# Titan_Servo_v1p01e.net
KiCad netlist of a schematic drawn in EAGLE
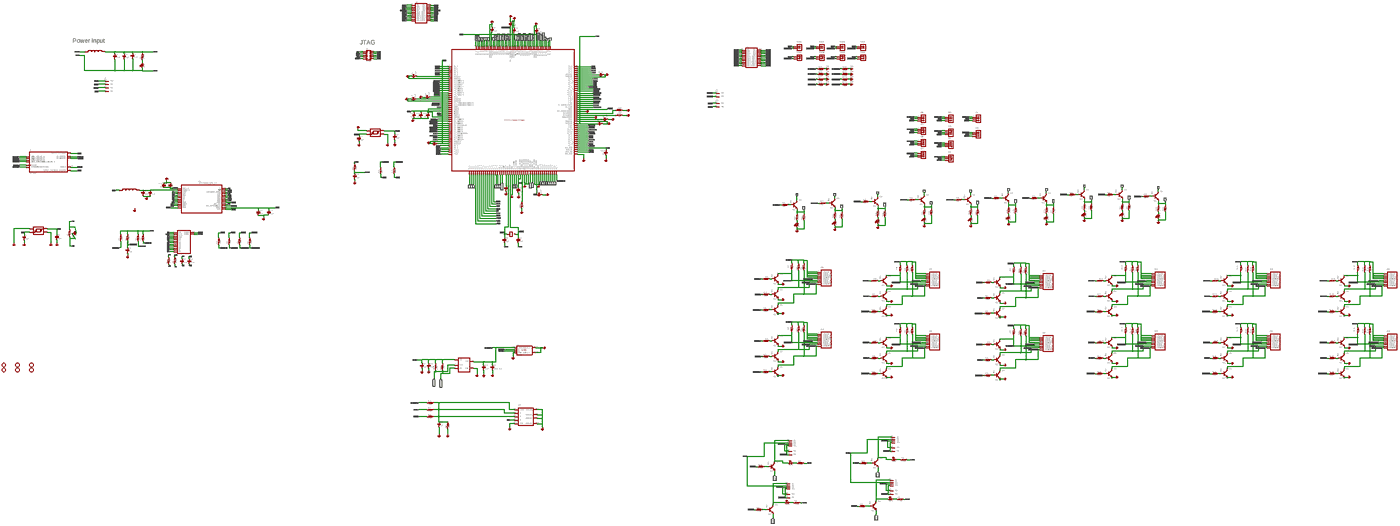
[diagram p0: schematic, sheet 1, overview]
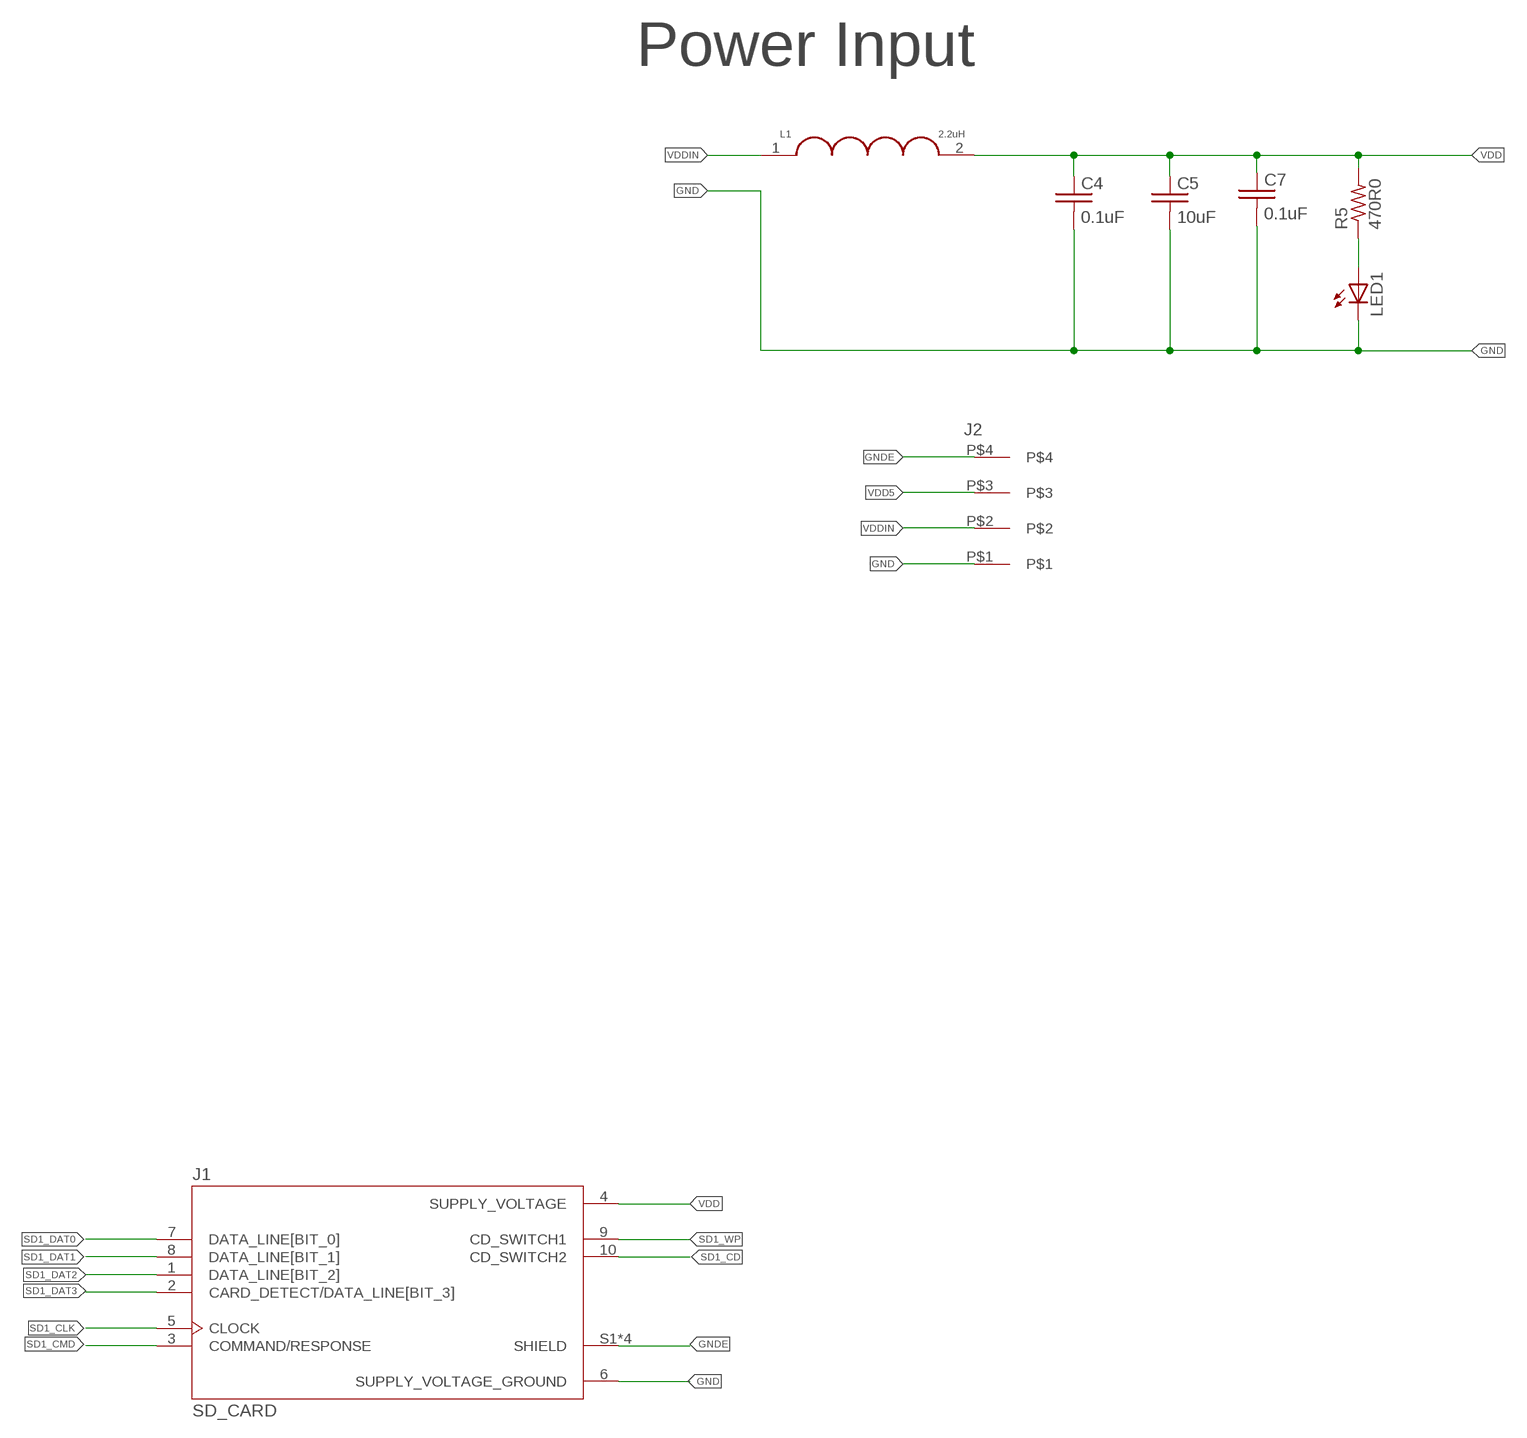
[diagram p1: schematic, sheet 1, part 1 of 9]
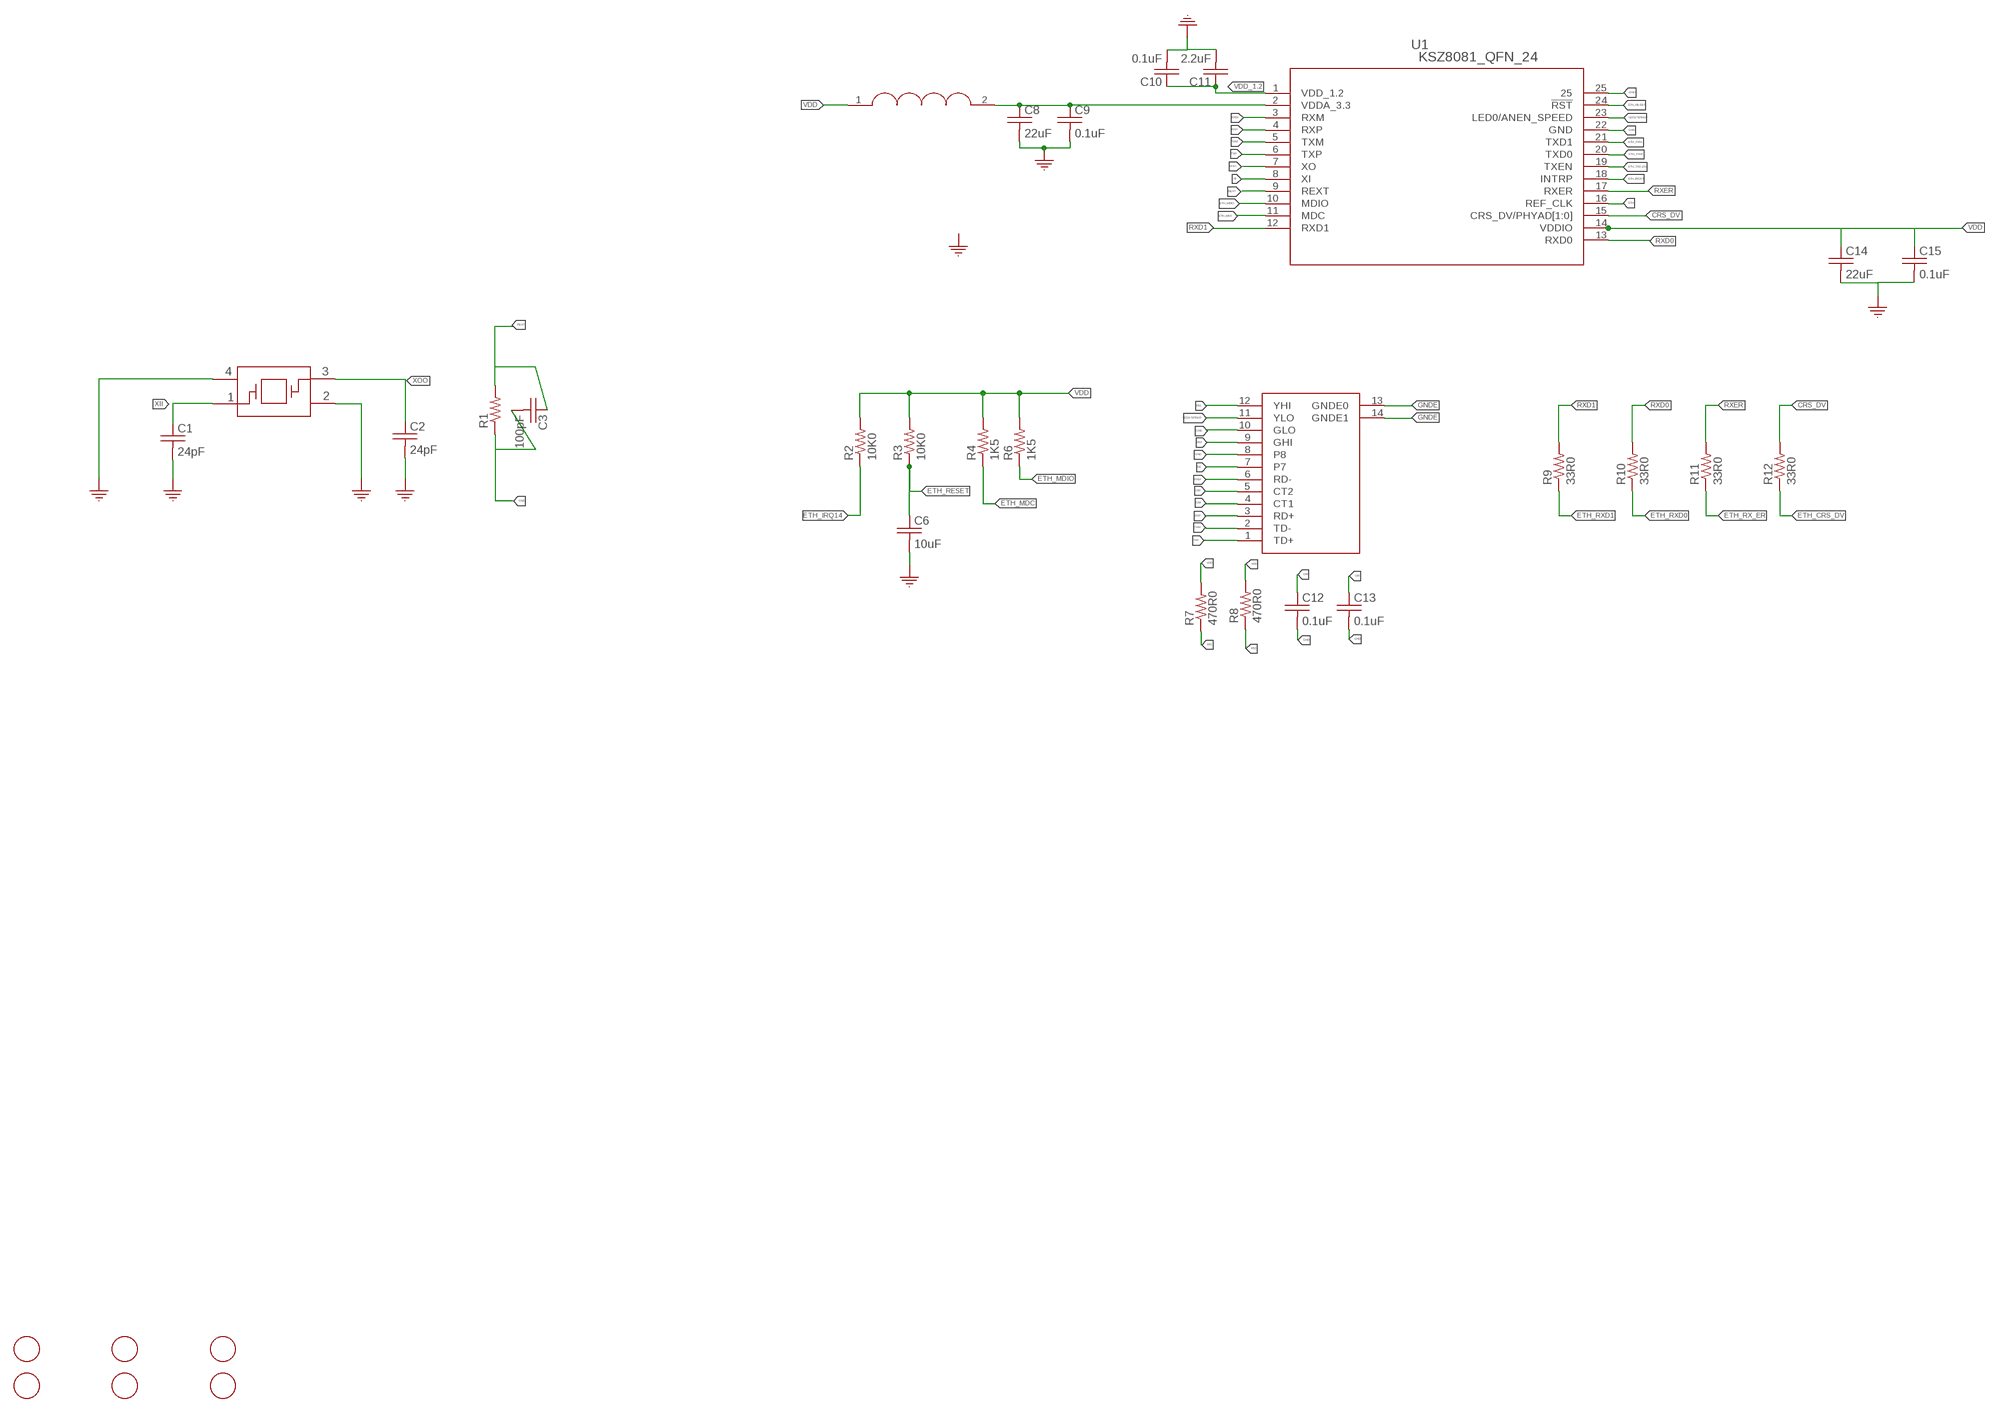
[diagram p2: schematic, sheet 1, part 2 of 9]
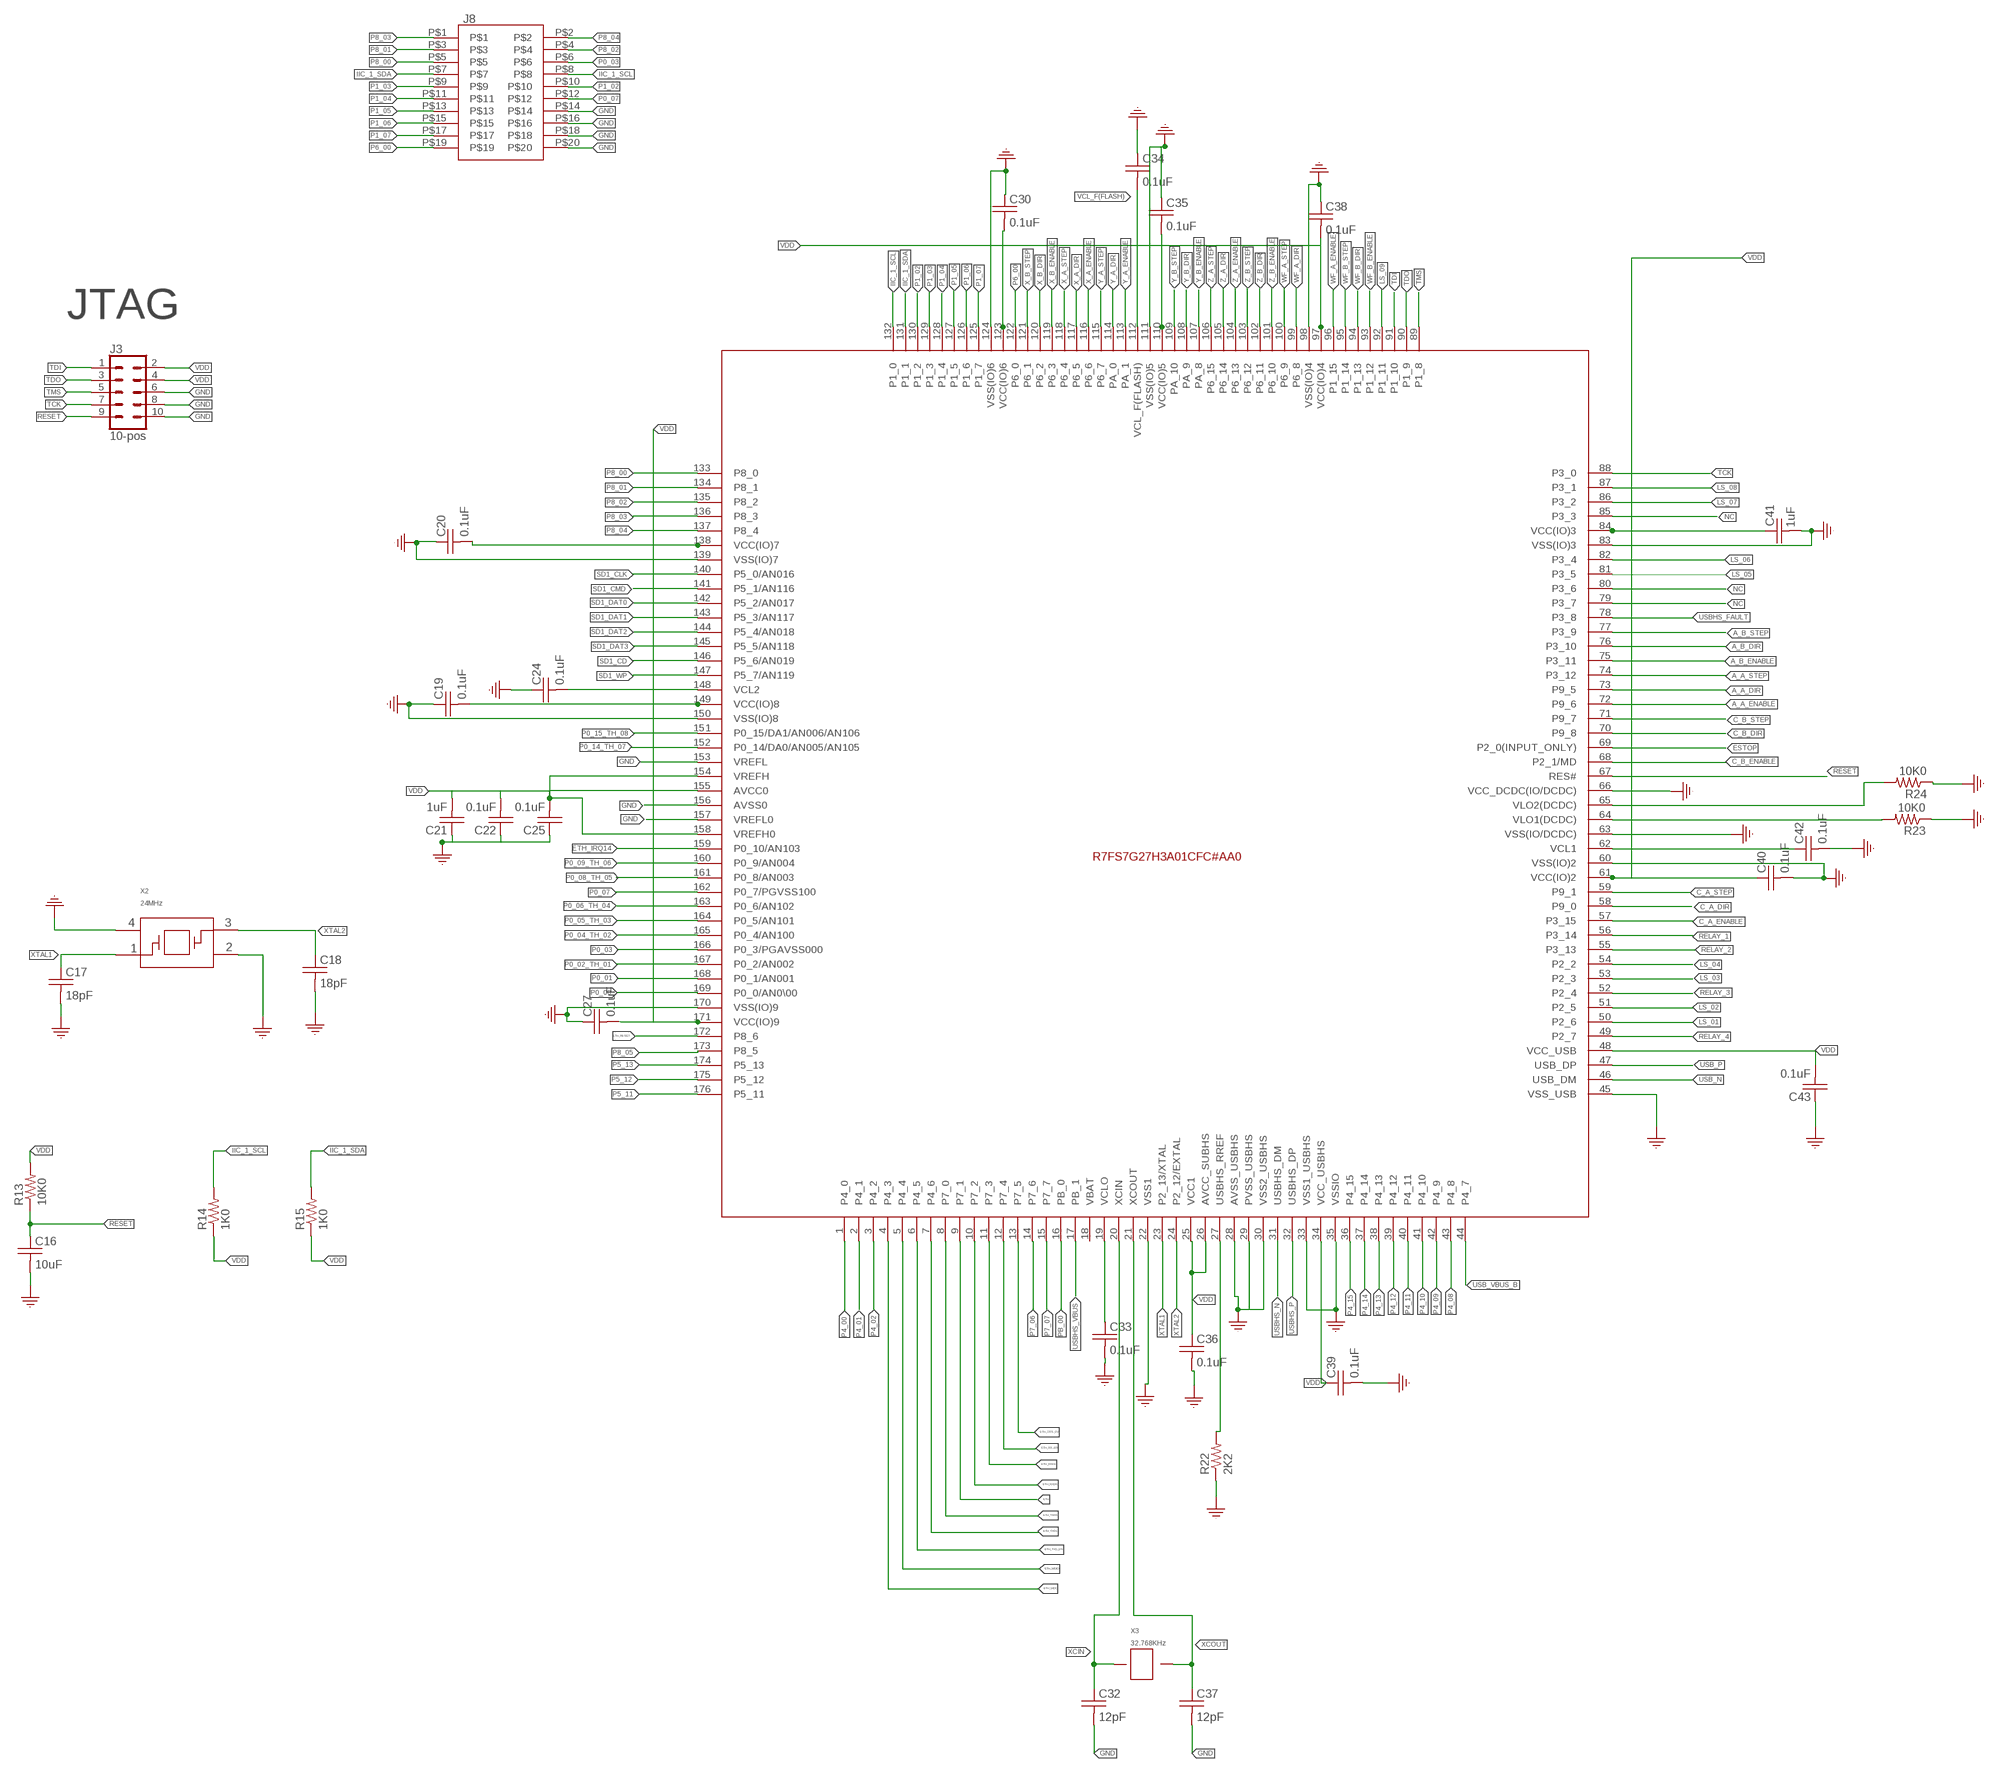
[diagram p3: schematic, sheet 1, part 3 of 9]
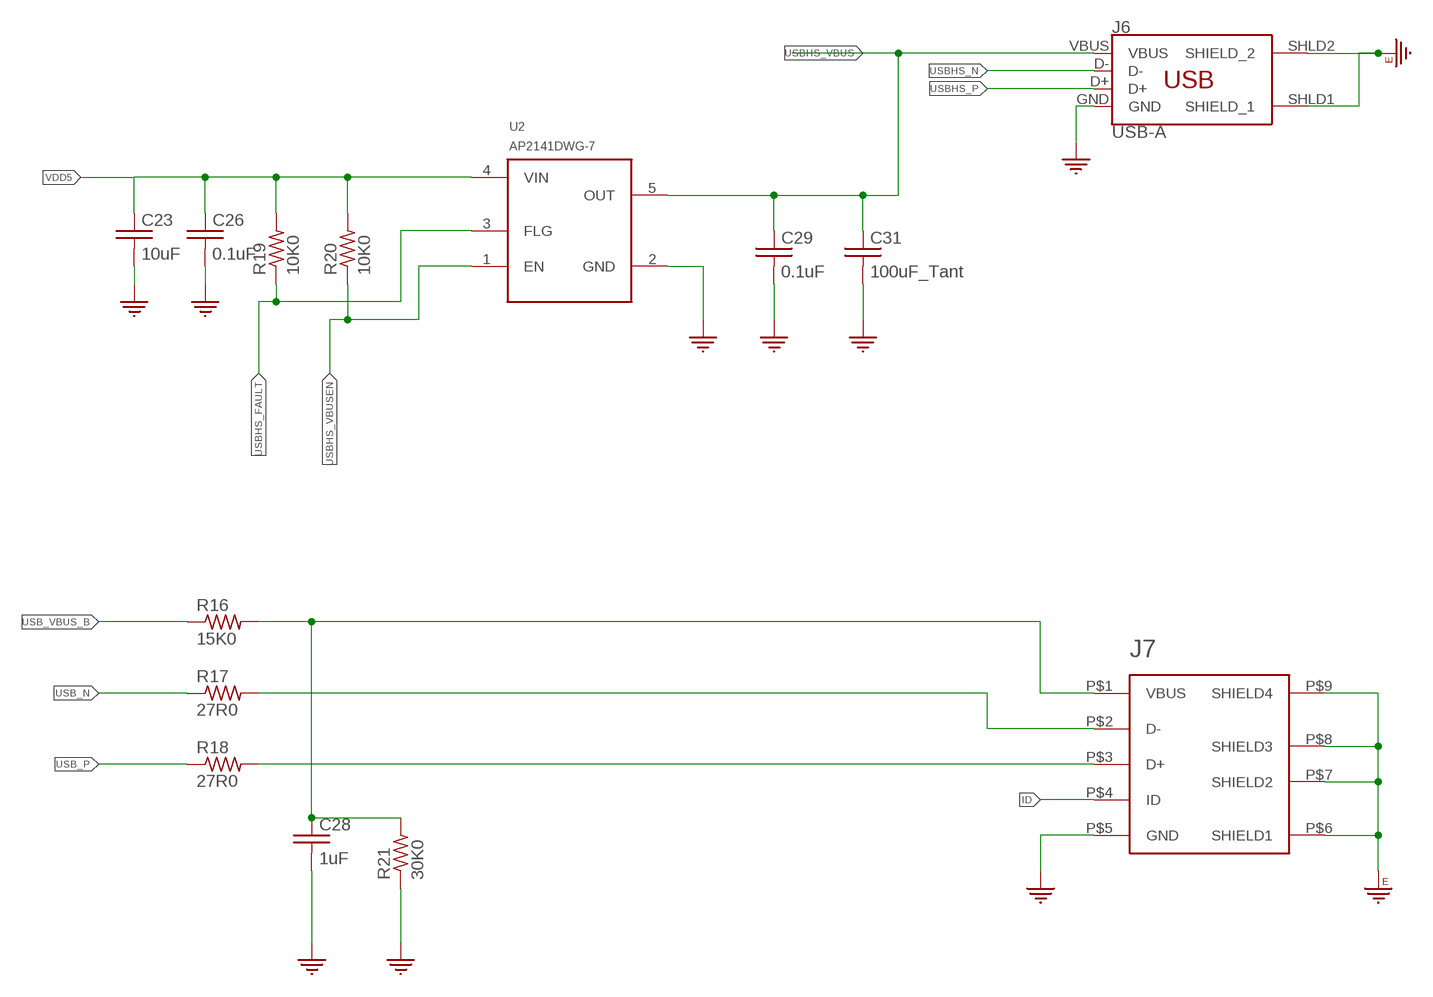
[diagram p4: schematic, sheet 1, part 4 of 9]
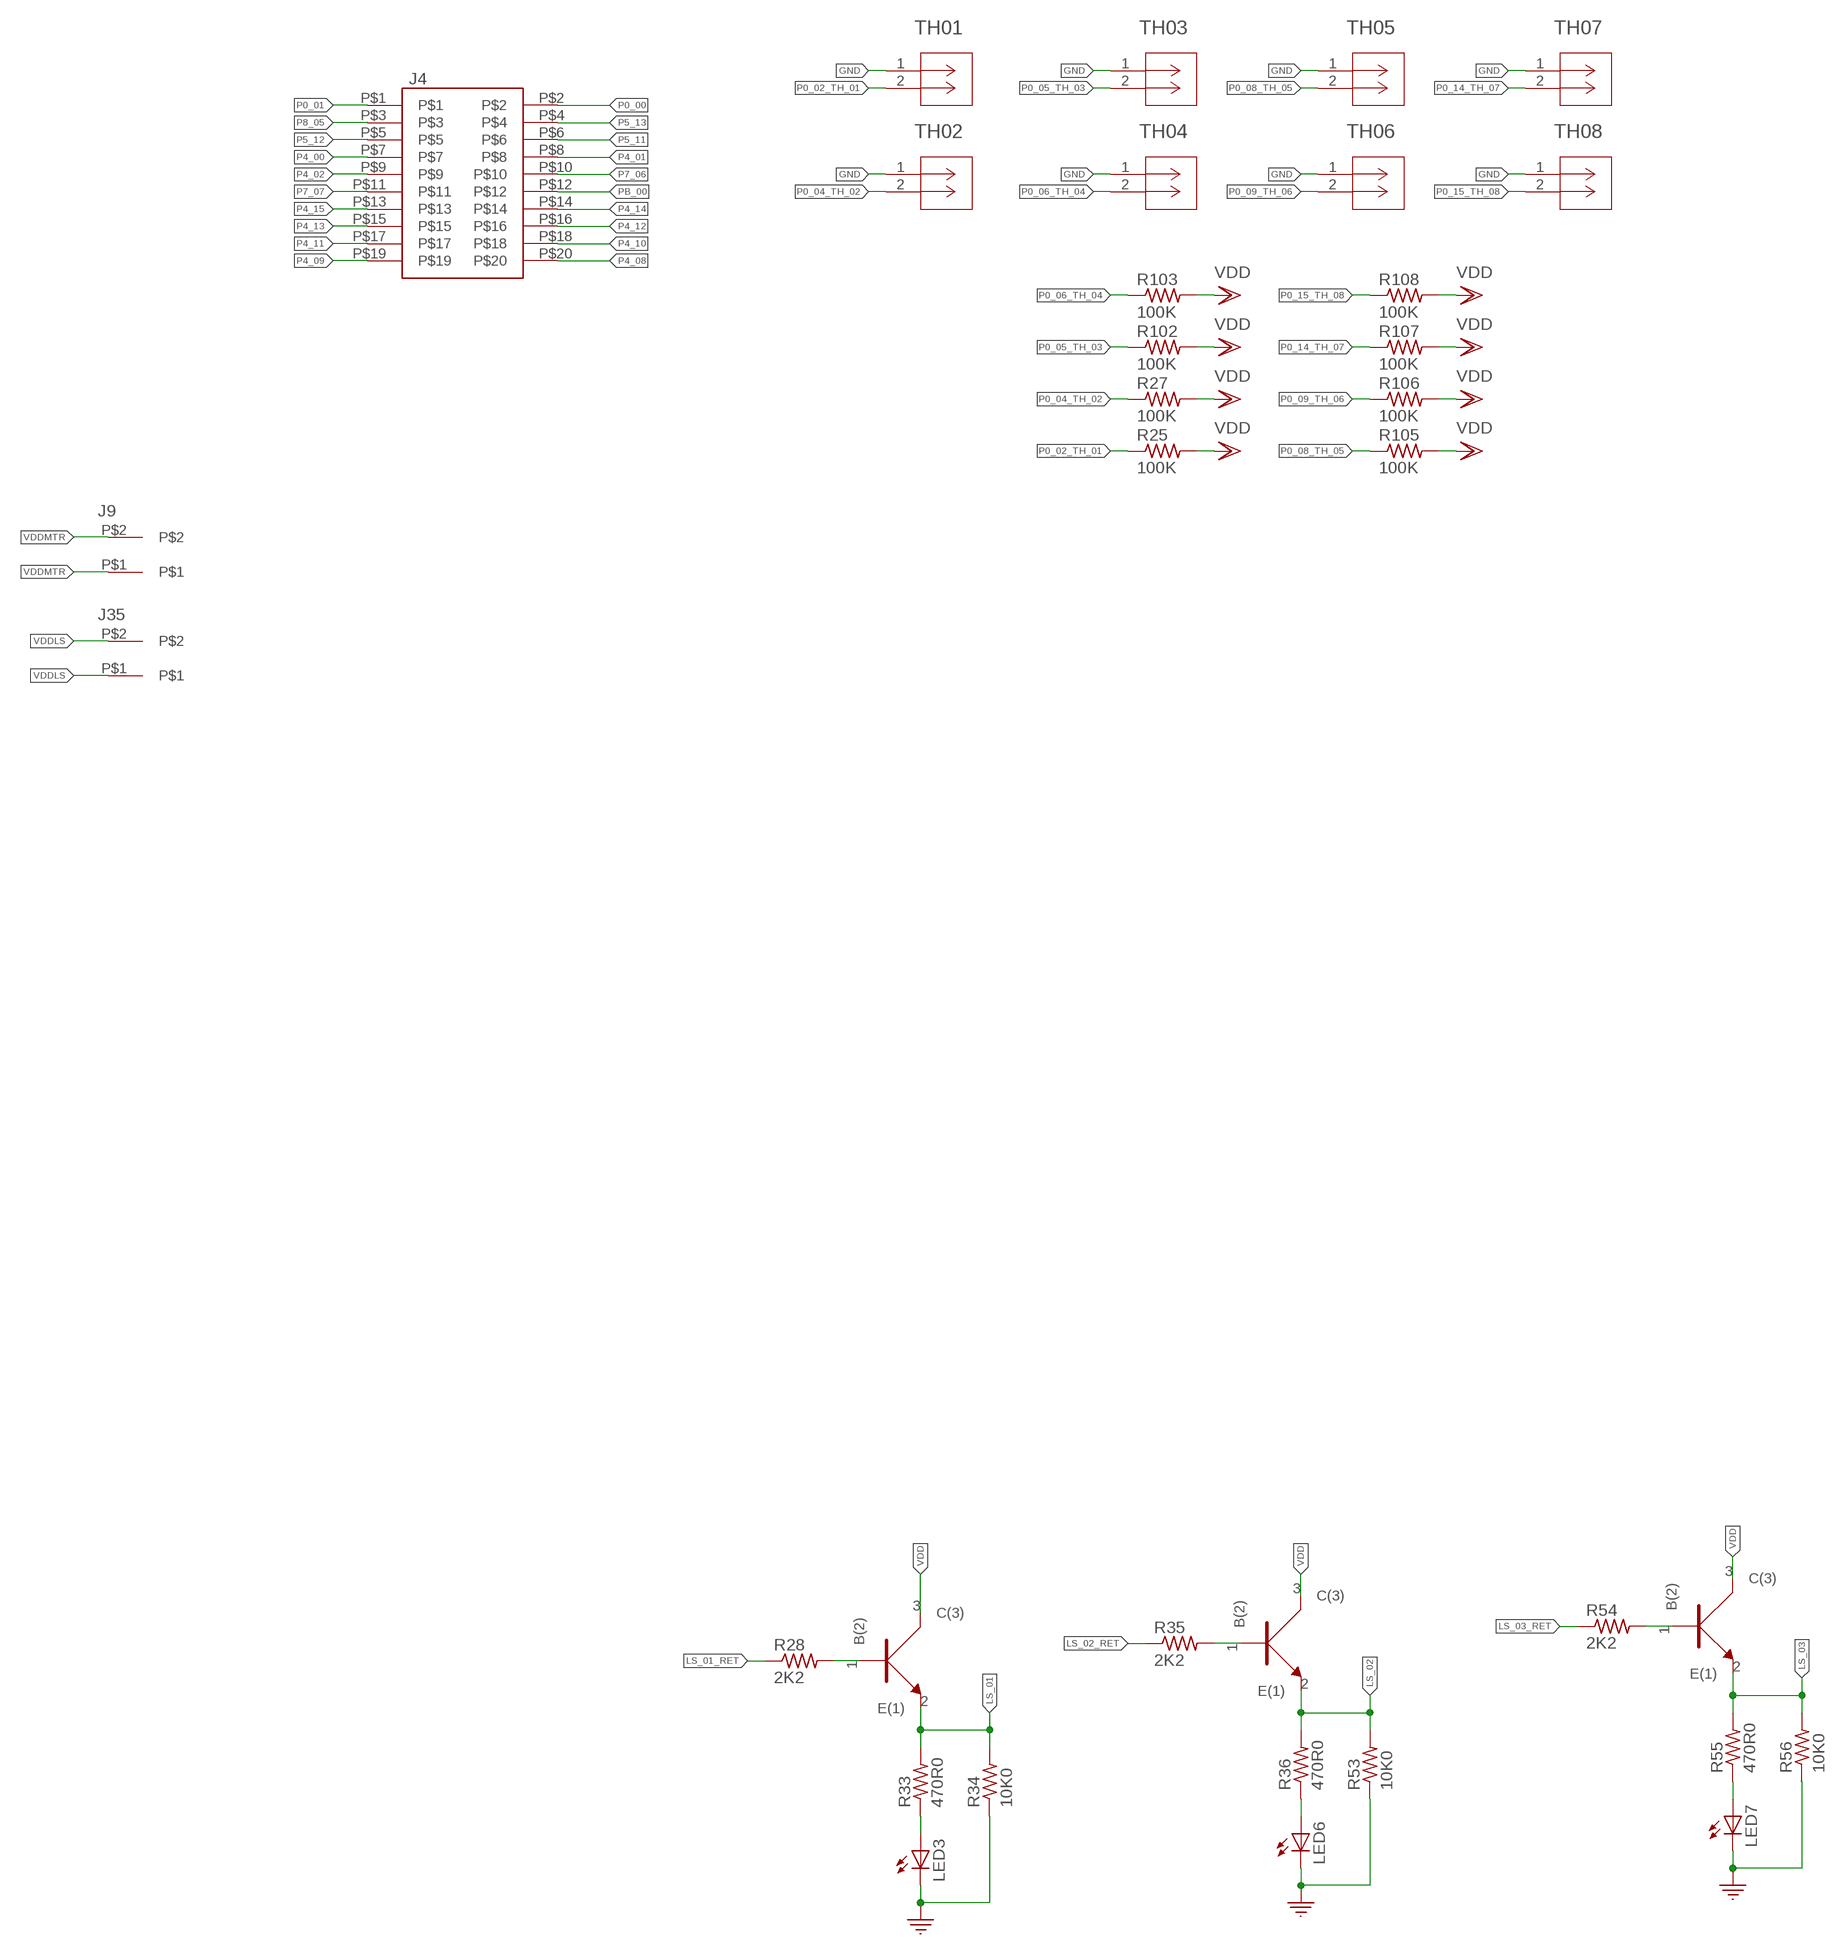
[diagram p5: schematic, sheet 1, part 5 of 9]
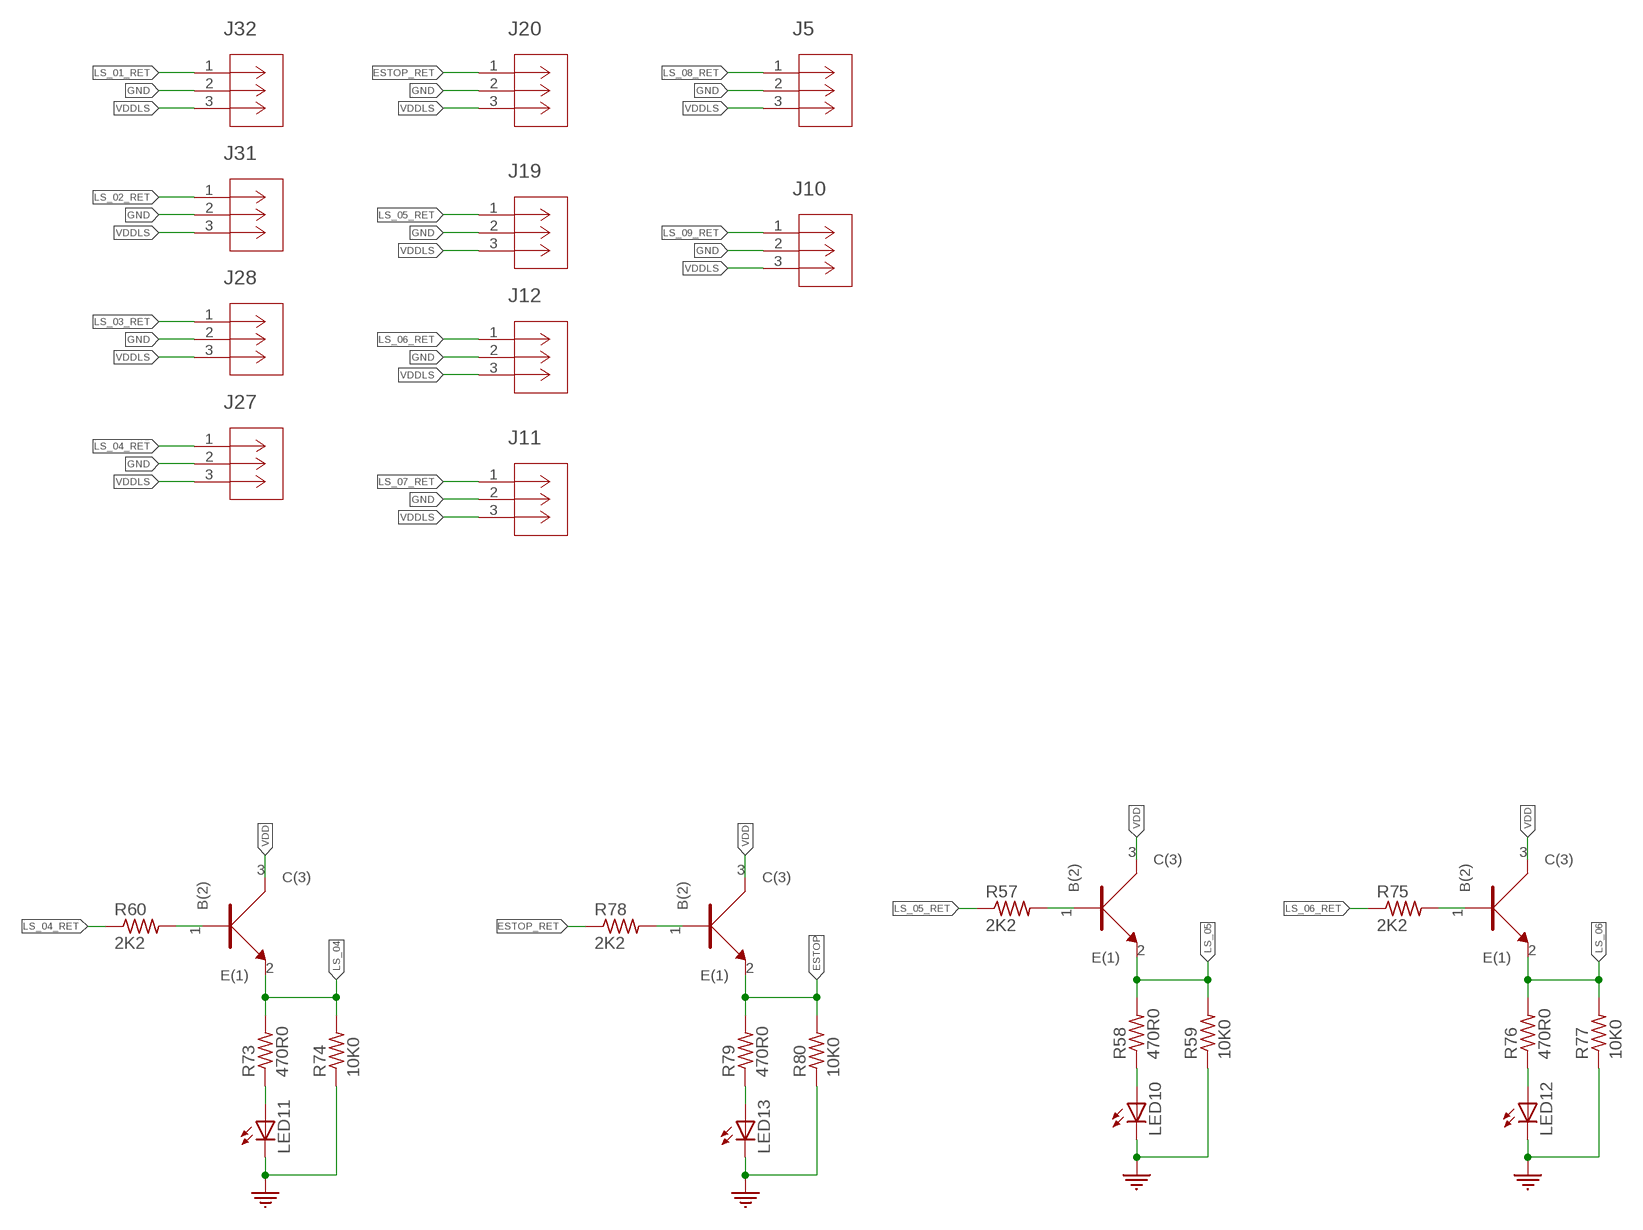
[diagram p6: schematic, sheet 1, part 6 of 9]
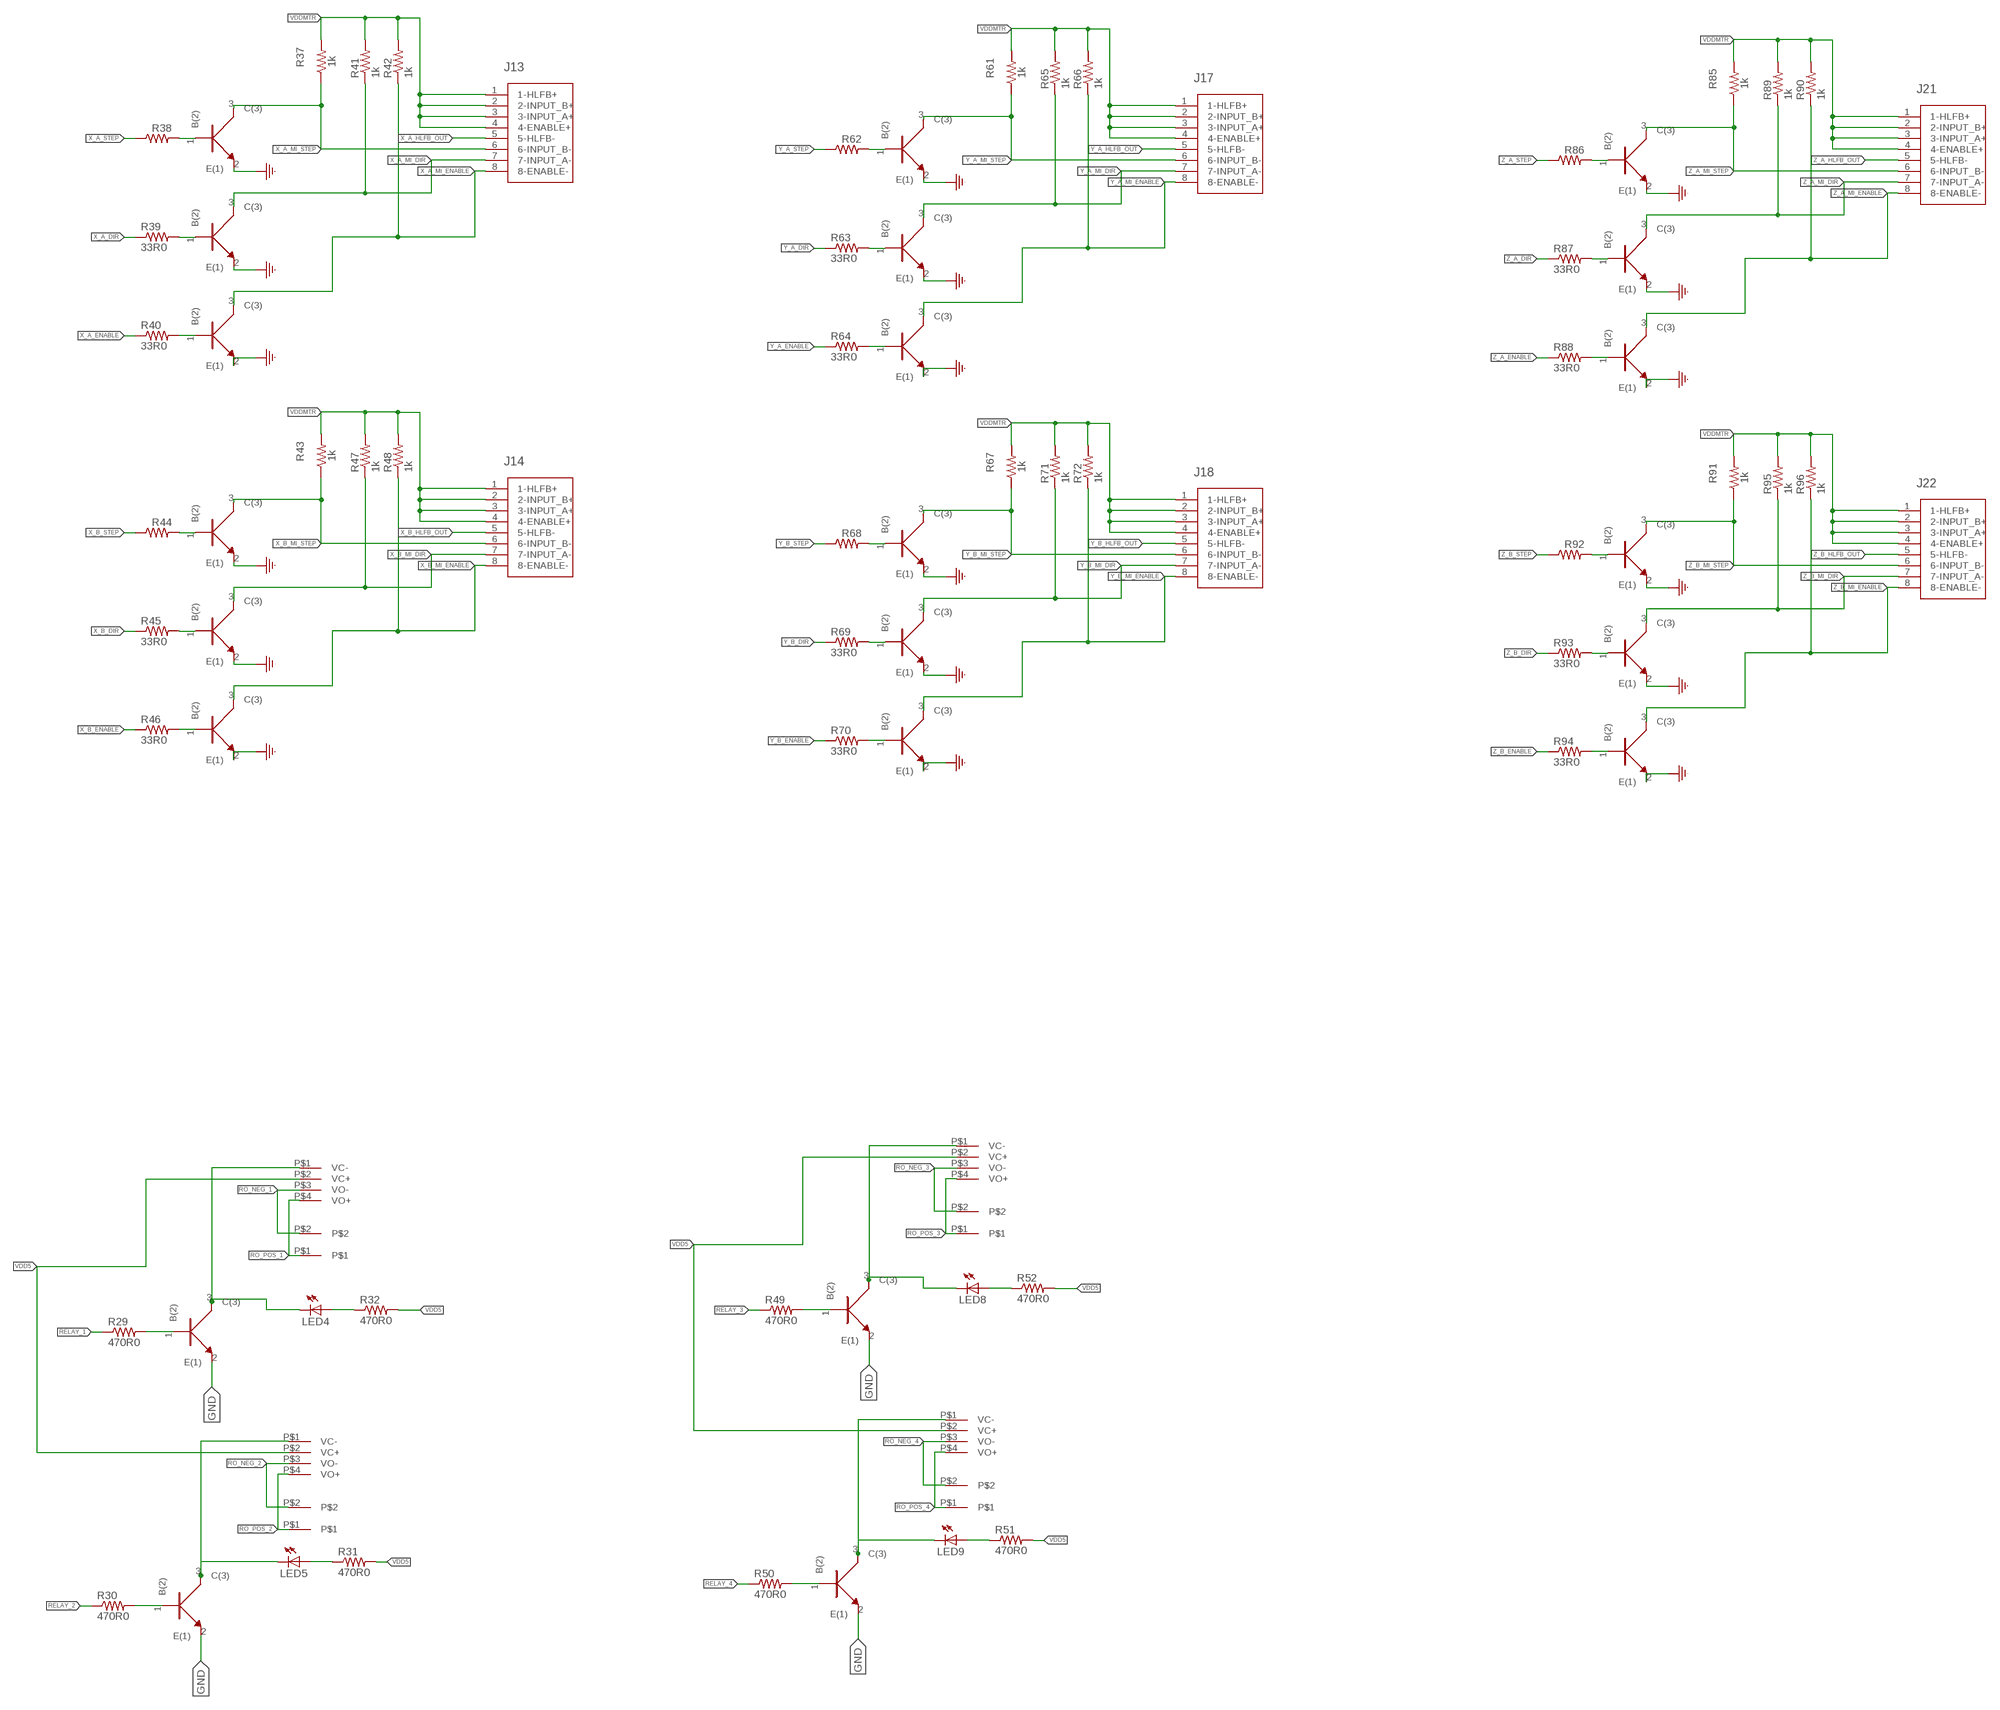
[diagram p7: schematic, sheet 1, part 7 of 9]
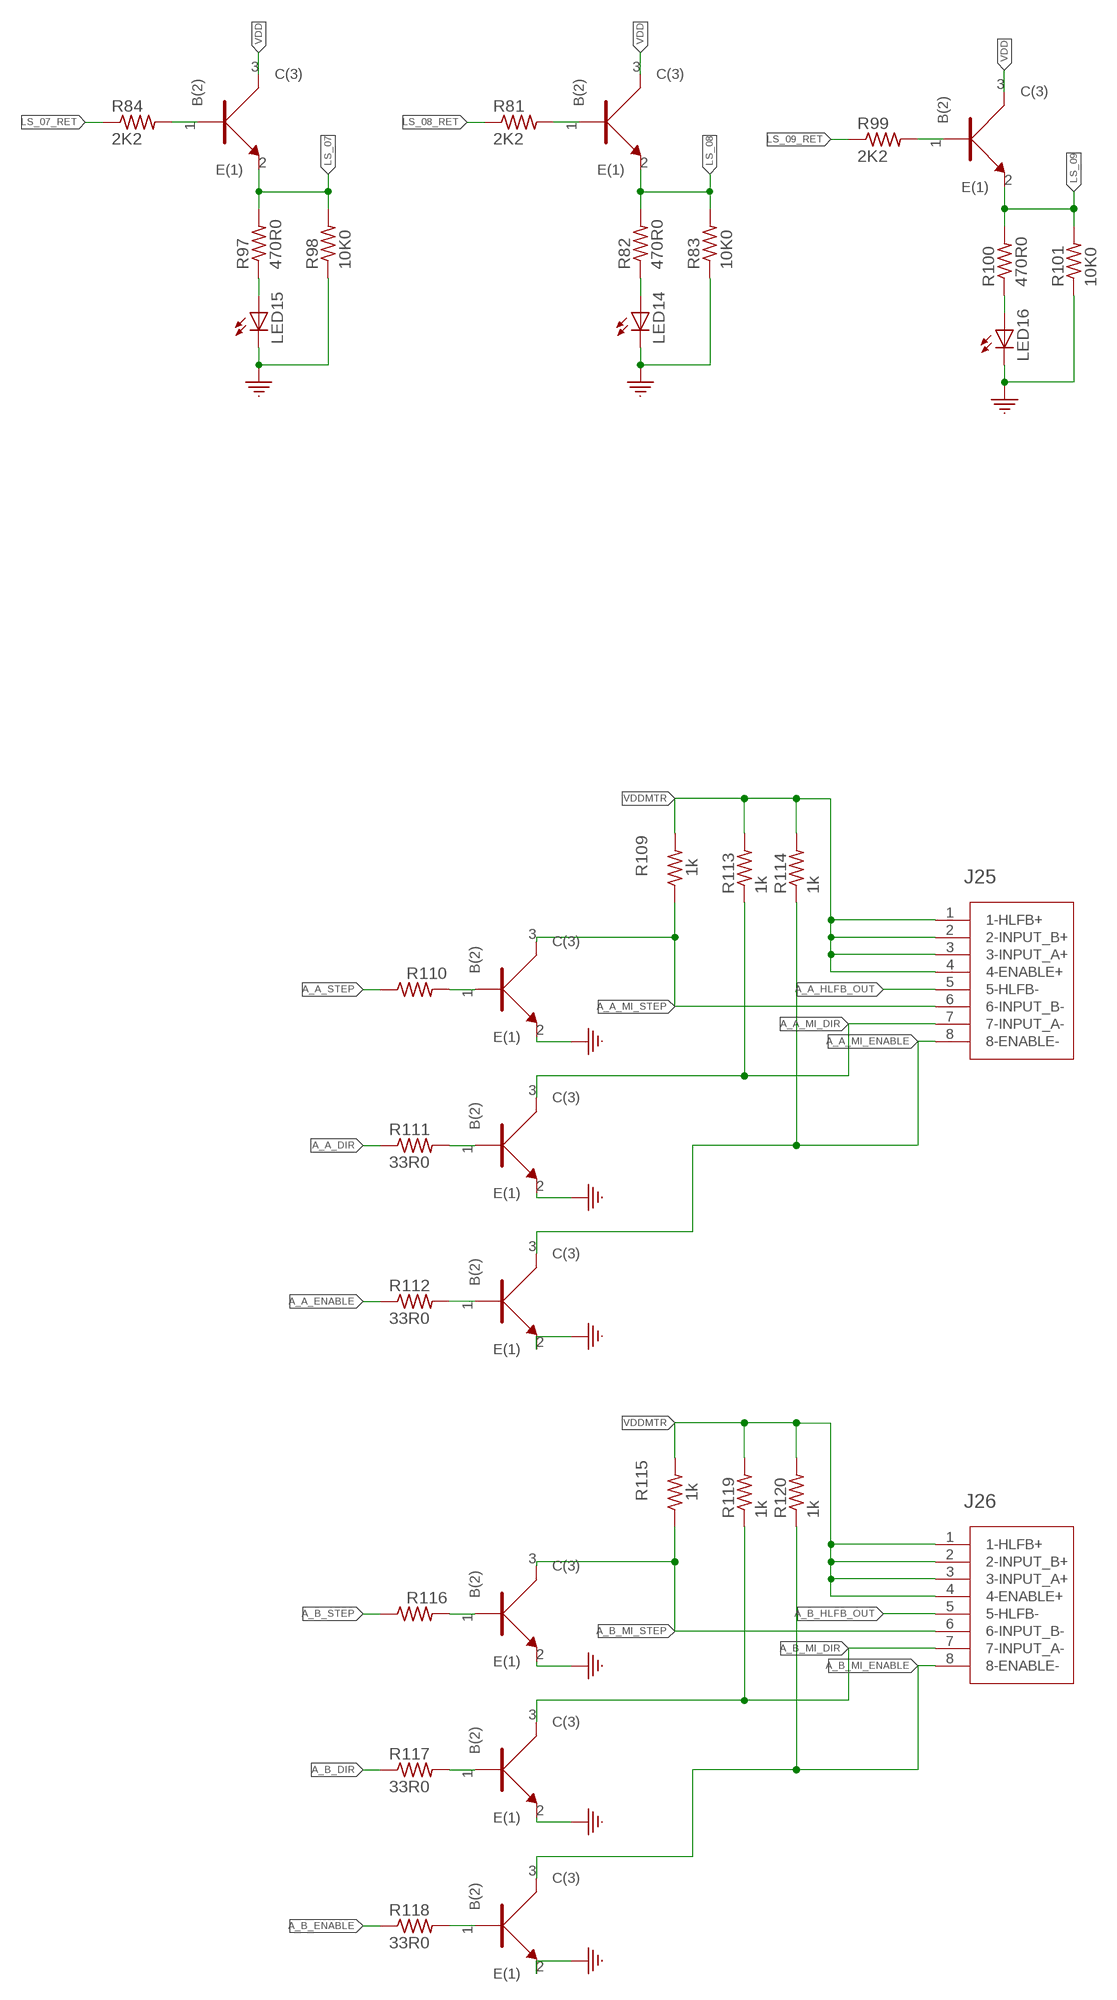
[diagram p8: schematic, sheet 1, part 8 of 9]
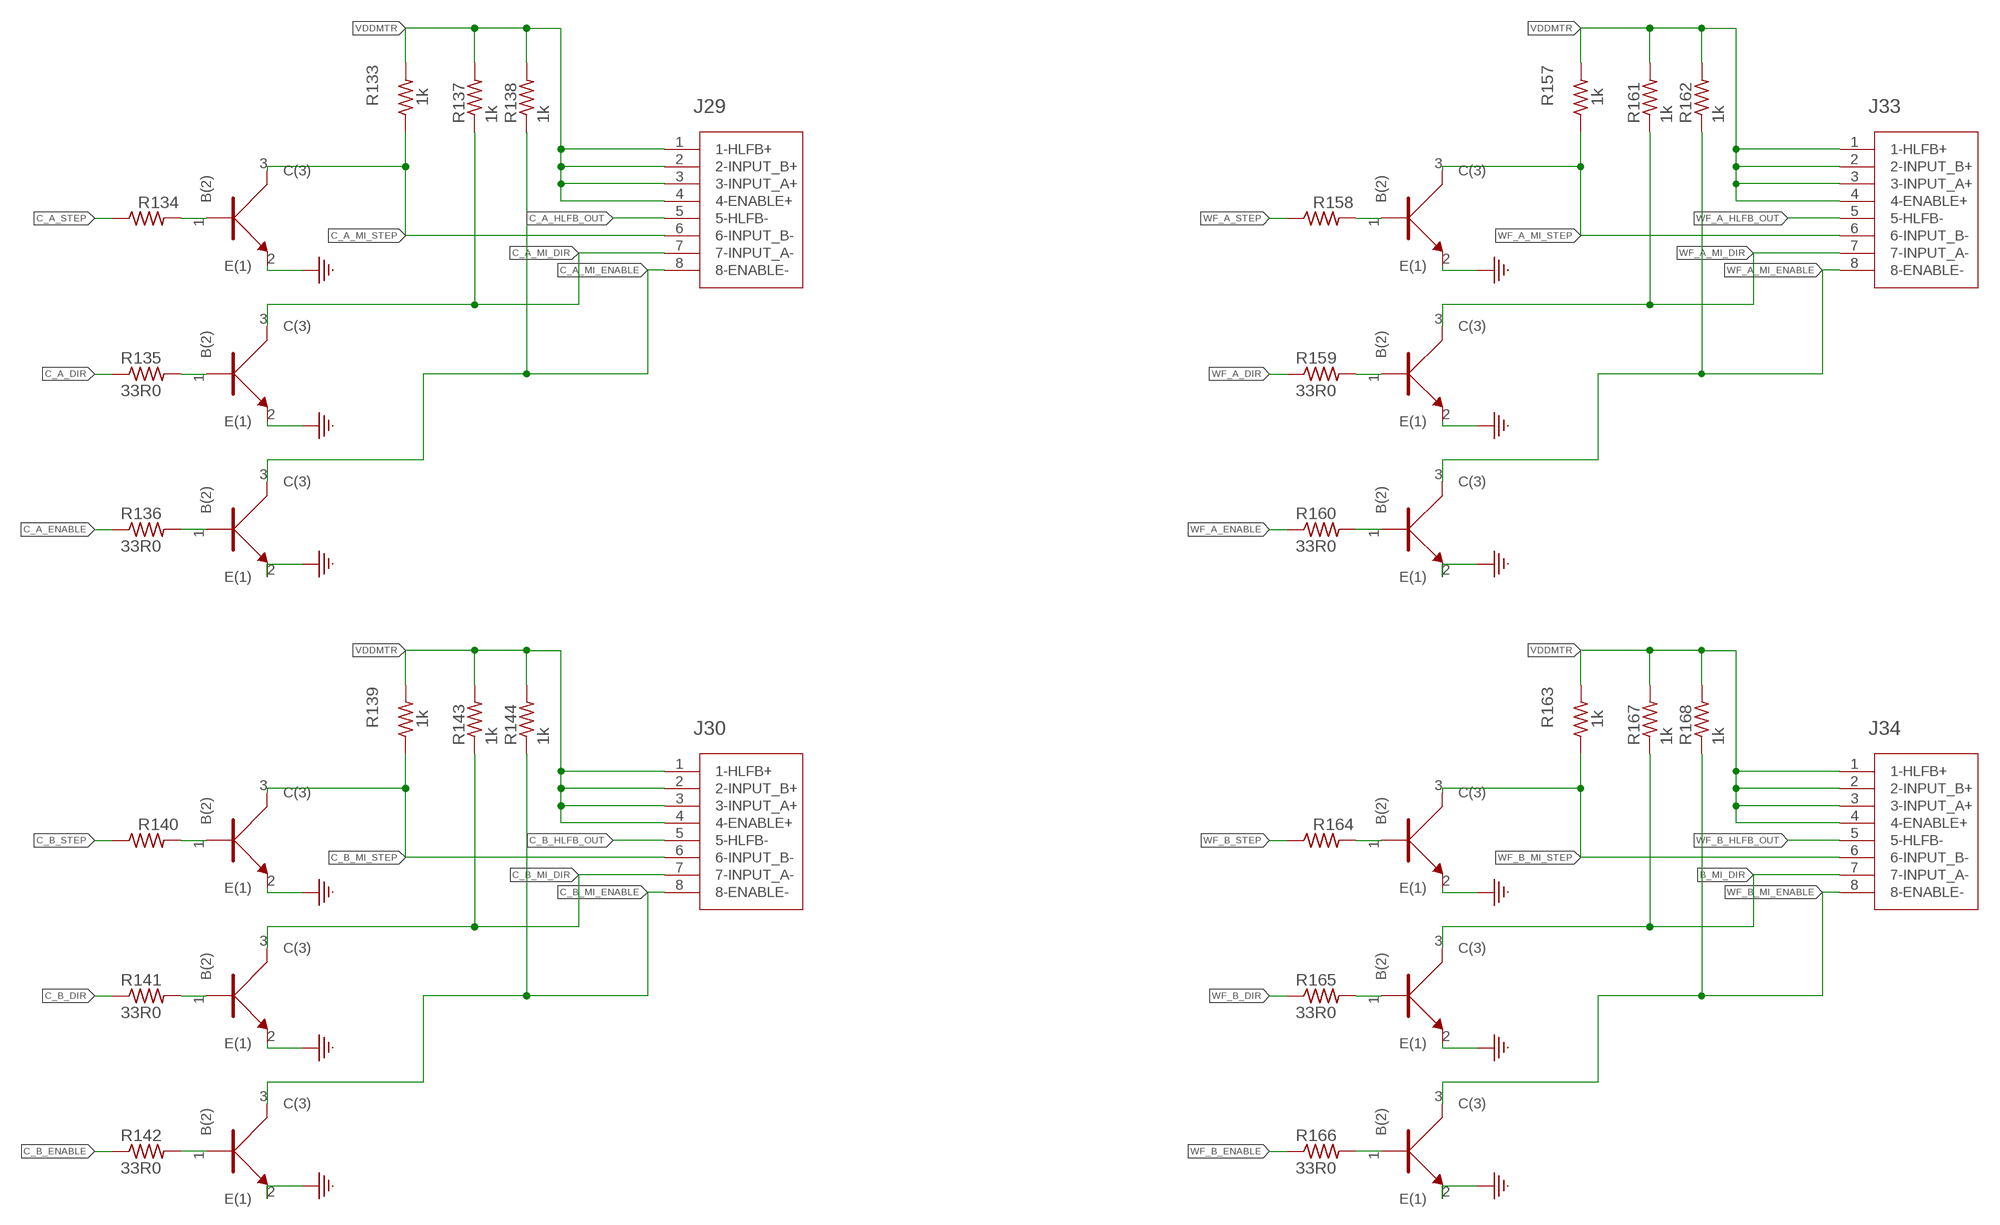
[diagram p9: schematic, sheet 1, part 9 of 9]

(export (version "E")
  (design (tool "Eeschema 10.0.6"))
  (components
    (comp (ref "AFID1")
      (value "FIDUCIAL_1MM")
      (footprint "eagle-import:FIDUCIAL_1MM")
      (libsource (lib "eagle-import") (part "FIDUCIAL_1MM"))
    )
    (comp (ref "AFID2")
      (value "FIDUCIAL_1MM")
      (footprint "eagle-import:FIDUCIAL_1MM")
      (libsource (lib "eagle-import") (part "FIDUCIAL_1MM"))
    )
    (comp (ref "AFID3")
      (value "FIDUCIAL_1MM")
      (footprint "eagle-import:FIDUCIAL_1MM")
      (libsource (lib "eagle-import") (part "FIDUCIAL_1MM"))
    )
    (comp (ref "AFID4")
      (value "FIDUCIAL_1MM")
      (footprint "eagle-import:FIDUCIAL_1MM")
      (libsource (lib "eagle-import") (part "FIDUCIAL_1MM"))
    )
    (comp (ref "AFID5")
      (value "FIDUCIAL_1MM")
      (footprint "eagle-import:FIDUCIAL_1MM")
      (libsource (lib "eagle-import") (part "FIDUCIAL_1MM"))
    )
    (comp (ref "AFID6")
      (value "FIDUCIAL_1MM")
      (footprint "eagle-import:FIDUCIAL_1MM")
      (libsource (lib "eagle-import") (part "FIDUCIAL_1MM"))
    )
    (comp (ref "C1")
      (value "24pF")
      (footprint "eagle-import:0402")
      (fields (field (name "PARTNO") "CC0402GRNPO9BN240"))
      (libsource (lib "eagle-import") (part "C_0402_24PF"))
    )
    (comp (ref "C2")
      (value "24pF")
      (footprint "eagle-import:0402")
      (fields (field (name "PARTNO") "CC0402GRNPO9BN240"))
      (libsource (lib "eagle-import") (part "C_0402_24PF"))
    )
    (comp (ref "C3")
      (value "100pF")
      (footprint "eagle-import:0402")
      (fields (field (name "PARTNO") "CL05C101JB5NNNC"))
      (libsource (lib "eagle-import") (part "C_0402_100PF"))
    )
    (comp (ref "C4")
      (value "0.1uF")
      (footprint "eagle-import:0402")
      (fields (field (name "PARTNO") "CL05F104ZO5NNNC"))
      (libsource (lib "eagle-import") (part "C_0402_0.1UF"))
    )
    (comp (ref "C5")
      (value "10uF")
      (footprint "eagle-import:0402")
      (fields (field (name "PARTNO") "CL05A106MP8NUB8"))
      (libsource (lib "eagle-import") (part "C_0402_10UF"))
    )
    (comp (ref "C6")
      (value "10uF")
      (footprint "eagle-import:0402")
      (fields (field (name "PARTNO") "CL05A106MP8NUB8"))
      (libsource (lib "eagle-import") (part "C_0402_10UF"))
    )
    (comp (ref "C7")
      (value "0.1uF")
      (footprint "eagle-import:0402")
      (fields (field (name "PARTNO") "CL05F104ZO5NNNC"))
      (libsource (lib "eagle-import") (part "C_0402_0.1UF"))
    )
    (comp (ref "C8")
      (value "22uF")
      (footprint "eagle-import:0402")
      (fields (field (name "PARTNO") "CL05A226MQ5N6J8"))
      (libsource (lib "eagle-import") (part "C_0402_22UF"))
    )
    (comp (ref "C9")
      (value "0.1uF")
      (footprint "eagle-import:0402")
      (fields (field (name "PARTNO") "CL05F104ZO5NNNC"))
      (libsource (lib "eagle-import") (part "C_0402_0.1UF"))
    )
    (comp (ref "C10")
      (value "0.1uF")
      (footprint "eagle-import:0402")
      (fields (field (name "PARTNO") "CL05F104ZO5NNNC"))
      (libsource (lib "eagle-import") (part "C_0402_0.1UF"))
    )
    (comp (ref "C11")
      (value "2.2uF")
      (footprint "eagle-import:0402")
      (fields (field (name "PARTNO") "GRM155C81C225ME15D"))
      (libsource (lib "eagle-import") (part "C_0402_2.2UF"))
    )
    (comp (ref "C12")
      (value "0.1uF")
      (footprint "eagle-import:0402")
      (fields (field (name "PARTNO") "CL05F104ZO5NNNC"))
      (libsource (lib "eagle-import") (part "C_0402_0.1UF"))
    )
    (comp (ref "C13")
      (value "0.1uF")
      (footprint "eagle-import:0402")
      (fields (field (name "PARTNO") "CL05F104ZO5NNNC"))
      (libsource (lib "eagle-import") (part "C_0402_0.1UF"))
    )
    (comp (ref "C14")
      (value "22uF")
      (footprint "eagle-import:0402")
      (fields (field (name "PARTNO") "CL05A226MQ5N6J8"))
      (libsource (lib "eagle-import") (part "C_0402_22UF"))
    )
    (comp (ref "C15")
      (value "0.1uF")
      (footprint "eagle-import:0402")
      (fields (field (name "PARTNO") "CL05F104ZO5NNNC"))
      (libsource (lib "eagle-import") (part "C_0402_0.1UF"))
    )
    (comp (ref "C16")
      (value "10uF")
      (footprint "eagle-import:0402")
      (fields (field (name "PARTNO") "CL05A106MP8NUB8"))
      (libsource (lib "eagle-import") (part "C_0402_10UF"))
    )
    (comp (ref "C17")
      (value "18pF")
      (footprint "eagle-import:0402")
      (fields (field (name "PARTNO") "UMK105CG180JV-F"))
      (libsource (lib "eagle-import") (part "C_0402_18PF"))
    )
    (comp (ref "C18")
      (value "18pF")
      (footprint "eagle-import:0402")
      (fields (field (name "PARTNO") "UMK105CG180JV-F"))
      (libsource (lib "eagle-import") (part "C_0402_18PF"))
    )
    (comp (ref "C19")
      (value "0.1uF")
      (footprint "eagle-import:0402")
      (fields (field (name "PARTNO") "CL05F104ZO5NNNC"))
      (libsource (lib "eagle-import") (part "C_0402_0.1UF"))
    )
    (comp (ref "C20")
      (value "0.1uF")
      (footprint "eagle-import:0402")
      (fields (field (name "PARTNO") "CL05F104ZO5NNNC"))
      (libsource (lib "eagle-import") (part "C_0402_0.1UF"))
    )
    (comp (ref "C21")
      (value "1uF")
      (footprint "eagle-import:0402")
      (fields (field (name "PARTNO") "CL05A105KO5NNNC"))
      (libsource (lib "eagle-import") (part "C_0402_1UF"))
    )
    (comp (ref "C22")
      (value "0.1uF")
      (footprint "eagle-import:0402")
      (fields (field (name "PARTNO") "CL05F104ZO5NNNC"))
      (libsource (lib "eagle-import") (part "C_0402_0.1UF"))
    )
    (comp (ref "C23")
      (value "10uF")
      (footprint "eagle-import:0402")
      (fields (field (name "PARTNO") "CL05A106MP8NUB8"))
      (libsource (lib "eagle-import") (part "C_0402_10UF"))
    )
    (comp (ref "C24")
      (value "0.1uF")
      (footprint "eagle-import:0402")
      (fields (field (name "PARTNO") "CL05F104ZO5NNNC"))
      (libsource (lib "eagle-import") (part "C_0402_0.1UF"))
    )
    (comp (ref "C25")
      (value "0.1uF")
      (footprint "eagle-import:0402")
      (fields (field (name "PARTNO") "CL05F104ZO5NNNC"))
      (libsource (lib "eagle-import") (part "C_0402_0.1UF"))
    )
    (comp (ref "C26")
      (value "0.1uF")
      (footprint "eagle-import:0402")
      (fields (field (name "PARTNO") "CL05F104ZO5NNNC"))
      (libsource (lib "eagle-import") (part "C_0402_0.1UF"))
    )
    (comp (ref "C27")
      (value "0.1uF")
      (footprint "eagle-import:0402")
      (fields (field (name "PARTNO") "CL05F104ZO5NNNC"))
      (libsource (lib "eagle-import") (part "C_0402_0.1UF"))
    )
    (comp (ref "C28")
      (value "1uF")
      (footprint "eagle-import:0402")
      (fields (field (name "PARTNO") "CL05A105KO5NNNC"))
      (libsource (lib "eagle-import") (part "C_0402_1UF"))
    )
    (comp (ref "C29")
      (value "0.1uF")
      (footprint "eagle-import:0402")
      (fields (field (name "PARTNO") "CL05F104ZO5NNNC"))
      (libsource (lib "eagle-import") (part "C_0402_0.1UF"))
    )
    (comp (ref "C30")
      (value "0.1uF")
      (footprint "eagle-import:0402")
      (fields (field (name "PARTNO") "CL05F104ZO5NNNC"))
      (libsource (lib "eagle-import") (part "C_0402_0.1UF"))
    )
    (comp (ref "C31")
      (value "100uF_Tant")
      (footprint "eagle-import:C1210")
      (fields (field (name "PARTNO") "TLJT107M010R0900"))
      (libsource (lib "eagle-import") (part "C_1210_100UF_TANT"))
    )
    (comp (ref "C32")
      (value "12pF")
      (footprint "eagle-import:0402")
      (fields (field (name "PARTNO") "CL05C120JB5NNNC"))
      (libsource (lib "eagle-import") (part "C_0402_12PF"))
    )
    (comp (ref "C33")
      (value "0.1uF")
      (footprint "eagle-import:0402")
      (fields (field (name "PARTNO") "CL05F104ZO5NNNC"))
      (libsource (lib "eagle-import") (part "C_0402_0.1UF"))
    )
    (comp (ref "C34")
      (value "0.1uF")
      (footprint "eagle-import:0402")
      (fields (field (name "PARTNO") "CL05F104ZO5NNNC"))
      (libsource (lib "eagle-import") (part "C_0402_0.1UF"))
    )
    (comp (ref "C35")
      (value "0.1uF")
      (footprint "eagle-import:0402")
      (fields (field (name "PARTNO") "CL05F104ZO5NNNC"))
      (libsource (lib "eagle-import") (part "C_0402_0.1UF"))
    )
    (comp (ref "C36")
      (value "0.1uF")
      (footprint "eagle-import:0402")
      (fields (field (name "PARTNO") "CL05F104ZO5NNNC"))
      (libsource (lib "eagle-import") (part "C_0402_0.1UF"))
    )
    (comp (ref "C37")
      (value "12pF")
      (footprint "eagle-import:0402")
      (fields (field (name "PARTNO") "CL05C120JB5NNNC"))
      (libsource (lib "eagle-import") (part "C_0402_12PF"))
    )
    (comp (ref "C38")
      (value "0.1uF")
      (footprint "eagle-import:0402")
      (fields (field (name "PARTNO") "CL05F104ZO5NNNC"))
      (libsource (lib "eagle-import") (part "C_0402_0.1UF"))
    )
    (comp (ref "C39")
      (value "0.1uF")
      (footprint "eagle-import:0402")
      (fields (field (name "PARTNO") "CL05F104ZO5NNNC"))
      (libsource (lib "eagle-import") (part "C_0402_0.1UF"))
    )
    (comp (ref "C40")
      (value "0.1uF")
      (footprint "eagle-import:0402")
      (fields (field (name "PARTNO") "CL05F104ZO5NNNC"))
      (libsource (lib "eagle-import") (part "C_0402_0.1UF"))
    )
    (comp (ref "C41")
      (value "1uF")
      (footprint "eagle-import:0402")
      (fields (field (name "PARTNO") "CL05A105KO5NNNC"))
      (libsource (lib "eagle-import") (part "C_0402_1UF"))
    )
    (comp (ref "C42")
      (value "0.1uF")
      (footprint "eagle-import:0402")
      (fields (field (name "PARTNO") "CL05F104ZO5NNNC"))
      (libsource (lib "eagle-import") (part "C_0402_0.1UF"))
    )
    (comp (ref "C43")
      (value "0.1uF")
      (footprint "eagle-import:0402")
      (fields (field (name "PARTNO") "CL05F104ZO5NNNC"))
      (libsource (lib "eagle-import") (part "C_0402_0.1UF"))
    )
    (comp (ref "FB1")
      (value "FB2_603")
      (footprint "eagle-import:0603")
      (fields (field (name "PARTNO") "BLM18PG121SN1D"))
      (libsource (lib "eagle-import") (part "FB_0603_120_OHM0603"))
    )
    (comp (ref "J1")
      (value "SD_CARD")
      (footprint "eagle-import:SD_CARD")
      (fields (field (name "MF") "Amphenol ICC") (field (name "PARTNO") "114-00841-68"))
      (libsource (lib "eagle-import") (part "SD_CARD_1140084168"))
    )
    (comp (ref "J2")
      (value "4-pos")
      (footprint "eagle-import:1X4_3.81MM_PITCH")
      (fields (field (name "PARTNO") "691322310004"))
      (libsource (lib "eagle-import") (part "3.81MM_1_X_4_RT_ANGLE_PLUG_HEADER"))
    )
    (comp (ref "J3")
      (value "10-pos")
      (footprint "eagle-import:2X5")
      (fields (field (name "PARTNO") "PH2RA-10-UA"))
      (libsource (lib "eagle-import") (part "CONN_05X2_RAPTH"))
    )
    (comp (ref "J4")
      (value "20-pos")
      (footprint "eagle-import:2_X_10_.1_INCH")
      (fields (field (name "PARTNO") "67996-420HLF"))
      (libsource (lib "eagle-import") (part "2_X_10_HEADER_GENERIC"))
    )
    (comp (ref "J5")
      (value "CONN_530470310_PICOBLADE_X_3")
      (footprint "eagle-import:CON_530470310_MOL")
      (fields
        (field (name "MANUFACTURER_PART_NUMBER") "530470310")
        (field (name "COPYRIGHT") "Copyright (C) 2022 Ultra Librarian. All rights reserved.")
      )
      (libsource (lib "eagle-import") (part "CONN_530470310_PICOBLADE_X_3"))
    )
    (comp (ref "J6")
      (value "USB-A")
      (footprint "eagle-import:USB_A_SMT")
      (fields (field (name "PARTNO") "87583-3010RPALF"))
      (libsource (lib "eagle-import") (part "USB_A"))
    )
    (comp (ref "J7")
      (value "USB-B-Micro")
      (footprint "eagle-import:USB_MICRO-B")
      (fields (field (name "PARTNO") "10118192-0002LF"))
      (libsource (lib "eagle-import") (part "USB_MICRO-B"))
    )
    (comp (ref "J8")
      (value "2_X_10_HEADER_GENERIC")
      (footprint "eagle-import:2_X_10_.1_INCH")
      (fields (field (name "PARTNO") "67996-420HLF"))
      (libsource (lib "eagle-import") (part "2_X_10_HEADER_GENERIC"))
    )
    (comp (ref "J9")
      (value "2-pos")
      (footprint "eagle-import:2_3.81MM_PITCH")
      (fields (field (name "PARTNO") "691322310002"))
      (libsource (lib "eagle-import") (part "3.81MM_1_X_2_RT_ANGLE_PLUG_HEADER"))
    )
    (comp (ref "J10")
      (value "CONN_530470310_PICOBLADE_X_3")
      (footprint "eagle-import:CON_530470310_MOL")
      (fields
        (field (name "MANUFACTURER_PART_NUMBER") "530470310")
        (field (name "COPYRIGHT") "Copyright (C) 2022 Ultra Librarian. All rights reserved.")
      )
      (libsource (lib "eagle-import") (part "CONN_530470310_PICOBLADE_X_3"))
    )
    (comp (ref "J11")
      (value "CONN_530470310_PICOBLADE_X_3")
      (footprint "eagle-import:CON_530470310_MOL")
      (fields
        (field (name "MANUFACTURER_PART_NUMBER") "530470310")
        (field (name "COPYRIGHT") "Copyright (C) 2022 Ultra Librarian. All rights reserved.")
      )
      (libsource (lib "eagle-import") (part "CONN_530470310_PICOBLADE_X_3"))
    )
    (comp (ref "J12")
      (value "CONN_530470310_PICOBLADE_X_3")
      (footprint "eagle-import:CON_530470310_MOL")
      (fields
        (field (name "MANUFACTURER_PART_NUMBER") "530470310")
        (field (name "COPYRIGHT") "Copyright (C) 2022 Ultra Librarian. All rights reserved.")
      )
      (libsource (lib "eagle-import") (part "CONN_530470310_PICOBLADE_X_3"))
    )
    (comp (ref "J13")
      (value "TEKNIC_MOTOR_8PIN")
      (footprint "eagle-import:CON_39281083")
      (fields
        (field (name "MANUFACTURER_PART_NUMBER") "39281083")
        (field (name "COPYRIGHT") "Copyright (C) 2022 Ultra Librarian. All rights reserved.")
      )
      (libsource (lib "eagle-import") (part "TEKNIC_MOTOR_8PIN"))
    )
    (comp (ref "J14")
      (value "TEKNIC_MOTOR_8PIN")
      (footprint "eagle-import:CON_39281083")
      (fields
        (field (name "MANUFACTURER_PART_NUMBER") "39281083")
        (field (name "COPYRIGHT") "Copyright (C) 2022 Ultra Librarian. All rights reserved.")
      )
      (libsource (lib "eagle-import") (part "TEKNIC_MOTOR_8PIN"))
    )
    (comp (ref "J15")
      (value "2-pos")
      (footprint "eagle-import:2_3.81MM_PITCH")
      (fields (field (name "PARTNO") "691322310002"))
      (libsource (lib "eagle-import") (part "3.81MM_1_X_2_RT_ANGLE_PLUG_HEADER"))
    )
    (comp (ref "J16")
      (value "2-pos")
      (footprint "eagle-import:2_3.81MM_PITCH")
      (fields (field (name "PARTNO") "691322310002"))
      (libsource (lib "eagle-import") (part "3.81MM_1_X_2_RT_ANGLE_PLUG_HEADER"))
    )
    (comp (ref "J17")
      (value "TEKNIC_MOTOR_8PIN")
      (footprint "eagle-import:CON_39281083")
      (fields
        (field (name "MANUFACTURER_PART_NUMBER") "39281083")
        (field (name "COPYRIGHT") "Copyright (C) 2022 Ultra Librarian. All rights reserved.")
      )
      (libsource (lib "eagle-import") (part "TEKNIC_MOTOR_8PIN"))
    )
    (comp (ref "J18")
      (value "TEKNIC_MOTOR_8PIN")
      (footprint "eagle-import:CON_39281083")
      (fields
        (field (name "MANUFACTURER_PART_NUMBER") "39281083")
        (field (name "COPYRIGHT") "Copyright (C) 2022 Ultra Librarian. All rights reserved.")
      )
      (libsource (lib "eagle-import") (part "TEKNIC_MOTOR_8PIN"))
    )
    (comp (ref "J19")
      (value "CONN_530470310_PICOBLADE_X_3")
      (footprint "eagle-import:CON_530470310_MOL")
      (fields
        (field (name "MANUFACTURER_PART_NUMBER") "530470310")
        (field (name "COPYRIGHT") "Copyright (C) 2022 Ultra Librarian. All rights reserved.")
      )
      (libsource (lib "eagle-import") (part "CONN_530470310_PICOBLADE_X_3"))
    )
    (comp (ref "J20")
      (value "CONN_530470310_PICOBLADE_X_3")
      (footprint "eagle-import:CON_530470310_MOL")
      (fields
        (field (name "MANUFACTURER_PART_NUMBER") "530470310")
        (field (name "COPYRIGHT") "Copyright (C) 2022 Ultra Librarian. All rights reserved.")
      )
      (libsource (lib "eagle-import") (part "CONN_530470310_PICOBLADE_X_3"))
    )
    (comp (ref "J21")
      (value "TEKNIC_MOTOR_8PIN")
      (footprint "eagle-import:CON_39281083")
      (fields
        (field (name "MANUFACTURER_PART_NUMBER") "39281083")
        (field (name "COPYRIGHT") "Copyright (C) 2022 Ultra Librarian. All rights reserved.")
      )
      (libsource (lib "eagle-import") (part "TEKNIC_MOTOR_8PIN"))
    )
    (comp (ref "J22")
      (value "TEKNIC_MOTOR_8PIN")
      (footprint "eagle-import:CON_39281083")
      (fields
        (field (name "MANUFACTURER_PART_NUMBER") "39281083")
        (field (name "COPYRIGHT") "Copyright (C) 2022 Ultra Librarian. All rights reserved.")
      )
      (libsource (lib "eagle-import") (part "TEKNIC_MOTOR_8PIN"))
    )
    (comp (ref "J23")
      (value "2-pos")
      (footprint "eagle-import:2_3.81MM_PITCH")
      (fields (field (name "PARTNO") "691322310002"))
      (libsource (lib "eagle-import") (part "3.81MM_1_X_2_RT_ANGLE_PLUG_HEADER"))
    )
    (comp (ref "J24")
      (value "2-pos")
      (footprint "eagle-import:2_3.81MM_PITCH")
      (fields (field (name "PARTNO") "691322310002"))
      (libsource (lib "eagle-import") (part "3.81MM_1_X_2_RT_ANGLE_PLUG_HEADER"))
    )
    (comp (ref "J25")
      (value "TEKNIC_MOTOR_8PIN")
      (footprint "eagle-import:CON_39281083")
      (fields
        (field (name "MANUFACTURER_PART_NUMBER") "39281083")
        (field (name "COPYRIGHT") "Copyright (C) 2022 Ultra Librarian. All rights reserved.")
      )
      (libsource (lib "eagle-import") (part "TEKNIC_MOTOR_8PIN"))
    )
    (comp (ref "J26")
      (value "TEKNIC_MOTOR_8PIN")
      (footprint "eagle-import:CON_39281083")
      (fields
        (field (name "MANUFACTURER_PART_NUMBER") "39281083")
        (field (name "COPYRIGHT") "Copyright (C) 2022 Ultra Librarian. All rights reserved.")
      )
      (libsource (lib "eagle-import") (part "TEKNIC_MOTOR_8PIN"))
    )
    (comp (ref "J27")
      (value "CONN_530470310_PICOBLADE_X_3")
      (footprint "eagle-import:CON_530470310_MOL")
      (fields
        (field (name "MANUFACTURER_PART_NUMBER") "530470310")
        (field (name "COPYRIGHT") "Copyright (C) 2022 Ultra Librarian. All rights reserved.")
      )
      (libsource (lib "eagle-import") (part "CONN_530470310_PICOBLADE_X_3"))
    )
    (comp (ref "J28")
      (value "CONN_530470310_PICOBLADE_X_3")
      (footprint "eagle-import:CON_530470310_MOL")
      (fields
        (field (name "MANUFACTURER_PART_NUMBER") "530470310")
        (field (name "COPYRIGHT") "Copyright (C) 2022 Ultra Librarian. All rights reserved.")
      )
      (libsource (lib "eagle-import") (part "CONN_530470310_PICOBLADE_X_3"))
    )
    (comp (ref "J29")
      (value "TEKNIC_MOTOR_8PIN")
      (footprint "eagle-import:CON_39281083")
      (fields
        (field (name "MANUFACTURER_PART_NUMBER") "39281083")
        (field (name "COPYRIGHT") "Copyright (C) 2022 Ultra Librarian. All rights reserved.")
      )
      (libsource (lib "eagle-import") (part "TEKNIC_MOTOR_8PIN"))
    )
    (comp (ref "J30")
      (value "TEKNIC_MOTOR_8PIN")
      (footprint "eagle-import:CON_39281083")
      (fields
        (field (name "MANUFACTURER_PART_NUMBER") "39281083")
        (field (name "COPYRIGHT") "Copyright (C) 2022 Ultra Librarian. All rights reserved.")
      )
      (libsource (lib "eagle-import") (part "TEKNIC_MOTOR_8PIN"))
    )
    (comp (ref "J31")
      (value "CONN_530470310_PICOBLADE_X_3")
      (footprint "eagle-import:CON_530470310_MOL")
      (fields
        (field (name "MANUFACTURER_PART_NUMBER") "530470310")
        (field (name "COPYRIGHT") "Copyright (C) 2022 Ultra Librarian. All rights reserved.")
      )
      (libsource (lib "eagle-import") (part "CONN_530470310_PICOBLADE_X_3"))
    )
    (comp (ref "J32")
      (value "CONN_530470310_PICOBLADE_X_3")
      (footprint "eagle-import:CON_530470310_MOL")
      (fields
        (field (name "MANUFACTURER_PART_NUMBER") "530470310")
        (field (name "COPYRIGHT") "Copyright (C) 2022 Ultra Librarian. All rights reserved.")
      )
      (libsource (lib "eagle-import") (part "CONN_530470310_PICOBLADE_X_3"))
    )
    (comp (ref "J33")
      (value "TEKNIC_MOTOR_8PIN")
      (footprint "eagle-import:CON_39281083")
      (fields
        (field (name "MANUFACTURER_PART_NUMBER") "39281083")
        (field (name "COPYRIGHT") "Copyright (C) 2022 Ultra Librarian. All rights reserved.")
      )
      (libsource (lib "eagle-import") (part "TEKNIC_MOTOR_8PIN"))
    )
    (comp (ref "J34")
      (value "TEKNIC_MOTOR_8PIN")
      (footprint "eagle-import:CON_39281083")
      (fields
        (field (name "MANUFACTURER_PART_NUMBER") "39281083")
        (field (name "COPYRIGHT") "Copyright (C) 2022 Ultra Librarian. All rights reserved.")
      )
      (libsource (lib "eagle-import") (part "TEKNIC_MOTOR_8PIN"))
    )
    (comp (ref "J35")
      (value "2-pos")
      (footprint "eagle-import:2_3.81MM_PITCH")
      (fields (field (name "PARTNO") "691322310002"))
      (libsource (lib "eagle-import") (part "3.81MM_1_X_2_RT_ANGLE_PLUG_HEADER"))
    )
    (comp (ref "L1")
      (value "2.2uH")
      (footprint "eagle-import:1008")
      (fields (field (name "PARTNO") "LQM2HPN2R2MG0L"))
      (libsource (lib "eagle-import") (part "INDUCTOR_1008_2.2_MH_1.3A"))
    )
    (comp (ref "LED1")
      (value "Green")
      (footprint "eagle-import:0805")
      (fields (field (name "PARTNO") "LG R971-KN-1"))
      (libsource (lib "eagle-import") (part "LED_0805_GREEN"))
    )
    (comp (ref "LED3")
      (value "Green")
      (footprint "eagle-import:0805")
      (fields (field (name "PARTNO") "LG R971-KN-1"))
      (libsource (lib "eagle-import") (part "LED_0805_GREEN"))
    )
    (comp (ref "LED4")
      (value "Green")
      (footprint "eagle-import:0805")
      (fields (field (name "PARTNO") "LG R971-KN-1"))
      (libsource (lib "eagle-import") (part "LED_0805_GREEN"))
    )
    (comp (ref "LED5")
      (value "Green")
      (footprint "eagle-import:0805")
      (fields (field (name "PARTNO") "LG R971-KN-1"))
      (libsource (lib "eagle-import") (part "LED_0805_GREEN"))
    )
    (comp (ref "LED6")
      (value "Green")
      (footprint "eagle-import:0805")
      (fields (field (name "PARTNO") "LG R971-KN-1"))
      (libsource (lib "eagle-import") (part "LED_0805_GREEN"))
    )
    (comp (ref "LED7")
      (value "Green")
      (footprint "eagle-import:0805")
      (fields (field (name "PARTNO") "LG R971-KN-1"))
      (libsource (lib "eagle-import") (part "LED_0805_GREEN"))
    )
    (comp (ref "LED8")
      (value "Green")
      (footprint "eagle-import:0805")
      (fields (field (name "PARTNO") "LG R971-KN-1"))
      (libsource (lib "eagle-import") (part "LED_0805_GREEN"))
    )
    (comp (ref "LED9")
      (value "Green")
      (footprint "eagle-import:0805")
      (fields (field (name "PARTNO") "LG R971-KN-1"))
      (libsource (lib "eagle-import") (part "LED_0805_GREEN"))
    )
    (comp (ref "LED10")
      (value "Green")
      (footprint "eagle-import:0805")
      (fields (field (name "PARTNO") "LG R971-KN-1"))
      (libsource (lib "eagle-import") (part "LED_0805_GREEN"))
    )
    (comp (ref "LED11")
      (value "Green")
      (footprint "eagle-import:0805")
      (fields (field (name "PARTNO") "LG R971-KN-1"))
      (libsource (lib "eagle-import") (part "LED_0805_GREEN"))
    )
    (comp (ref "LED12")
      (value "Green")
      (footprint "eagle-import:0805")
      (fields (field (name "PARTNO") "LG R971-KN-1"))
      (libsource (lib "eagle-import") (part "LED_0805_GREEN"))
    )
    (comp (ref "LED13")
      (value "Green")
      (footprint "eagle-import:0805")
      (fields (field (name "PARTNO") "LG R971-KN-1"))
      (libsource (lib "eagle-import") (part "LED_0805_GREEN"))
    )
    (comp (ref "LED14")
      (value "Green")
      (footprint "eagle-import:0805")
      (fields (field (name "PARTNO") "LG R971-KN-1"))
      (libsource (lib "eagle-import") (part "LED_0805_GREEN"))
    )
    (comp (ref "LED15")
      (value "Green")
      (footprint "eagle-import:0805")
      (fields (field (name "PARTNO") "LG R971-KN-1"))
      (libsource (lib "eagle-import") (part "LED_0805_GREEN"))
    )
    (comp (ref "LED16")
      (value "Green")
      (footprint "eagle-import:0805")
      (fields (field (name "PARTNO") "LG R971-KN-1"))
      (libsource (lib "eagle-import") (part "LED_0805_GREEN"))
    )
    (comp (ref "R1")
      (value "6K49")
      (footprint "eagle-import:0402")
      (fields (field (name "PARTNO") "RMCF0402FT6K49"))
      (libsource (lib "eagle-import") (part "R_0402_6K49"))
    )
    (comp (ref "R2")
      (value "10K0")
      (footprint "eagle-import:0402")
      (fields (field (name "PARTNO") "RMCF0402JT10K0"))
      (libsource (lib "eagle-import") (part "R_0402_10K0"))
    )
    (comp (ref "R3")
      (value "10K0")
      (footprint "eagle-import:0402")
      (fields (field (name "PARTNO") "RMCF0402JT10K0"))
      (libsource (lib "eagle-import") (part "R_0402_10K0"))
    )
    (comp (ref "R4")
      (value "1K5")
      (footprint "eagle-import:0402")
      (fields (field (name "PARTNO") "RMCF0402JT1K50"))
      (libsource (lib "eagle-import") (part "R_0402_1K5"))
    )
    (comp (ref "R5")
      (value "470R0")
      (footprint "eagle-import:0402")
      (fields (field (name "PARTNO") "RMCF0402JT470R"))
      (libsource (lib "eagle-import") (part "R_0402_470R0"))
    )
    (comp (ref "R6")
      (value "1K5")
      (footprint "eagle-import:0402")
      (fields (field (name "PARTNO") "RMCF0402JT1K50"))
      (libsource (lib "eagle-import") (part "R_0402_1K5"))
    )
    (comp (ref "R7")
      (value "470R0")
      (footprint "eagle-import:0402")
      (fields (field (name "PARTNO") "RMCF0402JT470R"))
      (libsource (lib "eagle-import") (part "R_0402_470R0"))
    )
    (comp (ref "R8")
      (value "470R0")
      (footprint "eagle-import:0402")
      (fields (field (name "PARTNO") "RMCF0402JT470R"))
      (libsource (lib "eagle-import") (part "R_0402_470R0"))
    )
    (comp (ref "R9")
      (value "33R0")
      (footprint "eagle-import:0402")
      (fields (field (name "PARTNO") "RMCF0402JT33R0"))
      (libsource (lib "eagle-import") (part "R_0402_33R0"))
    )
    (comp (ref "R10")
      (value "33R0")
      (footprint "eagle-import:0402")
      (fields (field (name "PARTNO") "RMCF0402JT33R0"))
      (libsource (lib "eagle-import") (part "R_0402_33R0"))
    )
    (comp (ref "R11")
      (value "33R0")
      (footprint "eagle-import:0402")
      (fields (field (name "PARTNO") "RMCF0402JT33R0"))
      (libsource (lib "eagle-import") (part "R_0402_33R0"))
    )
    (comp (ref "R12")
      (value "33R0")
      (footprint "eagle-import:0402")
      (fields (field (name "PARTNO") "RMCF0402JT33R0"))
      (libsource (lib "eagle-import") (part "R_0402_33R0"))
    )
    (comp (ref "R13")
      (value "10K0")
      (footprint "eagle-import:0402")
      (fields (field (name "PARTNO") "RMCF0402JT10K0"))
      (libsource (lib "eagle-import") (part "R_0402_10K0"))
    )
    (comp (ref "R14")
      (value "1K0")
      (footprint "eagle-import:0402")
      (fields (field (name "PARTNO") "CRG0402J1K0"))
      (libsource (lib "eagle-import") (part "R_0402_1K0"))
    )
    (comp (ref "R15")
      (value "1K0")
      (footprint "eagle-import:0402")
      (fields (field (name "PARTNO") "CRG0402J1K0"))
      (libsource (lib "eagle-import") (part "R_0402_1K0"))
    )
    (comp (ref "R16")
      (value "15K0")
      (footprint "eagle-import:0402")
      (fields (field (name "PARTNO") "RMCF0402JT15K0"))
      (libsource (lib "eagle-import") (part "R_0402_15K0"))
    )
    (comp (ref "R17")
      (value "27R0")
      (footprint "eagle-import:0402")
      (fields (field (name "PARTNO") "RMCF0402JT27R0"))
      (libsource (lib "eagle-import") (part "R_0402_27R0"))
    )
    (comp (ref "R18")
      (value "27R0")
      (footprint "eagle-import:0402")
      (fields (field (name "PARTNO") "RMCF0402JT27R0"))
      (libsource (lib "eagle-import") (part "R_0402_27R0"))
    )
    (comp (ref "R19")
      (value "10K0")
      (footprint "eagle-import:0402")
      (fields (field (name "PARTNO") "RMCF0402JT10K0"))
      (libsource (lib "eagle-import") (part "R_0402_10K0"))
    )
    (comp (ref "R20")
      (value "10K0")
      (footprint "eagle-import:0402")
      (fields (field (name "PARTNO") "RMCF0402JT10K0"))
      (libsource (lib "eagle-import") (part "R_0402_10K0"))
    )
    (comp (ref "R21")
      (value "30K0")
      (footprint "eagle-import:0402")
      (fields (field (name "PARTNO") "RC0402JR-0730KL"))
      (libsource (lib "eagle-import") (part "R_0402_30K0"))
    )
    (comp (ref "R22")
      (value "2K2")
      (footprint "eagle-import:0402")
      (fields (field (name "PARTNO") "RMCF0402JT2K20"))
      (libsource (lib "eagle-import") (part "R_0402_2K2"))
    )
    (comp (ref "R23")
      (value "10K0")
      (footprint "eagle-import:0402")
      (fields (field (name "PARTNO") "RMCF0402JT10K0"))
      (libsource (lib "eagle-import") (part "R_0402_10K0"))
    )
    (comp (ref "R24")
      (value "10K0")
      (footprint "eagle-import:0402")
      (fields (field (name "PARTNO") "RMCF0402JT10K0"))
      (libsource (lib "eagle-import") (part "R_0402_10K0"))
    )
    (comp (ref "R25")
      (value "100K")
      (footprint "eagle-import:0402")
      (libsource (lib "eagle-import") (part "R_0402"))
    )
    (comp (ref "R27")
      (value "100K")
      (footprint "eagle-import:0402")
      (libsource (lib "eagle-import") (part "R_0402"))
    )
    (comp (ref "R28")
      (value "2K2")
      (footprint "eagle-import:0402")
      (libsource (lib "eagle-import") (part "R_0402"))
    )
    (comp (ref "R29")
      (value "470R0")
      (footprint "eagle-import:0402")
      (libsource (lib "eagle-import") (part "R_0402"))
    )
    (comp (ref "R30")
      (value "470R0")
      (footprint "eagle-import:0402")
      (libsource (lib "eagle-import") (part "R_0402"))
    )
    (comp (ref "R31")
      (value "470R0")
      (footprint "eagle-import:0402")
      (fields (field (name "PARTNO") "RMCF0402JT470R"))
      (libsource (lib "eagle-import") (part "R_0402_470R0"))
    )
    (comp (ref "R32")
      (value "470R0")
      (footprint "eagle-import:0402")
      (fields (field (name "PARTNO") "RMCF0402JT470R"))
      (libsource (lib "eagle-import") (part "R_0402_470R0"))
    )
    (comp (ref "R33")
      (value "470R0")
      (footprint "eagle-import:0402")
      (fields (field (name "PARTNO") "RMCF0402JT470R"))
      (libsource (lib "eagle-import") (part "R_0402_470R0"))
    )
    (comp (ref "R34")
      (value "10K0")
      (footprint "eagle-import:0402")
      (fields (field (name "PARTNO") "RMCF0402JT10K0"))
      (libsource (lib "eagle-import") (part "R_0402_10K0"))
    )
    (comp (ref "R35")
      (value "2K2")
      (footprint "eagle-import:0402")
      (libsource (lib "eagle-import") (part "R_0402"))
    )
    (comp (ref "R36")
      (value "470R0")
      (footprint "eagle-import:0402")
      (fields (field (name "PARTNO") "RMCF0402JT470R"))
      (libsource (lib "eagle-import") (part "R_0402_470R0"))
    )
    (comp (ref "R37")
      (value "1k")
      (footprint "eagle-import:0805")
      (libsource (lib "eagle-import") (part "R_0805"))
    )
    (comp (ref "R38")
      (value "33R0")
      (footprint "eagle-import:0402")
      (fields (field (name "PARTNO") "RMCF0402JT33R0"))
      (libsource (lib "eagle-import") (part "R_0402_33R0"))
    )
    (comp (ref "R39")
      (value "33R0")
      (footprint "eagle-import:0402")
      (fields (field (name "PARTNO") "RMCF0402JT33R0"))
      (libsource (lib "eagle-import") (part "R_0402_33R0"))
    )
    (comp (ref "R40")
      (value "33R0")
      (footprint "eagle-import:0402")
      (fields (field (name "PARTNO") "RMCF0402JT33R0"))
      (libsource (lib "eagle-import") (part "R_0402_33R0"))
    )
    (comp (ref "R41")
      (value "1k")
      (footprint "eagle-import:0805")
      (libsource (lib "eagle-import") (part "R_0805"))
    )
    (comp (ref "R42")
      (value "1k")
      (footprint "eagle-import:0805")
      (libsource (lib "eagle-import") (part "R_0805"))
    )
    (comp (ref "R43")
      (value "1k")
      (footprint "eagle-import:0805")
      (libsource (lib "eagle-import") (part "R_0805"))
    )
    (comp (ref "R44")
      (value "33R0")
      (footprint "eagle-import:0402")
      (fields (field (name "PARTNO") "RMCF0402JT33R0"))
      (libsource (lib "eagle-import") (part "R_0402_33R0"))
    )
    (comp (ref "R45")
      (value "33R0")
      (footprint "eagle-import:0402")
      (fields (field (name "PARTNO") "RMCF0402JT33R0"))
      (libsource (lib "eagle-import") (part "R_0402_33R0"))
    )
    (comp (ref "R46")
      (value "33R0")
      (footprint "eagle-import:0402")
      (fields (field (name "PARTNO") "RMCF0402JT33R0"))
      (libsource (lib "eagle-import") (part "R_0402_33R0"))
    )
    (comp (ref "R47")
      (value "1k")
      (footprint "eagle-import:0805")
      (libsource (lib "eagle-import") (part "R_0805"))
    )
    (comp (ref "R48")
      (value "1k")
      (footprint "eagle-import:0805")
      (libsource (lib "eagle-import") (part "R_0805"))
    )
    (comp (ref "R49")
      (value "470R0")
      (footprint "eagle-import:0402")
      (libsource (lib "eagle-import") (part "R_0402"))
    )
    (comp (ref "R50")
      (value "470R0")
      (footprint "eagle-import:0402")
      (libsource (lib "eagle-import") (part "R_0402"))
    )
    (comp (ref "R51")
      (value "470R0")
      (footprint "eagle-import:0402")
      (fields (field (name "PARTNO") "RMCF0402JT470R"))
      (libsource (lib "eagle-import") (part "R_0402_470R0"))
    )
    (comp (ref "R52")
      (value "470R0")
      (footprint "eagle-import:0402")
      (fields (field (name "PARTNO") "RMCF0402JT470R"))
      (libsource (lib "eagle-import") (part "R_0402_470R0"))
    )
    (comp (ref "R53")
      (value "10K0")
      (footprint "eagle-import:0402")
      (fields (field (name "PARTNO") "RMCF0402JT10K0"))
      (libsource (lib "eagle-import") (part "R_0402_10K0"))
    )
    (comp (ref "R54")
      (value "2K2")
      (footprint "eagle-import:0402")
      (libsource (lib "eagle-import") (part "R_0402"))
    )
    (comp (ref "R55")
      (value "470R0")
      (footprint "eagle-import:0402")
      (fields (field (name "PARTNO") "RMCF0402JT470R"))
      (libsource (lib "eagle-import") (part "R_0402_470R0"))
    )
    (comp (ref "R56")
      (value "10K0")
      (footprint "eagle-import:0402")
      (fields (field (name "PARTNO") "RMCF0402JT10K0"))
      (libsource (lib "eagle-import") (part "R_0402_10K0"))
    )
    (comp (ref "R57")
      (value "2K2")
      (footprint "eagle-import:0402")
      (libsource (lib "eagle-import") (part "R_0402"))
    )
    (comp (ref "R58")
      (value "470R0")
      (footprint "eagle-import:0402")
      (fields (field (name "PARTNO") "RMCF0402JT470R"))
      (libsource (lib "eagle-import") (part "R_0402_470R0"))
    )
    (comp (ref "R59")
      (value "10K0")
      (footprint "eagle-import:0402")
      (fields (field (name "PARTNO") "RMCF0402JT10K0"))
      (libsource (lib "eagle-import") (part "R_0402_10K0"))
    )
    (comp (ref "R60")
      (value "2K2")
      (footprint "eagle-import:0402")
      (libsource (lib "eagle-import") (part "R_0402"))
    )
    (comp (ref "R61")
      (value "1k")
      (footprint "eagle-import:0805")
      (libsource (lib "eagle-import") (part "R_0805"))
    )
    (comp (ref "R62")
      (value "33R0")
      (footprint "eagle-import:0402")
      (fields (field (name "PARTNO") "RMCF0402JT33R0"))
      (libsource (lib "eagle-import") (part "R_0402_33R0"))
    )
    (comp (ref "R63")
      (value "33R0")
      (footprint "eagle-import:0402")
      (fields (field (name "PARTNO") "RMCF0402JT33R0"))
      (libsource (lib "eagle-import") (part "R_0402_33R0"))
    )
    (comp (ref "R64")
      (value "33R0")
      (footprint "eagle-import:0402")
      (fields (field (name "PARTNO") "RMCF0402JT33R0"))
      (libsource (lib "eagle-import") (part "R_0402_33R0"))
    )
    (comp (ref "R65")
      (value "1k")
      (footprint "eagle-import:0805")
      (libsource (lib "eagle-import") (part "R_0805"))
    )
    (comp (ref "R66")
      (value "1k")
      (footprint "eagle-import:0805")
      (libsource (lib "eagle-import") (part "R_0805"))
    )
    (comp (ref "R67")
      (value "1k")
      (footprint "eagle-import:0805")
      (libsource (lib "eagle-import") (part "R_0805"))
    )
    (comp (ref "R68")
      (value "33R0")
      (footprint "eagle-import:0402")
      (fields (field (name "PARTNO") "RMCF0402JT33R0"))
      (libsource (lib "eagle-import") (part "R_0402_33R0"))
    )
    (comp (ref "R69")
      (value "33R0")
      (footprint "eagle-import:0402")
      (fields (field (name "PARTNO") "RMCF0402JT33R0"))
      (libsource (lib "eagle-import") (part "R_0402_33R0"))
    )
    (comp (ref "R70")
      (value "33R0")
      (footprint "eagle-import:0402")
      (fields (field (name "PARTNO") "RMCF0402JT33R0"))
      (libsource (lib "eagle-import") (part "R_0402_33R0"))
    )
    (comp (ref "R71")
      (value "1k")
      (footprint "eagle-import:0805")
      (libsource (lib "eagle-import") (part "R_0805"))
    )
    (comp (ref "R72")
      (value "1k")
      (footprint "eagle-import:0805")
      (libsource (lib "eagle-import") (part "R_0805"))
    )
    (comp (ref "R73")
      (value "470R0")
      (footprint "eagle-import:0402")
      (fields (field (name "PARTNO") "RMCF0402JT470R"))
      (libsource (lib "eagle-import") (part "R_0402_470R0"))
    )
    (comp (ref "R74")
      (value "10K0")
      (footprint "eagle-import:0402")
      (fields (field (name "PARTNO") "RMCF0402JT10K0"))
      (libsource (lib "eagle-import") (part "R_0402_10K0"))
    )
    (comp (ref "R75")
      (value "2K2")
      (footprint "eagle-import:0402")
      (libsource (lib "eagle-import") (part "R_0402"))
    )
    (comp (ref "R76")
      (value "470R0")
      (footprint "eagle-import:0402")
      (fields (field (name "PARTNO") "RMCF0402JT470R"))
      (libsource (lib "eagle-import") (part "R_0402_470R0"))
    )
    (comp (ref "R77")
      (value "10K0")
      (footprint "eagle-import:0402")
      (fields (field (name "PARTNO") "RMCF0402JT10K0"))
      (libsource (lib "eagle-import") (part "R_0402_10K0"))
    )
    (comp (ref "R78")
      (value "2K2")
      (footprint "eagle-import:0402")
      (libsource (lib "eagle-import") (part "R_0402"))
    )
    (comp (ref "R79")
      (value "470R0")
      (footprint "eagle-import:0402")
      (fields (field (name "PARTNO") "RMCF0402JT470R"))
      (libsource (lib "eagle-import") (part "R_0402_470R0"))
    )
    (comp (ref "R80")
      (value "10K0")
      (footprint "eagle-import:0402")
      (fields (field (name "PARTNO") "RMCF0402JT10K0"))
      (libsource (lib "eagle-import") (part "R_0402_10K0"))
    )
    (comp (ref "R81")
      (value "2K2")
      (footprint "eagle-import:0402")
      (libsource (lib "eagle-import") (part "R_0402"))
    )
    (comp (ref "R82")
      (value "470R0")
      (footprint "eagle-import:0402")
      (fields (field (name "PARTNO") "RMCF0402JT470R"))
      (libsource (lib "eagle-import") (part "R_0402_470R0"))
    )
    (comp (ref "R83")
      (value "10K0")
      (footprint "eagle-import:0402")
      (fields (field (name "PARTNO") "RMCF0402JT10K0"))
      (libsource (lib "eagle-import") (part "R_0402_10K0"))
    )
    (comp (ref "R84")
      (value "2K2")
      (footprint "eagle-import:0402")
      (libsource (lib "eagle-import") (part "R_0402"))
    )
    (comp (ref "R85")
      (value "1k")
      (footprint "eagle-import:0805")
      (libsource (lib "eagle-import") (part "R_0805"))
    )
    (comp (ref "R86")
      (value "33R0")
      (footprint "eagle-import:0402")
      (fields (field (name "PARTNO") "RMCF0402JT33R0"))
      (libsource (lib "eagle-import") (part "R_0402_33R0"))
    )
    (comp (ref "R87")
      (value "33R0")
      (footprint "eagle-import:0402")
      (fields (field (name "PARTNO") "RMCF0402JT33R0"))
      (libsource (lib "eagle-import") (part "R_0402_33R0"))
    )
    (comp (ref "R88")
      (value "33R0")
      (footprint "eagle-import:0402")
      (fields (field (name "PARTNO") "RMCF0402JT33R0"))
      (libsource (lib "eagle-import") (part "R_0402_33R0"))
    )
    (comp (ref "R89")
      (value "1k")
      (footprint "eagle-import:0805")
      (libsource (lib "eagle-import") (part "R_0805"))
    )
    (comp (ref "R90")
      (value "1k")
      (footprint "eagle-import:0805")
      (libsource (lib "eagle-import") (part "R_0805"))
    )
    (comp (ref "R91")
      (value "1k")
      (footprint "eagle-import:0805")
      (libsource (lib "eagle-import") (part "R_0805"))
    )
    (comp (ref "R92")
      (value "33R0")
      (footprint "eagle-import:0402")
      (fields (field (name "PARTNO") "RMCF0402JT33R0"))
      (libsource (lib "eagle-import") (part "R_0402_33R0"))
    )
    (comp (ref "R93")
      (value "33R0")
      (footprint "eagle-import:0402")
      (fields (field (name "PARTNO") "RMCF0402JT33R0"))
      (libsource (lib "eagle-import") (part "R_0402_33R0"))
    )
    (comp (ref "R94")
      (value "33R0")
      (footprint "eagle-import:0402")
      (fields (field (name "PARTNO") "RMCF0402JT33R0"))
      (libsource (lib "eagle-import") (part "R_0402_33R0"))
    )
    (comp (ref "R95")
      (value "1k")
      (footprint "eagle-import:0805")
      (libsource (lib "eagle-import") (part "R_0805"))
    )
    (comp (ref "R96")
      (value "1k")
      (footprint "eagle-import:0805")
      (libsource (lib "eagle-import") (part "R_0805"))
    )
    (comp (ref "R97")
      (value "470R0")
      (footprint "eagle-import:0402")
      (fields (field (name "PARTNO") "RMCF0402JT470R"))
      (libsource (lib "eagle-import") (part "R_0402_470R0"))
    )
    (comp (ref "R98")
      (value "10K0")
      (footprint "eagle-import:0402")
      (fields (field (name "PARTNO") "RMCF0402JT10K0"))
      (libsource (lib "eagle-import") (part "R_0402_10K0"))
    )
    (comp (ref "R99")
      (value "2K2")
      (footprint "eagle-import:0402")
      (libsource (lib "eagle-import") (part "R_0402"))
    )
    (comp (ref "R100")
      (value "470R0")
      (footprint "eagle-import:0402")
      (fields (field (name "PARTNO") "RMCF0402JT470R"))
      (libsource (lib "eagle-import") (part "R_0402_470R0"))
    )
    (comp (ref "R101")
      (value "10K0")
      (footprint "eagle-import:0402")
      (fields (field (name "PARTNO") "RMCF0402JT10K0"))
      (libsource (lib "eagle-import") (part "R_0402_10K0"))
    )
    (comp (ref "R102")
      (value "100K")
      (footprint "eagle-import:0402")
      (libsource (lib "eagle-import") (part "R_0402"))
    )
    (comp (ref "R103")
      (value "100K")
      (footprint "eagle-import:0402")
      (libsource (lib "eagle-import") (part "R_0402"))
    )
    (comp (ref "R105")
      (value "100K")
      (footprint "eagle-import:0402")
      (libsource (lib "eagle-import") (part "R_0402"))
    )
    (comp (ref "R106")
      (value "100K")
      (footprint "eagle-import:0402")
      (libsource (lib "eagle-import") (part "R_0402"))
    )
    (comp (ref "R107")
      (value "100K")
      (footprint "eagle-import:0402")
      (libsource (lib "eagle-import") (part "R_0402"))
    )
    (comp (ref "R108")
      (value "100K")
      (footprint "eagle-import:0402")
      (libsource (lib "eagle-import") (part "R_0402"))
    )
    (comp (ref "R109")
      (value "1k")
      (footprint "eagle-import:0805")
      (libsource (lib "eagle-import") (part "R_0805"))
    )
    (comp (ref "R110")
      (value "33R0")
      (footprint "eagle-import:0402")
      (fields (field (name "PARTNO") "RMCF0402JT33R0"))
      (libsource (lib "eagle-import") (part "R_0402_33R0"))
    )
    (comp (ref "R111")
      (value "33R0")
      (footprint "eagle-import:0402")
      (fields (field (name "PARTNO") "RMCF0402JT33R0"))
      (libsource (lib "eagle-import") (part "R_0402_33R0"))
    )
    (comp (ref "R112")
      (value "33R0")
      (footprint "eagle-import:0402")
      (fields (field (name "PARTNO") "RMCF0402JT33R0"))
      (libsource (lib "eagle-import") (part "R_0402_33R0"))
    )
    (comp (ref "R113")
      (value "1k")
      (footprint "eagle-import:0805")
      (libsource (lib "eagle-import") (part "R_0805"))
    )
    (comp (ref "R114")
      (value "1k")
      (footprint "eagle-import:0805")
      (libsource (lib "eagle-import") (part "R_0805"))
    )
    (comp (ref "R115")
      (value "1k")
      (footprint "eagle-import:0805")
      (libsource (lib "eagle-import") (part "R_0805"))
    )
    (comp (ref "R116")
      (value "33R0")
      (footprint "eagle-import:0402")
      (fields (field (name "PARTNO") "RMCF0402JT33R0"))
      (libsource (lib "eagle-import") (part "R_0402_33R0"))
    )
    (comp (ref "R117")
      (value "33R0")
      (footprint "eagle-import:0402")
      (fields (field (name "PARTNO") "RMCF0402JT33R0"))
      (libsource (lib "eagle-import") (part "R_0402_33R0"))
    )
    (comp (ref "R118")
      (value "33R0")
      (footprint "eagle-import:0402")
      (fields (field (name "PARTNO") "RMCF0402JT33R0"))
      (libsource (lib "eagle-import") (part "R_0402_33R0"))
    )
    (comp (ref "R119")
      (value "1k")
      (footprint "eagle-import:0805")
      (libsource (lib "eagle-import") (part "R_0805"))
    )
    (comp (ref "R120")
      (value "1k")
      (footprint "eagle-import:0805")
      (libsource (lib "eagle-import") (part "R_0805"))
    )
    (comp (ref "R133")
      (value "1k")
      (footprint "eagle-import:0805")
      (libsource (lib "eagle-import") (part "R_0805"))
    )
    (comp (ref "R134")
      (value "33R0")
      (footprint "eagle-import:0402")
      (fields (field (name "PARTNO") "RMCF0402JT33R0"))
      (libsource (lib "eagle-import") (part "R_0402_33R0"))
    )
    (comp (ref "R135")
      (value "33R0")
      (footprint "eagle-import:0402")
      (fields (field (name "PARTNO") "RMCF0402JT33R0"))
      (libsource (lib "eagle-import") (part "R_0402_33R0"))
    )
    (comp (ref "R136")
      (value "33R0")
      (footprint "eagle-import:0402")
      (fields (field (name "PARTNO") "RMCF0402JT33R0"))
      (libsource (lib "eagle-import") (part "R_0402_33R0"))
    )
    (comp (ref "R137")
      (value "1k")
      (footprint "eagle-import:0805")
      (libsource (lib "eagle-import") (part "R_0805"))
    )
    (comp (ref "R138")
      (value "1k")
      (footprint "eagle-import:0805")
      (libsource (lib "eagle-import") (part "R_0805"))
    )
    (comp (ref "R139")
      (value "1k")
      (footprint "eagle-import:0805")
      (libsource (lib "eagle-import") (part "R_0805"))
    )
    (comp (ref "R140")
      (value "33R0")
      (footprint "eagle-import:0402")
      (fields (field (name "PARTNO") "RMCF0402JT33R0"))
      (libsource (lib "eagle-import") (part "R_0402_33R0"))
    )
    (comp (ref "R141")
      (value "33R0")
      (footprint "eagle-import:0402")
      (fields (field (name "PARTNO") "RMCF0402JT33R0"))
      (libsource (lib "eagle-import") (part "R_0402_33R0"))
    )
    (comp (ref "R142")
      (value "33R0")
      (footprint "eagle-import:0402")
      (fields (field (name "PARTNO") "RMCF0402JT33R0"))
      (libsource (lib "eagle-import") (part "R_0402_33R0"))
    )
    (comp (ref "R143")
      (value "1k")
      (footprint "eagle-import:0805")
      (libsource (lib "eagle-import") (part "R_0805"))
    )
    (comp (ref "R144")
      (value "1k")
      (footprint "eagle-import:0805")
      (libsource (lib "eagle-import") (part "R_0805"))
    )
    (comp (ref "R157")
      (value "1k")
      (footprint "eagle-import:0805")
      (libsource (lib "eagle-import") (part "R_0805"))
    )
    (comp (ref "R158")
      (value "33R0")
      (footprint "eagle-import:0402")
      (fields (field (name "PARTNO") "RMCF0402JT33R0"))
      (libsource (lib "eagle-import") (part "R_0402_33R0"))
    )
    (comp (ref "R159")
      (value "33R0")
      (footprint "eagle-import:0402")
      (fields (field (name "PARTNO") "RMCF0402JT33R0"))
      (libsource (lib "eagle-import") (part "R_0402_33R0"))
    )
    (comp (ref "R160")
      (value "33R0")
      (footprint "eagle-import:0402")
      (fields (field (name "PARTNO") "RMCF0402JT33R0"))
      (libsource (lib "eagle-import") (part "R_0402_33R0"))
    )
    (comp (ref "R161")
      (value "1k")
      (footprint "eagle-import:0805")
      (libsource (lib "eagle-import") (part "R_0805"))
    )
    (comp (ref "R162")
      (value "1k")
      (footprint "eagle-import:0805")
      (libsource (lib "eagle-import") (part "R_0805"))
    )
    (comp (ref "R163")
      (value "1k")
      (footprint "eagle-import:0805")
      (libsource (lib "eagle-import") (part "R_0805"))
    )
    (comp (ref "R164")
      (value "33R0")
      (footprint "eagle-import:0402")
      (fields (field (name "PARTNO") "RMCF0402JT33R0"))
      (libsource (lib "eagle-import") (part "R_0402_33R0"))
    )
    (comp (ref "R165")
      (value "33R0")
      (footprint "eagle-import:0402")
      (fields (field (name "PARTNO") "RMCF0402JT33R0"))
      (libsource (lib "eagle-import") (part "R_0402_33R0"))
    )
    (comp (ref "R166")
      (value "33R0")
      (footprint "eagle-import:0402")
      (fields (field (name "PARTNO") "RMCF0402JT33R0"))
      (libsource (lib "eagle-import") (part "R_0402_33R0"))
    )
    (comp (ref "R167")
      (value "1k")
      (footprint "eagle-import:0805")
      (libsource (lib "eagle-import") (part "R_0805"))
    )
    (comp (ref "R168")
      (value "1k")
      (footprint "eagle-import:0805")
      (libsource (lib "eagle-import") (part "R_0805"))
    )
    (comp (ref "RJ1")
      (value "RJ45")
      (footprint "eagle-import:RJ45_TH_ELEC")
      (fields (field (name "PARTNO") "13F-64GYD2PL2NL"))
      (libsource (lib "eagle-import") (part "RJ45_WITH_ELEC"))
    )
    (comp (ref "TH01")
      (value "CONN_530470210_PICOBLADE_X_2")
      (footprint "eagle-import:CON_530470210_MOL")
      (fields
        (field (name "MANUFACTURER_PART_NUMBER") "530470210")
        (field (name "COPYRIGHT") "Copyright (C) 2022 Ultra Librarian. All rights reserved.")
      )
      (libsource (lib "eagle-import") (part "CONN_530470210_PICOBLADE_X_2"))
    )
    (comp (ref "TH02")
      (value "CONN_530470210_PICOBLADE_X_2")
      (footprint "eagle-import:CON_530470210_MOL")
      (fields
        (field (name "MANUFACTURER_PART_NUMBER") "530470210")
        (field (name "COPYRIGHT") "Copyright (C) 2022 Ultra Librarian. All rights reserved.")
      )
      (libsource (lib "eagle-import") (part "CONN_530470210_PICOBLADE_X_2"))
    )
    (comp (ref "TH03")
      (value "CONN_530470210_PICOBLADE_X_2")
      (footprint "eagle-import:CON_530470210_MOL")
      (fields
        (field (name "MANUFACTURER_PART_NUMBER") "530470210")
        (field (name "COPYRIGHT") "Copyright (C) 2022 Ultra Librarian. All rights reserved.")
      )
      (libsource (lib "eagle-import") (part "CONN_530470210_PICOBLADE_X_2"))
    )
    (comp (ref "TH04")
      (value "CONN_530470210_PICOBLADE_X_2")
      (footprint "eagle-import:CON_530470210_MOL")
      (fields
        (field (name "MANUFACTURER_PART_NUMBER") "530470210")
        (field (name "COPYRIGHT") "Copyright (C) 2022 Ultra Librarian. All rights reserved.")
      )
      (libsource (lib "eagle-import") (part "CONN_530470210_PICOBLADE_X_2"))
    )
    (comp (ref "TH05")
      (value "CONN_530470210_PICOBLADE_X_2")
      (footprint "eagle-import:CON_530470210_MOL")
      (fields
        (field (name "MANUFACTURER_PART_NUMBER") "530470210")
        (field (name "COPYRIGHT") "Copyright (C) 2022 Ultra Librarian. All rights reserved.")
      )
      (libsource (lib "eagle-import") (part "CONN_530470210_PICOBLADE_X_2"))
    )
    (comp (ref "TH06")
      (value "CONN_530470210_PICOBLADE_X_2")
      (footprint "eagle-import:CON_530470210_MOL")
      (fields
        (field (name "MANUFACTURER_PART_NUMBER") "530470210")
        (field (name "COPYRIGHT") "Copyright (C) 2022 Ultra Librarian. All rights reserved.")
      )
      (libsource (lib "eagle-import") (part "CONN_530470210_PICOBLADE_X_2"))
    )
    (comp (ref "TH07")
      (value "CONN_530470210_PICOBLADE_X_2")
      (footprint "eagle-import:CON_530470210_MOL")
      (fields
        (field (name "MANUFACTURER_PART_NUMBER") "530470210")
        (field (name "COPYRIGHT") "Copyright (C) 2022 Ultra Librarian. All rights reserved.")
      )
      (libsource (lib "eagle-import") (part "CONN_530470210_PICOBLADE_X_2"))
    )
    (comp (ref "TH08")
      (value "CONN_530470210_PICOBLADE_X_2")
      (footprint "eagle-import:CON_530470210_MOL")
      (fields
        (field (name "MANUFACTURER_PART_NUMBER") "530470210")
        (field (name "COPYRIGHT") "Copyright (C) 2022 Ultra Librarian. All rights reserved.")
      )
      (libsource (lib "eagle-import") (part "CONN_530470210_PICOBLADE_X_2"))
    )
    (comp (ref "U$1")
      (value "RELAY_KYOTO_KF0604D")
      (footprint "eagle-import:RELAY_KYOTO_KF0604D")
      (libsource (lib "eagle-import") (part "RELAY_KYOTO_KF0604D"))
    )
    (comp (ref "U$2")
      (value "RELAY_KYOTO_KF0604D")
      (footprint "eagle-import:RELAY_KYOTO_KF0604D")
      (libsource (lib "eagle-import") (part "RELAY_KYOTO_KF0604D"))
    )
    (comp (ref "U$7")
      (value "RELAY_KYOTO_KF0604D")
      (footprint "eagle-import:RELAY_KYOTO_KF0604D")
      (libsource (lib "eagle-import") (part "RELAY_KYOTO_KF0604D"))
    )
    (comp (ref "U$8")
      (value "RELAY_KYOTO_KF0604D")
      (footprint "eagle-import:RELAY_KYOTO_KF0604D")
      (libsource (lib "eagle-import") (part "RELAY_KYOTO_KF0604D"))
    )
    (comp (ref "U1")
      (value "KSZ8081_QFN_24")
      (footprint "eagle-import:QFN-24-M")
      (fields (field (name "PARTNO") "KSZ8081RNACA"))
      (libsource (lib "eagle-import") (part "KSZ8081RNACAQFN-24-M"))
    )
    (comp (ref "U2")
      (value "AP2151DWG-7")
      (footprint "eagle-import:SOT-23-5")
      (fields (field (name "PARTNO") "AP2151WG-7"))
      (libsource (lib "eagle-import") (part "AP2151DWG-7"))
    )
    (comp (ref "U3")
      (value "S7G2LQFP176")
      (footprint "eagle-import:LQFP176_24X24")
      (fields (field (name "PARTNO") "R7FS7G27H3A01CFC#AA0"))
      (libsource (lib "eagle-import") (part "RENESAS_S7G2_X_176"))
    )
    (comp (ref "U5")
      (value "NPN")
      (footprint "eagle-import:SOT323")
      (fields (field (name "PARTNO") "BC846BW_NPN"))
      (libsource (lib "eagle-import") (part "BC846BW"))
    )
    (comp (ref "U6")
      (value "NPN")
      (footprint "eagle-import:SOT323")
      (fields (field (name "PARTNO") "BC846BW_NPN"))
      (libsource (lib "eagle-import") (part "BC846BW"))
    )
    (comp (ref "U7")
      (value "NPN")
      (footprint "eagle-import:SOT323")
      (fields (field (name "PARTNO") "BC846BW_NPN"))
      (libsource (lib "eagle-import") (part "BC846BW"))
    )
    (comp (ref "U8")
      (value "NPN")
      (footprint "eagle-import:SOT323")
      (fields (field (name "PARTNO") "BC846BW_NPN"))
      (libsource (lib "eagle-import") (part "BC846BW"))
    )
    (comp (ref "U9")
      (value "NPN")
      (footprint "eagle-import:SOT323")
      (fields (field (name "PARTNO") "BC846BW_NPN"))
      (libsource (lib "eagle-import") (part "BC846BW"))
    )
    (comp (ref "U10")
      (value "NPN")
      (footprint "eagle-import:SOT323")
      (fields (field (name "PARTNO") "BC846BW_NPN"))
      (libsource (lib "eagle-import") (part "BC846BW"))
    )
    (comp (ref "U11")
      (value "NPN")
      (footprint "eagle-import:SOT323")
      (fields (field (name "PARTNO") "BC846BW_NPN"))
      (libsource (lib "eagle-import") (part "BC846BW"))
    )
    (comp (ref "U12")
      (value "NPN")
      (footprint "eagle-import:SOT323")
      (fields (field (name "PARTNO") "BC846BW_NPN"))
      (libsource (lib "eagle-import") (part "BC846BW"))
    )
    (comp (ref "U13")
      (value "NPN")
      (footprint "eagle-import:SOT323")
      (fields (field (name "PARTNO") "BC846BW_NPN"))
      (libsource (lib "eagle-import") (part "BC846BW"))
    )
    (comp (ref "U14")
      (value "NPN")
      (footprint "eagle-import:SOT323")
      (fields (field (name "PARTNO") "BC846BW_NPN"))
      (libsource (lib "eagle-import") (part "BC846BW"))
    )
    (comp (ref "U15")
      (value "NPN")
      (footprint "eagle-import:SOT323")
      (fields (field (name "PARTNO") "BC846BW_NPN"))
      (libsource (lib "eagle-import") (part "BC846BW"))
    )
    (comp (ref "U16")
      (value "NPN")
      (footprint "eagle-import:SOT323")
      (fields (field (name "PARTNO") "BC846BW_NPN"))
      (libsource (lib "eagle-import") (part "BC846BW"))
    )
    (comp (ref "U17")
      (value "NPN")
      (footprint "eagle-import:SOT323")
      (fields (field (name "PARTNO") "BC846BW_NPN"))
      (libsource (lib "eagle-import") (part "BC846BW"))
    )
    (comp (ref "U18")
      (value "NPN")
      (footprint "eagle-import:SOT323")
      (fields (field (name "PARTNO") "BC846BW_NPN"))
      (libsource (lib "eagle-import") (part "BC846BW"))
    )
    (comp (ref "U19")
      (value "NPN")
      (footprint "eagle-import:SOT323")
      (fields (field (name "PARTNO") "BC846BW_NPN"))
      (libsource (lib "eagle-import") (part "BC846BW"))
    )
    (comp (ref "U20")
      (value "NPN")
      (footprint "eagle-import:SOT323")
      (fields (field (name "PARTNO") "BC846BW_NPN"))
      (libsource (lib "eagle-import") (part "BC846BW"))
    )
    (comp (ref "U21")
      (value "NPN")
      (footprint "eagle-import:SOT323")
      (fields (field (name "PARTNO") "BC846BW_NPN"))
      (libsource (lib "eagle-import") (part "BC846BW"))
    )
    (comp (ref "U22")
      (value "NPN")
      (footprint "eagle-import:SOT323")
      (fields (field (name "PARTNO") "BC846BW_NPN"))
      (libsource (lib "eagle-import") (part "BC846BW"))
    )
    (comp (ref "U23")
      (value "NPN")
      (footprint "eagle-import:SOT323")
      (fields (field (name "PARTNO") "BC846BW_NPN"))
      (libsource (lib "eagle-import") (part "BC846BW"))
    )
    (comp (ref "U24")
      (value "NPN")
      (footprint "eagle-import:SOT323")
      (fields (field (name "PARTNO") "BC846BW_NPN"))
      (libsource (lib "eagle-import") (part "BC846BW"))
    )
    (comp (ref "U25")
      (value "NPN")
      (footprint "eagle-import:SOT323")
      (fields (field (name "PARTNO") "BC846BW_NPN"))
      (libsource (lib "eagle-import") (part "BC846BW"))
    )
    (comp (ref "U26")
      (value "NPN")
      (footprint "eagle-import:SOT323")
      (fields (field (name "PARTNO") "BC846BW_NPN"))
      (libsource (lib "eagle-import") (part "BC846BW"))
    )
    (comp (ref "U27")
      (value "NPN")
      (footprint "eagle-import:SOT323")
      (fields (field (name "PARTNO") "BC846BW_NPN"))
      (libsource (lib "eagle-import") (part "BC846BW"))
    )
    (comp (ref "U28")
      (value "NPN")
      (footprint "eagle-import:SOT323")
      (fields (field (name "PARTNO") "BC846BW_NPN"))
      (libsource (lib "eagle-import") (part "BC846BW"))
    )
    (comp (ref "U29")
      (value "NPN")
      (footprint "eagle-import:SOT323")
      (fields (field (name "PARTNO") "BC846BW_NPN"))
      (libsource (lib "eagle-import") (part "BC846BW"))
    )
    (comp (ref "U30")
      (value "NPN")
      (footprint "eagle-import:SOT323")
      (fields (field (name "PARTNO") "BC846BW_NPN"))
      (libsource (lib "eagle-import") (part "BC846BW"))
    )
    (comp (ref "U34")
      (value "NPN")
      (footprint "eagle-import:SOT323")
      (fields (field (name "PARTNO") "BC846BW_NPN"))
      (libsource (lib "eagle-import") (part "BC846BW"))
    )
    (comp (ref "U35")
      (value "NPN")
      (footprint "eagle-import:SOT323")
      (fields (field (name "PARTNO") "BC846BW_NPN"))
      (libsource (lib "eagle-import") (part "BC846BW"))
    )
    (comp (ref "U36")
      (value "NPN")
      (footprint "eagle-import:SOT323")
      (fields (field (name "PARTNO") "BC846BW_NPN"))
      (libsource (lib "eagle-import") (part "BC846BW"))
    )
    (comp (ref "U37")
      (value "NPN")
      (footprint "eagle-import:SOT323")
      (fields (field (name "PARTNO") "BC846BW_NPN"))
      (libsource (lib "eagle-import") (part "BC846BW"))
    )
    (comp (ref "U38")
      (value "NPN")
      (footprint "eagle-import:SOT323")
      (fields (field (name "PARTNO") "BC846BW_NPN"))
      (libsource (lib "eagle-import") (part "BC846BW"))
    )
    (comp (ref "U39")
      (value "NPN")
      (footprint "eagle-import:SOT323")
      (fields (field (name "PARTNO") "BC846BW_NPN"))
      (libsource (lib "eagle-import") (part "BC846BW"))
    )
    (comp (ref "U46")
      (value "NPN")
      (footprint "eagle-import:SOT323")
      (fields (field (name "PARTNO") "BC846BW_NPN"))
      (libsource (lib "eagle-import") (part "BC846BW"))
    )
    (comp (ref "U47")
      (value "NPN")
      (footprint "eagle-import:SOT323")
      (fields (field (name "PARTNO") "BC846BW_NPN"))
      (libsource (lib "eagle-import") (part "BC846BW"))
    )
    (comp (ref "U48")
      (value "NPN")
      (footprint "eagle-import:SOT323")
      (fields (field (name "PARTNO") "BC846BW_NPN"))
      (libsource (lib "eagle-import") (part "BC846BW"))
    )
    (comp (ref "U49")
      (value "NPN")
      (footprint "eagle-import:SOT323")
      (fields (field (name "PARTNO") "BC846BW_NPN"))
      (libsource (lib "eagle-import") (part "BC846BW"))
    )
    (comp (ref "U50")
      (value "NPN")
      (footprint "eagle-import:SOT323")
      (fields (field (name "PARTNO") "BC846BW_NPN"))
      (libsource (lib "eagle-import") (part "BC846BW"))
    )
    (comp (ref "U51")
      (value "NPN")
      (footprint "eagle-import:SOT323")
      (fields (field (name "PARTNO") "BC846BW_NPN"))
      (libsource (lib "eagle-import") (part "BC846BW"))
    )
    (comp (ref "U58")
      (value "NPN")
      (footprint "eagle-import:SOT323")
      (fields (field (name "PARTNO") "BC846BW_NPN"))
      (libsource (lib "eagle-import") (part "BC846BW"))
    )
    (comp (ref "U59")
      (value "NPN")
      (footprint "eagle-import:SOT323")
      (fields (field (name "PARTNO") "BC846BW_NPN"))
      (libsource (lib "eagle-import") (part "BC846BW"))
    )
    (comp (ref "U60")
      (value "NPN")
      (footprint "eagle-import:SOT323")
      (fields (field (name "PARTNO") "BC846BW_NPN"))
      (libsource (lib "eagle-import") (part "BC846BW"))
    )
    (comp (ref "U61")
      (value "NPN")
      (footprint "eagle-import:SOT323")
      (fields (field (name "PARTNO") "BC846BW_NPN"))
      (libsource (lib "eagle-import") (part "BC846BW"))
    )
    (comp (ref "U62")
      (value "NPN")
      (footprint "eagle-import:SOT323")
      (fields (field (name "PARTNO") "BC846BW_NPN"))
      (libsource (lib "eagle-import") (part "BC846BW"))
    )
    (comp (ref "U63")
      (value "NPN")
      (footprint "eagle-import:SOT323")
      (fields (field (name "PARTNO") "BC846BW_NPN"))
      (libsource (lib "eagle-import") (part "BC846BW"))
    )
    (comp (ref "U70")
      (value "NPN")
      (footprint "eagle-import:SOT323")
      (fields (field (name "PARTNO") "BC846BW_NPN"))
      (libsource (lib "eagle-import") (part "BC846BW"))
    )
    (comp (ref "U71")
      (value "NPN")
      (footprint "eagle-import:SOT323")
      (fields (field (name "PARTNO") "BC846BW_NPN"))
      (libsource (lib "eagle-import") (part "BC846BW"))
    )
    (comp (ref "U72")
      (value "NPN")
      (footprint "eagle-import:SOT323")
      (fields (field (name "PARTNO") "BC846BW_NPN"))
      (libsource (lib "eagle-import") (part "BC846BW"))
    )
    (comp (ref "U73")
      (value "NPN")
      (footprint "eagle-import:SOT323")
      (fields (field (name "PARTNO") "BC846BW_NPN"))
      (libsource (lib "eagle-import") (part "BC846BW"))
    )
    (comp (ref "U74")
      (value "NPN")
      (footprint "eagle-import:SOT323")
      (fields (field (name "PARTNO") "BC846BW_NPN"))
      (libsource (lib "eagle-import") (part "BC846BW"))
    )
    (comp (ref "U75")
      (value "NPN")
      (footprint "eagle-import:SOT323")
      (fields (field (name "PARTNO") "BC846BW_NPN"))
      (libsource (lib "eagle-import") (part "BC846BW"))
    )
    (comp (ref "X1")
      (value "25MHz")
      (footprint "eagle-import:SMD_3225")
      (fields (field (name "PARTNO") "FA-238 25.0000MB-B3"))
      (libsource (lib "eagle-import") (part "XTAL_25_MHZ"))
    )
    (comp (ref "X2")
      (value "24MHz")
      (footprint "eagle-import:SMD_3225")
      (fields (field (name "PARTNO") "FA-238 24.0000MB-C3 "))
      (libsource (lib "eagle-import") (part "XTAL_24_MHZ"))
    )
    (comp (ref "X3")
      (value "32.768KHz")
      (footprint "eagle-import:SMD_X_2_PADS")
      (fields (field (name "PARTNO") "ABS07-32.768KHZ-T"))
      (libsource (lib "eagle-import") (part "XTAL_32.768KHZ"))
    )
  )
  (nets
    (net (code "1") (name "A_A_DIR") (class "Default")
      (node (ref "R111") (pin "P$1") (pinfunction "1_P$1") (pintype "passive"))
      (node (ref "U3") (pin "73") (pinfunction "P9_5_73") (pintype "bidirectional"))
    )
    (net (code "2") (name "A_A_ENABLE") (class "Default")
      (node (ref "R112") (pin "P$1") (pinfunction "1_P$1") (pintype "passive"))
      (node (ref "U3") (pin "72") (pinfunction "P9_6_72") (pintype "bidirectional"))
    )
    (net (code "3") (name "A_A_HLFB_OUT") (class "Default")
      (node (ref "J25") (pin "5") (pinfunction "5-HLFB-_5") (pintype "passive"))
    )
    (net (code "4") (name "A_A_MI_DIR") (class "Default")
      (node (ref "J25") (pin "7") (pinfunction "7-INPUT_A-_7") (pintype "passive"))
      (node (ref "R113") (pin "1") (pinfunction "1_1") (pintype "passive"))
      (node (ref "U47") (pin "3") (pinfunction "C(3)_3") (pintype "input"))
    )
    (net (code "5") (name "A_A_MI_ENABLE") (class "Default")
      (node (ref "J25") (pin "8") (pinfunction "8-ENABLE-_8") (pintype "passive"))
      (node (ref "R114") (pin "1") (pinfunction "1_1") (pintype "passive"))
      (node (ref "U48") (pin "3") (pinfunction "C(3)_3") (pintype "input"))
    )
    (net (code "6") (name "A_A_MI_STEP") (class "Default")
      (node (ref "J25") (pin "6") (pinfunction "6-INPUT_B-_6") (pintype "passive"))
      (node (ref "R109") (pin "1") (pinfunction "1_1") (pintype "passive"))
      (node (ref "U46") (pin "3") (pinfunction "C(3)_3") (pintype "input"))
    )
    (net (code "7") (name "A_A_STEP") (class "Default")
      (node (ref "R110") (pin "P$1") (pinfunction "1_P$1") (pintype "passive"))
      (node (ref "U3") (pin "74") (pinfunction "P3_12_74") (pintype "bidirectional"))
    )
    (net (code "8") (name "A_B_DIR") (class "Default")
      (node (ref "R117") (pin "P$1") (pinfunction "1_P$1") (pintype "passive"))
      (node (ref "U3") (pin "76") (pinfunction "P3_10_76") (pintype "bidirectional"))
    )
    (net (code "9") (name "A_B_ENABLE") (class "Default")
      (node (ref "R118") (pin "P$1") (pinfunction "1_P$1") (pintype "passive"))
      (node (ref "U3") (pin "75") (pinfunction "P3_11_75") (pintype "bidirectional"))
    )
    (net (code "10") (name "A_B_HLFB_OUT") (class "Default")
      (node (ref "J26") (pin "5") (pinfunction "5-HLFB-_5") (pintype "passive"))
    )
    (net (code "11") (name "A_B_MI_DIR") (class "Default")
      (node (ref "J26") (pin "7") (pinfunction "7-INPUT_A-_7") (pintype "passive"))
      (node (ref "R119") (pin "1") (pinfunction "1_1") (pintype "passive"))
      (node (ref "U50") (pin "3") (pinfunction "C(3)_3") (pintype "input"))
    )
    (net (code "12") (name "A_B_MI_ENABLE") (class "Default")
      (node (ref "J26") (pin "8") (pinfunction "8-ENABLE-_8") (pintype "passive"))
      (node (ref "R120") (pin "1") (pinfunction "1_1") (pintype "passive"))
      (node (ref "U51") (pin "3") (pinfunction "C(3)_3") (pintype "input"))
    )
    (net (code "13") (name "A_B_MI_STEP") (class "Default")
      (node (ref "J26") (pin "6") (pinfunction "6-INPUT_B-_6") (pintype "passive"))
      (node (ref "R115") (pin "1") (pinfunction "1_1") (pintype "passive"))
      (node (ref "U49") (pin "3") (pinfunction "C(3)_3") (pintype "input"))
    )
    (net (code "14") (name "A_B_STEP") (class "Default")
      (node (ref "R116") (pin "P$1") (pinfunction "1_P$1") (pintype "passive"))
      (node (ref "U3") (pin "77") (pinfunction "P3_9_77") (pintype "bidirectional"))
    )
    (net (code "15") (name "B_MI_DIR") (class "Default")
      (node (ref "J34") (pin "7") (pinfunction "7-INPUT_A-_7") (pintype "passive"))
      (node (ref "R167") (pin "1") (pinfunction "1_1") (pintype "passive"))
      (node (ref "U74") (pin "3") (pinfunction "C(3)_3") (pintype "input"))
    )
    (net (code "16") (name "C58") (class "Default")
      (node (ref "C12") (pin "P$1") (pinfunction "1_P$1") (pintype "passive"))
      (node (ref "RJ1") (pin "4") (pinfunction "CT1_4") (pintype "bidirectional"))
    )
    (net (code "17") (name "C60") (class "Default")
      (node (ref "C13") (pin "P$1") (pinfunction "1_P$1") (pintype "passive"))
      (node (ref "RJ1") (pin "5") (pinfunction "CT2_5") (pintype "bidirectional"))
    )
    (net (code "18") (name "CRS_DV") (class "Default")
      (node (ref "R12") (pin "P$2") (pinfunction "2_P$2") (pintype "passive"))
      (node (ref "U1") (pin "15") (pinfunction "CRS_DV/PHYAD[1:0]_15") (pintype "bidirectional"))
    )
    (net (code "19") (name "C_A_DIR") (class "Default")
      (node (ref "R135") (pin "P$1") (pinfunction "1_P$1") (pintype "passive"))
      (node (ref "U3") (pin "58") (pinfunction "P9_0_58") (pintype "bidirectional"))
    )
    (net (code "20") (name "C_A_ENABLE") (class "Default")
      (node (ref "R136") (pin "P$1") (pinfunction "1_P$1") (pintype "passive"))
      (node (ref "U3") (pin "57") (pinfunction "P3_15_57") (pintype "bidirectional"))
    )
    (net (code "21") (name "C_A_HLFB_OUT") (class "Default")
      (node (ref "J29") (pin "5") (pinfunction "5-HLFB-_5") (pintype "passive"))
    )
    (net (code "22") (name "C_A_MI_DIR") (class "Default")
      (node (ref "J29") (pin "7") (pinfunction "7-INPUT_A-_7") (pintype "passive"))
      (node (ref "R137") (pin "1") (pinfunction "1_1") (pintype "passive"))
      (node (ref "U59") (pin "3") (pinfunction "C(3)_3") (pintype "input"))
    )
    (net (code "23") (name "C_A_MI_ENABLE") (class "Default")
      (node (ref "J29") (pin "8") (pinfunction "8-ENABLE-_8") (pintype "passive"))
      (node (ref "R138") (pin "1") (pinfunction "1_1") (pintype "passive"))
      (node (ref "U60") (pin "3") (pinfunction "C(3)_3") (pintype "input"))
    )
    (net (code "24") (name "C_A_MI_STEP") (class "Default")
      (node (ref "J29") (pin "6") (pinfunction "6-INPUT_B-_6") (pintype "passive"))
      (node (ref "R133") (pin "1") (pinfunction "1_1") (pintype "passive"))
      (node (ref "U58") (pin "3") (pinfunction "C(3)_3") (pintype "input"))
    )
    (net (code "25") (name "C_A_STEP") (class "Default")
      (node (ref "R134") (pin "P$1") (pinfunction "1_P$1") (pintype "passive"))
      (node (ref "U3") (pin "59") (pinfunction "P9_1_59") (pintype "bidirectional"))
    )
    (net (code "26") (name "C_B_DIR") (class "Default")
      (node (ref "R141") (pin "P$1") (pinfunction "1_P$1") (pintype "passive"))
      (node (ref "U3") (pin "70") (pinfunction "P9_8_70") (pintype "bidirectional"))
    )
    (net (code "27") (name "C_B_ENABLE") (class "Default")
      (node (ref "R142") (pin "P$1") (pinfunction "1_P$1") (pintype "passive"))
      (node (ref "U3") (pin "68") (pinfunction "P2_1/MD_68") (pintype "bidirectional"))
    )
    (net (code "28") (name "C_B_HLFB_OUT") (class "Default")
      (node (ref "J30") (pin "5") (pinfunction "5-HLFB-_5") (pintype "passive"))
    )
    (net (code "29") (name "C_B_MI_DIR") (class "Default")
      (node (ref "J30") (pin "7") (pinfunction "7-INPUT_A-_7") (pintype "passive"))
      (node (ref "R143") (pin "1") (pinfunction "1_1") (pintype "passive"))
      (node (ref "U62") (pin "3") (pinfunction "C(3)_3") (pintype "input"))
    )
    (net (code "30") (name "C_B_MI_ENABLE") (class "Default")
      (node (ref "J30") (pin "8") (pinfunction "8-ENABLE-_8") (pintype "passive"))
      (node (ref "R144") (pin "1") (pinfunction "1_1") (pintype "passive"))
      (node (ref "U63") (pin "3") (pinfunction "C(3)_3") (pintype "input"))
    )
    (net (code "31") (name "C_B_MI_STEP") (class "Default")
      (node (ref "J30") (pin "6") (pinfunction "6-INPUT_B-_6") (pintype "passive"))
      (node (ref "R139") (pin "1") (pinfunction "1_1") (pintype "passive"))
      (node (ref "U61") (pin "3") (pinfunction "C(3)_3") (pintype "input"))
    )
    (net (code "32") (name "C_B_STEP") (class "Default")
      (node (ref "R140") (pin "P$1") (pinfunction "1_P$1") (pintype "passive"))
      (node (ref "U3") (pin "71") (pinfunction "P9_7_71") (pintype "bidirectional"))
    )
    (net (code "33") (name "ESTOP") (class "Default")
      (node (ref "R79") (pin "P$2") (pinfunction "2_P$2") (pintype "passive"))
      (node (ref "R80") (pin "P$2") (pinfunction "2_P$2") (pintype "passive"))
      (node (ref "U21") (pin "2") (pinfunction "E(1)_2") (pintype "output"))
      (node (ref "U3") (pin "69") (pinfunction "P2_0(INPUT_ONLY)_69") (pintype "bidirectional"))
    )
    (net (code "34") (name "ESTOP_RET") (class "Default")
      (node (ref "J20") (pin "1") (pinfunction "1_1") (pintype "passive"))
      (node (ref "R78") (pin "P$1") (pinfunction "1_P$1") (pintype "passive"))
    )
    (net (code "35") (name "ETH") (class "Default")
      (node (ref "U1") (pin "16") (pinfunction "REF_CLK_16") (pintype "bidirectional"))
      (node (ref "U3") (pin "9") (pinfunction "P7_1_9") (pintype "bidirectional"))
    )
    (net (code "36") (name "ETH_CRS_DV") (class "Default")
      (node (ref "R12") (pin "P$1") (pinfunction "1_P$1") (pintype "passive"))
      (node (ref "U3") (pin "13") (pinfunction "P7_5_13") (pintype "bidirectional"))
    )
    (net (code "37") (name "ETH_IRQ14") (class "Default")
      (node (ref "R2") (pin "P$1") (pinfunction "1_P$1") (pintype "passive"))
      (node (ref "U1") (pin "18") (pinfunction "INTRP_18") (pintype "bidirectional"))
      (node (ref "U3") (pin "159") (pinfunction "P0_10/AN103_159") (pintype "bidirectional"))
    )
    (net (code "38") (name "ETH_MDC") (class "Default")
      (node (ref "R4") (pin "P$1") (pinfunction "1_P$1") (pintype "passive"))
      (node (ref "U1") (pin "11") (pinfunction "MDC_11") (pintype "input"))
      (node (ref "U3") (pin "4") (pinfunction "P4_3_4") (pintype "bidirectional"))
    )
    (net (code "39") (name "ETH_MDIO") (class "Default")
      (node (ref "R6") (pin "P$1") (pinfunction "1_P$1") (pintype "passive"))
      (node (ref "U1") (pin "10") (pinfunction "MDIO_10") (pintype "bidirectional"))
      (node (ref "U3") (pin "5") (pinfunction "P4_4_5") (pintype "bidirectional"))
    )
    (net (code "40") (name "ETH_RESET") (class "Default")
      (node (ref "C6") (pin "P$1") (pinfunction "1_P$1") (pintype "passive"))
      (node (ref "R3") (pin "P$1") (pinfunction "1_P$1") (pintype "passive"))
      (node (ref "U1") (pin "24") (pinfunction "~{RST}_24") (pintype "input"))
      (node (ref "U3") (pin "172") (pinfunction "P8_6_172") (pintype "bidirectional"))
    )
    (net (code "41") (name "ETH_RXD0") (class "Default")
      (node (ref "R10") (pin "P$1") (pinfunction "1_P$1") (pintype "passive"))
      (node (ref "U3") (pin "10") (pinfunction "P7_2_10") (pintype "bidirectional"))
    )
    (net (code "42") (name "ETH_RXD1") (class "Default")
      (node (ref "R9") (pin "P$1") (pinfunction "1_P$1") (pintype "passive"))
      (node (ref "U3") (pin "11") (pinfunction "P7_3_11") (pintype "bidirectional"))
    )
    (net (code "43") (name "ETH_RX_ER") (class "Default")
      (node (ref "R11") (pin "P$1") (pinfunction "1_P$1") (pintype "passive"))
      (node (ref "U3") (pin "12") (pinfunction "P7_4_12") (pintype "bidirectional"))
    )
    (net (code "44") (name "ETH_TXD0") (class "Default")
      (node (ref "U1") (pin "20") (pinfunction "TXD0_20") (pintype "input"))
      (node (ref "U3") (pin "8") (pinfunction "P7_0_8") (pintype "bidirectional"))
    )
    (net (code "45") (name "ETH_TXD1") (class "Default")
      (node (ref "U1") (pin "21") (pinfunction "TXD1_21") (pintype "bidirectional"))
      (node (ref "U3") (pin "7") (pinfunction "P4_6_7") (pintype "bidirectional"))
    )
    (net (code "46") (name "ETH_TXD_EN") (class "Default")
      (node (ref "U1") (pin "19") (pinfunction "TXEN_19") (pintype "input"))
      (node (ref "U3") (pin "6") (pinfunction "P4_5_6") (pintype "bidirectional"))
    )
    (net (code "47") (name "GND") (class "Default")
      (node (ref "C1") (pin "P$2") (pinfunction "2_P$2") (pintype "passive"))
      (node (ref "C10") (pin "P$2") (pinfunction "2_P$2") (pintype "passive"))
      (node (ref "C11") (pin "P$2") (pinfunction "2_P$2") (pintype "passive"))
      (node (ref "C12") (pin "P$2") (pinfunction "2_P$2") (pintype "passive"))
      (node (ref "C13") (pin "P$2") (pinfunction "2_P$2") (pintype "passive"))
      (node (ref "C14") (pin "P$2") (pinfunction "2_P$2") (pintype "passive"))
      (node (ref "C15") (pin "P$2") (pinfunction "2_P$2") (pintype "passive"))
      (node (ref "C16") (pin "P$2") (pinfunction "2_P$2") (pintype "passive"))
      (node (ref "C17") (pin "P$2") (pinfunction "2_P$2") (pintype "passive"))
      (node (ref "C18") (pin "P$2") (pinfunction "2_P$2") (pintype "passive"))
      (node (ref "C19") (pin "P$1") (pinfunction "1_P$1") (pintype "passive"))
      (node (ref "C2") (pin "P$2") (pinfunction "2_P$2") (pintype "passive"))
      (node (ref "C20") (pin "P$1") (pinfunction "1_P$1") (pintype "passive"))
      (node (ref "C21") (pin "P$1") (pinfunction "1_P$1") (pintype "passive"))
      (node (ref "C22") (pin "P$1") (pinfunction "1_P$1") (pintype "passive"))
      (node (ref "C23") (pin "P$2") (pinfunction "2_P$2") (pintype "passive"))
      (node (ref "C24") (pin "P$1") (pinfunction "1_P$1") (pintype "passive"))
      (node (ref "C25") (pin "P$1") (pinfunction "1_P$1") (pintype "passive"))
      (node (ref "C26") (pin "P$2") (pinfunction "2_P$2") (pintype "passive"))
      (node (ref "C27") (pin "P$1") (pinfunction "1_P$1") (pintype "passive"))
      (node (ref "C28") (pin "P$2") (pinfunction "2_P$2") (pintype "passive"))
      (node (ref "C29") (pin "P$2") (pinfunction "2_P$2") (pintype "passive"))
      (node (ref "C3") (pin "P$2") (pinfunction "2_P$2") (pintype "passive"))
      (node (ref "C30") (pin "P$1") (pinfunction "1_P$1") (pintype "passive"))
      (node (ref "C31") (pin "2") (pinfunction "2_2") (pintype "passive"))
      (node (ref "C32") (pin "P$2") (pinfunction "2_P$2") (pintype "passive"))
      (node (ref "C33") (pin "P$2") (pinfunction "2_P$2") (pintype "passive"))
      (node (ref "C34") (pin "P$1") (pinfunction "1_P$1") (pintype "passive"))
      (node (ref "C35") (pin "P$1") (pinfunction "1_P$1") (pintype "passive"))
      (node (ref "C36") (pin "P$2") (pinfunction "2_P$2") (pintype "passive"))
      (node (ref "C37") (pin "P$2") (pinfunction "2_P$2") (pintype "passive"))
      (node (ref "C38") (pin "P$1") (pinfunction "1_P$1") (pintype "passive"))
      (node (ref "C39") (pin "P$2") (pinfunction "2_P$2") (pintype "passive"))
      (node (ref "C4") (pin "P$2") (pinfunction "2_P$2") (pintype "passive"))
      (node (ref "C40") (pin "P$2") (pinfunction "2_P$2") (pintype "passive"))
      (node (ref "C41") (pin "P$2") (pinfunction "2_P$2") (pintype "passive"))
      (node (ref "C42") (pin "P$2") (pinfunction "2_P$2") (pintype "passive"))
      (node (ref "C43") (pin "P$1") (pinfunction "1_P$1") (pintype "passive"))
      (node (ref "C5") (pin "P$2") (pinfunction "2_P$2") (pintype "passive"))
      (node (ref "C6") (pin "P$2") (pinfunction "2_P$2") (pintype "passive"))
      (node (ref "C7") (pin "P$2") (pinfunction "2_P$2") (pintype "passive"))
      (node (ref "C8") (pin "P$2") (pinfunction "2_P$2") (pintype "passive"))
      (node (ref "C9") (pin "P$2") (pinfunction "2_P$2") (pintype "passive"))
      (node (ref "J1") (pin "6") (pinfunction "SUPPLY_VOLTAGE_GROUND_6") (pintype "power_in"))
      (node (ref "J10") (pin "2") (pinfunction "2_2") (pintype "passive"))
      (node (ref "J11") (pin "2") (pinfunction "2_2") (pintype "passive"))
      (node (ref "J12") (pin "2") (pinfunction "2_2") (pintype "passive"))
      (node (ref "J19") (pin "2") (pinfunction "2_2") (pintype "passive"))
      (node (ref "J2") (pin "P$1") (pinfunction "P$1_P$1") (pintype "bidirectional"))
      (node (ref "J20") (pin "2") (pinfunction "2_2") (pintype "passive"))
      (node (ref "J27") (pin "2") (pinfunction "2_2") (pintype "passive"))
      (node (ref "J28") (pin "2") (pinfunction "2_2") (pintype "passive"))
      (node (ref "J3") (pin "10") (pinfunction "10_10") (pintype "passive"))
      (node (ref "J3") (pin "6") (pinfunction "6_6") (pintype "passive"))
      (node (ref "J3") (pin "8") (pinfunction "8_8") (pintype "passive"))
      (node (ref "J31") (pin "2") (pinfunction "2_2") (pintype "passive"))
      (node (ref "J32") (pin "2") (pinfunction "2_2") (pintype "passive"))
      (node (ref "J5") (pin "2") (pinfunction "2_2") (pintype "passive"))
      (node (ref "J6") (pin "GND") (pinfunction "GND_GND") (pintype "power_in"))
      (node (ref "J7") (pin "P$5") (pinfunction "GND_P$5") (pintype "bidirectional"))
      (node (ref "J8") (pin "P$14") (pinfunction "P$14_P$14") (pintype "bidirectional"))
      (node (ref "J8") (pin "P$16") (pinfunction "P$16_P$16") (pintype "bidirectional"))
      (node (ref "J8") (pin "P$18") (pinfunction "P$18_P$18") (pintype "bidirectional"))
      (node (ref "J8") (pin "P$20") (pinfunction "P$20_P$20") (pintype "bidirectional"))
      (node (ref "LED1") (pin "2") (pinfunction "C_2") (pintype "passive"))
      (node (ref "LED10") (pin "2") (pinfunction "C_2") (pintype "passive"))
      (node (ref "LED11") (pin "2") (pinfunction "C_2") (pintype "passive"))
      (node (ref "LED12") (pin "2") (pinfunction "C_2") (pintype "passive"))
      (node (ref "LED13") (pin "2") (pinfunction "C_2") (pintype "passive"))
      (node (ref "LED14") (pin "2") (pinfunction "C_2") (pintype "passive"))
      (node (ref "LED15") (pin "2") (pinfunction "C_2") (pintype "passive"))
      (node (ref "LED16") (pin "2") (pinfunction "C_2") (pintype "passive"))
      (node (ref "LED3") (pin "2") (pinfunction "C_2") (pintype "passive"))
      (node (ref "LED6") (pin "2") (pinfunction "C_2") (pintype "passive"))
      (node (ref "LED7") (pin "2") (pinfunction "C_2") (pintype "passive"))
      (node (ref "R1") (pin "P$1") (pinfunction "1_P$1") (pintype "passive"))
      (node (ref "R101") (pin "P$1") (pinfunction "1_P$1") (pintype "passive"))
      (node (ref "R21") (pin "P$1") (pinfunction "1_P$1") (pintype "passive"))
      (node (ref "R22") (pin "P$1") (pinfunction "1_P$1") (pintype "passive"))
      (node (ref "R23") (pin "P$1") (pinfunction "1_P$1") (pintype "passive"))
      (node (ref "R24") (pin "P$1") (pinfunction "1_P$1") (pintype "passive"))
      (node (ref "R34") (pin "P$1") (pinfunction "1_P$1") (pintype "passive"))
      (node (ref "R53") (pin "P$1") (pinfunction "1_P$1") (pintype "passive"))
      (node (ref "R56") (pin "P$1") (pinfunction "1_P$1") (pintype "passive"))
      (node (ref "R59") (pin "P$1") (pinfunction "1_P$1") (pintype "passive"))
      (node (ref "R74") (pin "P$1") (pinfunction "1_P$1") (pintype "passive"))
      (node (ref "R77") (pin "P$1") (pinfunction "1_P$1") (pintype "passive"))
      (node (ref "R80") (pin "P$1") (pinfunction "1_P$1") (pintype "passive"))
      (node (ref "R83") (pin "P$1") (pinfunction "1_P$1") (pintype "passive"))
      (node (ref "R98") (pin "P$1") (pinfunction "1_P$1") (pintype "passive"))
      (node (ref "RJ1") (pin "10") (pinfunction "GLO_10") (pintype "bidirectional"))
      (node (ref "RJ1") (pin "8") (pinfunction "P8_8") (pintype "bidirectional"))
      (node (ref "TH01") (pin "1") (pinfunction "1_1") (pintype "passive"))
      (node (ref "TH02") (pin "1") (pinfunction "1_1") (pintype "passive"))
      (node (ref "TH03") (pin "1") (pinfunction "1_1") (pintype "passive"))
      (node (ref "TH04") (pin "1") (pinfunction "1_1") (pintype "passive"))
      (node (ref "TH05") (pin "1") (pinfunction "1_1") (pintype "passive"))
      (node (ref "TH06") (pin "1") (pinfunction "1_1") (pintype "passive"))
      (node (ref "TH07") (pin "1") (pinfunction "1_1") (pintype "passive"))
      (node (ref "TH08") (pin "1") (pinfunction "1_1") (pintype "passive"))
      (node (ref "U1") (pin "22") (pinfunction "GND_22") (pintype "power_in"))
      (node (ref "U1") (pin "25") (pinfunction "25_25") (pintype "passive"))
      (node (ref "U10") (pin "2") (pinfunction "E(1)_2") (pintype "output"))
      (node (ref "U11") (pin "2") (pinfunction "E(1)_2") (pintype "output"))
      (node (ref "U12") (pin "2") (pinfunction "E(1)_2") (pintype "output"))
      (node (ref "U13") (pin "2") (pinfunction "E(1)_2") (pintype "output"))
      (node (ref "U14") (pin "2") (pinfunction "E(1)_2") (pintype "output"))
      (node (ref "U15") (pin "2") (pinfunction "E(1)_2") (pintype "output"))
      (node (ref "U16") (pin "2") (pinfunction "E(1)_2") (pintype "output"))
      (node (ref "U17") (pin "2") (pinfunction "E(1)_2") (pintype "output"))
      (node (ref "U2") (pin "2") (pinfunction "GND_2") (pintype "input"))
      (node (ref "U22") (pin "2") (pinfunction "E(1)_2") (pintype "output"))
      (node (ref "U23") (pin "2") (pinfunction "E(1)_2") (pintype "output"))
      (node (ref "U24") (pin "2") (pinfunction "E(1)_2") (pintype "output"))
      (node (ref "U25") (pin "2") (pinfunction "E(1)_2") (pintype "output"))
      (node (ref "U26") (pin "2") (pinfunction "E(1)_2") (pintype "output"))
      (node (ref "U27") (pin "2") (pinfunction "E(1)_2") (pintype "output"))
      (node (ref "U3") (pin "111") (pinfunction "VSS(IO)5_111") (pintype "bidirectional"))
      (node (ref "U3") (pin "124") (pinfunction "VSS(IO)6_124") (pintype "bidirectional"))
      (node (ref "U3") (pin "139") (pinfunction "VSS(IO)7_139") (pintype "bidirectional"))
      (node (ref "U3") (pin "150") (pinfunction "VSS(IO)8_150") (pintype "bidirectional"))
      (node (ref "U3") (pin "153") (pinfunction "VREFL_153") (pintype "bidirectional"))
      (node (ref "U3") (pin "156") (pinfunction "AVSS0_156") (pintype "bidirectional"))
      (node (ref "U3") (pin "157") (pinfunction "VREFL0_157") (pintype "bidirectional"))
      (node (ref "U3") (pin "170") (pinfunction "VSS(IO)9_170") (pintype "bidirectional"))
      (node (ref "U3") (pin "22") (pinfunction "VSS1_22") (pintype "bidirectional"))
      (node (ref "U3") (pin "28") (pinfunction "AVSS_USBHS_28") (pintype "bidirectional"))
      (node (ref "U3") (pin "29") (pinfunction "PVSS_USBHS_29") (pintype "bidirectional"))
      (node (ref "U3") (pin "30") (pinfunction "VSS2_USBHS_30") (pintype "bidirectional"))
      (node (ref "U3") (pin "33") (pinfunction "VSS1_USBHS_33") (pintype "bidirectional"))
      (node (ref "U3") (pin "35") (pinfunction "VSSIO_35") (pintype "bidirectional"))
      (node (ref "U3") (pin "45") (pinfunction "VSS_USB_45") (pintype "bidirectional"))
      (node (ref "U3") (pin "60") (pinfunction "VSS(IO)2_60") (pintype "bidirectional"))
      (node (ref "U3") (pin "63") (pinfunction "VSS(IO/DCDC)_63") (pintype "bidirectional"))
      (node (ref "U3") (pin "66") (pinfunction "VCC_DCDC(IO/DCDC)_66") (pintype "bidirectional"))
      (node (ref "U3") (pin "83") (pinfunction "VSS(IO)3_83") (pintype "bidirectional"))
      (node (ref "U3") (pin "98") (pinfunction "VSS(IO)4_98") (pintype "bidirectional"))
      (node (ref "U34") (pin "2") (pinfunction "E(1)_2") (pintype "output"))
      (node (ref "U35") (pin "2") (pinfunction "E(1)_2") (pintype "output"))
      (node (ref "U36") (pin "2") (pinfunction "E(1)_2") (pintype "output"))
      (node (ref "U37") (pin "2") (pinfunction "E(1)_2") (pintype "output"))
      (node (ref "U38") (pin "2") (pinfunction "E(1)_2") (pintype "output"))
      (node (ref "U39") (pin "2") (pinfunction "E(1)_2") (pintype "output"))
      (node (ref "U46") (pin "2") (pinfunction "E(1)_2") (pintype "output"))
      (node (ref "U47") (pin "2") (pinfunction "E(1)_2") (pintype "output"))
      (node (ref "U48") (pin "2") (pinfunction "E(1)_2") (pintype "output"))
      (node (ref "U49") (pin "2") (pinfunction "E(1)_2") (pintype "output"))
      (node (ref "U50") (pin "2") (pinfunction "E(1)_2") (pintype "output"))
      (node (ref "U51") (pin "2") (pinfunction "E(1)_2") (pintype "output"))
      (node (ref "U58") (pin "2") (pinfunction "E(1)_2") (pintype "output"))
      (node (ref "U59") (pin "2") (pinfunction "E(1)_2") (pintype "output"))
      (node (ref "U6") (pin "2") (pinfunction "E(1)_2") (pintype "output"))
      (node (ref "U60") (pin "2") (pinfunction "E(1)_2") (pintype "output"))
      (node (ref "U61") (pin "2") (pinfunction "E(1)_2") (pintype "output"))
      (node (ref "U62") (pin "2") (pinfunction "E(1)_2") (pintype "output"))
      (node (ref "U63") (pin "2") (pinfunction "E(1)_2") (pintype "output"))
      (node (ref "U7") (pin "2") (pinfunction "E(1)_2") (pintype "output"))
      (node (ref "U70") (pin "2") (pinfunction "E(1)_2") (pintype "output"))
      (node (ref "U71") (pin "2") (pinfunction "E(1)_2") (pintype "output"))
      (node (ref "U72") (pin "2") (pinfunction "E(1)_2") (pintype "output"))
      (node (ref "U73") (pin "2") (pinfunction "E(1)_2") (pintype "output"))
      (node (ref "U74") (pin "2") (pinfunction "E(1)_2") (pintype "output"))
      (node (ref "U75") (pin "2") (pinfunction "E(1)_2") (pintype "output"))
      (node (ref "X1") (pin "2") (pinfunction "2_2") (pintype "bidirectional"))
      (node (ref "X1") (pin "4") (pinfunction "4_4") (pintype "bidirectional"))
      (node (ref "X2") (pin "2") (pinfunction "2_2") (pintype "bidirectional"))
      (node (ref "X2") (pin "4") (pinfunction "4_4") (pintype "bidirectional"))
    )
    (net (code "48") (name "GNDE") (class "Default")
      (node (ref "J1") (pin "S1") (pinfunction "SHIELD_S1") (pintype "passive"))
      (node (ref "J1") (pin "S2") (pinfunction "SHIELD_S2") (pintype "passive"))
      (node (ref "J1") (pin "S3") (pinfunction "SHIELD_S3") (pintype "passive"))
      (node (ref "J1") (pin "S4") (pinfunction "SHIELD_S4") (pintype "passive"))
      (node (ref "J2") (pin "P$4") (pinfunction "P$4_P$4") (pintype "bidirectional"))
      (node (ref "J6") (pin "SHLD1") (pinfunction "SHIELD_1_SHLD1") (pintype "bidirectional"))
      (node (ref "J6") (pin "SHLD2") (pinfunction "SHIELD_2_SHLD2") (pintype "bidirectional"))
      (node (ref "J7") (pin "P$6") (pinfunction "SHIELD1_P$6") (pintype "bidirectional"))
      (node (ref "J7") (pin "P$7") (pinfunction "SHIELD2_P$7") (pintype "bidirectional"))
      (node (ref "J7") (pin "P$8") (pinfunction "SHIELD3_P$8") (pintype "bidirectional"))
      (node (ref "J7") (pin "P$9") (pinfunction "SHIELD4_P$9") (pintype "bidirectional"))
      (node (ref "RJ1") (pin "13") (pinfunction "GNDE0_13") (pintype "bidirectional"))
      (node (ref "RJ1") (pin "14") (pinfunction "GNDE1_14") (pintype "bidirectional"))
    )
    (net (code "49") (name "ID") (class "Default")
      (node (ref "J7") (pin "P$4") (pinfunction "ID_P$4") (pintype "bidirectional"))
    )
    (net (code "50") (name "IIC_1_SCL") (class "Default")
      (node (ref "J8") (pin "P$8") (pinfunction "P$8_P$8") (pintype "bidirectional"))
      (node (ref "R14") (pin "P$2") (pinfunction "2_P$2") (pintype "passive"))
      (node (ref "U3") (pin "132") (pinfunction "P1_0_132") (pintype "bidirectional"))
    )
    (net (code "51") (name "IIC_1_SDA") (class "Default")
      (node (ref "J8") (pin "P$7") (pinfunction "P$7_P$7") (pintype "bidirectional"))
      (node (ref "R15") (pin "P$2") (pinfunction "2_P$2") (pintype "passive"))
      (node (ref "U3") (pin "131") (pinfunction "P1_1_131") (pintype "bidirectional"))
    )
    (net (code "52") (name "LED1{slash}SPEED") (class "Default")
      (node (ref "RJ1") (pin "11") (pinfunction "YLO_11") (pintype "bidirectional"))
      (node (ref "U1") (pin "23") (pinfunction "LED0/ANEN_SPEED_23") (pintype "bidirectional"))
    )
    (net (code "53") (name "LS_01") (class "Default")
      (node (ref "R33") (pin "P$2") (pinfunction "2_P$2") (pintype "passive"))
      (node (ref "R34") (pin "P$2") (pinfunction "2_P$2") (pintype "passive"))
      (node (ref "U3") (pin "50") (pinfunction "P2_6_50") (pintype "bidirectional"))
      (node (ref "U5") (pin "2") (pinfunction "E(1)_2") (pintype "output"))
    )
    (net (code "54") (name "LS_01_RET") (class "Default")
      (node (ref "J32") (pin "1") (pinfunction "1_1") (pintype "passive"))
      (node (ref "R28") (pin "P$1") (pinfunction "1_P$1") (pintype "passive"))
    )
    (net (code "55") (name "LS_02") (class "Default")
      (node (ref "R36") (pin "P$2") (pinfunction "2_P$2") (pintype "passive"))
      (node (ref "R53") (pin "P$2") (pinfunction "2_P$2") (pintype "passive"))
      (node (ref "U3") (pin "51") (pinfunction "P2_5_51") (pintype "bidirectional"))
      (node (ref "U8") (pin "2") (pinfunction "E(1)_2") (pintype "output"))
    )
    (net (code "56") (name "LS_02_RET") (class "Default")
      (node (ref "J31") (pin "1") (pinfunction "1_1") (pintype "passive"))
      (node (ref "R35") (pin "P$1") (pinfunction "1_P$1") (pintype "passive"))
    )
    (net (code "57") (name "LS_03") (class "Default")
      (node (ref "R55") (pin "P$2") (pinfunction "2_P$2") (pintype "passive"))
      (node (ref "R56") (pin "P$2") (pinfunction "2_P$2") (pintype "passive"))
      (node (ref "U3") (pin "53") (pinfunction "P2_3_53") (pintype "bidirectional"))
      (node (ref "U9") (pin "2") (pinfunction "E(1)_2") (pintype "output"))
    )
    (net (code "58") (name "LS_03_RET") (class "Default")
      (node (ref "J28") (pin "1") (pinfunction "1_1") (pintype "passive"))
      (node (ref "R54") (pin "P$1") (pinfunction "1_P$1") (pintype "passive"))
    )
    (net (code "59") (name "LS_04") (class "Default")
      (node (ref "R73") (pin "P$2") (pinfunction "2_P$2") (pintype "passive"))
      (node (ref "R74") (pin "P$2") (pinfunction "2_P$2") (pintype "passive"))
      (node (ref "U19") (pin "2") (pinfunction "E(1)_2") (pintype "output"))
      (node (ref "U3") (pin "54") (pinfunction "P2_2_54") (pintype "bidirectional"))
    )
    (net (code "60") (name "LS_04_RET") (class "Default")
      (node (ref "J27") (pin "1") (pinfunction "1_1") (pintype "passive"))
      (node (ref "R60") (pin "P$1") (pinfunction "1_P$1") (pintype "passive"))
    )
    (net (code "61") (name "LS_05") (class "Default")
      (node (ref "R58") (pin "P$2") (pinfunction "2_P$2") (pintype "passive"))
      (node (ref "R59") (pin "P$2") (pinfunction "2_P$2") (pintype "passive"))
      (node (ref "U18") (pin "2") (pinfunction "E(1)_2") (pintype "output"))
      (node (ref "U3") (pin "81") (pinfunction "P3_5_81") (pintype "bidirectional"))
    )
    (net (code "62") (name "LS_05_RET") (class "Default")
      (node (ref "J19") (pin "1") (pinfunction "1_1") (pintype "passive"))
      (node (ref "R57") (pin "P$1") (pinfunction "1_P$1") (pintype "passive"))
    )
    (net (code "63") (name "LS_06") (class "Default")
      (node (ref "R76") (pin "P$2") (pinfunction "2_P$2") (pintype "passive"))
      (node (ref "R77") (pin "P$2") (pinfunction "2_P$2") (pintype "passive"))
      (node (ref "U20") (pin "2") (pinfunction "E(1)_2") (pintype "output"))
      (node (ref "U3") (pin "82") (pinfunction "P3_4_82") (pintype "bidirectional"))
    )
    (net (code "64") (name "LS_06_RET") (class "Default")
      (node (ref "J12") (pin "1") (pinfunction "1_1") (pintype "passive"))
      (node (ref "R75") (pin "P$1") (pinfunction "1_P$1") (pintype "passive"))
    )
    (net (code "65") (name "LS_07") (class "Default")
      (node (ref "R97") (pin "P$2") (pinfunction "2_P$2") (pintype "passive"))
      (node (ref "R98") (pin "P$2") (pinfunction "2_P$2") (pintype "passive"))
      (node (ref "U29") (pin "2") (pinfunction "E(1)_2") (pintype "output"))
      (node (ref "U3") (pin "86") (pinfunction "P3_2_86") (pintype "bidirectional"))
    )
    (net (code "66") (name "LS_07_RET") (class "Default")
      (node (ref "J11") (pin "1") (pinfunction "1_1") (pintype "passive"))
      (node (ref "R84") (pin "P$1") (pinfunction "1_P$1") (pintype "passive"))
    )
    (net (code "67") (name "LS_08") (class "Default")
      (node (ref "R82") (pin "P$2") (pinfunction "2_P$2") (pintype "passive"))
      (node (ref "R83") (pin "P$2") (pinfunction "2_P$2") (pintype "passive"))
      (node (ref "U28") (pin "2") (pinfunction "E(1)_2") (pintype "output"))
      (node (ref "U3") (pin "87") (pinfunction "P3_1_87") (pintype "bidirectional"))
    )
    (net (code "68") (name "LS_08_RET") (class "Default")
      (node (ref "J5") (pin "1") (pinfunction "1_1") (pintype "passive"))
      (node (ref "R81") (pin "P$1") (pinfunction "1_P$1") (pintype "passive"))
    )
    (net (code "69") (name "LS_09") (class "Default")
      (node (ref "R100") (pin "P$2") (pinfunction "2_P$2") (pintype "passive"))
      (node (ref "R101") (pin "P$2") (pinfunction "2_P$2") (pintype "passive"))
      (node (ref "U3") (pin "92") (pinfunction "P1_11_92") (pintype "bidirectional"))
      (node (ref "U30") (pin "2") (pinfunction "E(1)_2") (pintype "output"))
    )
    (net (code "70") (name "LS_09_RET") (class "Default")
      (node (ref "J10") (pin "1") (pinfunction "1_1") (pintype "passive"))
      (node (ref "R99") (pin "P$1") (pinfunction "1_P$1") (pintype "passive"))
    )
    (net (code "71") (name "NC") (class "Default")
      (node (ref "RJ1") (pin "7") (pinfunction "P7_7") (pintype "bidirectional"))
      (node (ref "U3") (pin "79") (pinfunction "P3_7_79") (pintype "bidirectional"))
      (node (ref "U3") (pin "80") (pinfunction "P3_6_80") (pintype "bidirectional"))
      (node (ref "U3") (pin "85") (pinfunction "P3_3_85") (pintype "bidirectional"))
    )
    (net (code "72") (name "Net-(C8-1)") (class "Default")
      (node (ref "C8") (pin "P$1") (pinfunction "1_P$1") (pintype "passive"))
      (node (ref "C9") (pin "P$1") (pinfunction "1_P$1") (pintype "passive"))
      (node (ref "FB1") (pin "2") (pinfunction "P$2_2") (pintype "bidirectional"))
      (node (ref "U1") (pin "2") (pinfunction "VDDA_3.3_2") (pintype "power_in"))
    )
    (net (code "73") (name "Net-(C24-2)") (class "Default")
      (node (ref "C24") (pin "P$2") (pinfunction "2_P$2") (pintype "passive"))
      (node (ref "U3") (pin "148") (pinfunction "VCL2_148") (pintype "bidirectional"))
    )
    (net (code "74") (name "Net-(C28-1)") (class "Default")
      (node (ref "C28") (pin "P$1") (pinfunction "1_P$1") (pintype "passive"))
      (node (ref "J7") (pin "P$1") (pinfunction "VBUS_P$1") (pintype "bidirectional"))
      (node (ref "R16") (pin "P$2") (pinfunction "2_P$2") (pintype "passive"))
      (node (ref "R21") (pin "P$2") (pinfunction "2_P$2") (pintype "passive"))
    )
    (net (code "75") (name "Net-(C33-1)") (class "Default")
      (node (ref "C33") (pin "P$1") (pinfunction "1_P$1") (pintype "passive"))
      (node (ref "U3") (pin "19") (pinfunction "VCLO_19") (pintype "bidirectional"))
    )
    (net (code "76") (name "Net-(C42-1)") (class "Default")
      (node (ref "C42") (pin "P$1") (pinfunction "1_P$1") (pintype "passive"))
      (node (ref "U3") (pin "62") (pinfunction "VCL1_62") (pintype "bidirectional"))
    )
    (net (code "77") (name "Net-(J7-D+)") (class "Default")
      (node (ref "J7") (pin "P$3") (pinfunction "D+_P$3") (pintype "bidirectional"))
      (node (ref "R18") (pin "P$2") (pinfunction "2_P$2") (pintype "passive"))
    )
    (net (code "78") (name "Net-(J7-D-)") (class "Default")
      (node (ref "J7") (pin "P$2") (pinfunction "D-_P$2") (pintype "bidirectional"))
      (node (ref "R17") (pin "P$2") (pinfunction "2_P$2") (pintype "passive"))
    )
    (net (code "79") (name "Net-(LED1-A)") (class "Default")
      (node (ref "LED1") (pin "1") (pinfunction "A_1") (pintype "passive"))
      (node (ref "R5") (pin "P$1") (pinfunction "1_P$1") (pintype "passive"))
    )
    (net (code "80") (name "Net-(LED3-A)") (class "Default")
      (node (ref "LED3") (pin "1") (pinfunction "A_1") (pintype "passive"))
      (node (ref "R33") (pin "P$1") (pinfunction "1_P$1") (pintype "passive"))
    )
    (net (code "81") (name "Net-(LED4-A)") (class "Default")
      (node (ref "LED4") (pin "1") (pinfunction "A_1") (pintype "passive"))
      (node (ref "R32") (pin "P$1") (pinfunction "1_P$1") (pintype "passive"))
    )
    (net (code "82") (name "Net-(LED4-C)") (class "Default")
      (node (ref "LED4") (pin "2") (pinfunction "C_2") (pintype "passive"))
      (node (ref "U$1") (pin "P$1") (pinfunction "VC-_P$1") (pintype "bidirectional"))
      (node (ref "U6") (pin "3") (pinfunction "C(3)_3") (pintype "input"))
    )
    (net (code "83") (name "Net-(LED5-A)") (class "Default")
      (node (ref "LED5") (pin "1") (pinfunction "A_1") (pintype "passive"))
      (node (ref "R31") (pin "P$1") (pinfunction "1_P$1") (pintype "passive"))
    )
    (net (code "84") (name "Net-(LED5-C)") (class "Default")
      (node (ref "LED5") (pin "2") (pinfunction "C_2") (pintype "passive"))
      (node (ref "U$2") (pin "P$1") (pinfunction "VC-_P$1") (pintype "bidirectional"))
      (node (ref "U7") (pin "3") (pinfunction "C(3)_3") (pintype "input"))
    )
    (net (code "85") (name "Net-(LED6-A)") (class "Default")
      (node (ref "LED6") (pin "1") (pinfunction "A_1") (pintype "passive"))
      (node (ref "R36") (pin "P$1") (pinfunction "1_P$1") (pintype "passive"))
    )
    (net (code "86") (name "Net-(LED7-A)") (class "Default")
      (node (ref "LED7") (pin "1") (pinfunction "A_1") (pintype "passive"))
      (node (ref "R55") (pin "P$1") (pinfunction "1_P$1") (pintype "passive"))
    )
    (net (code "87") (name "Net-(LED8-A)") (class "Default")
      (node (ref "LED8") (pin "1") (pinfunction "A_1") (pintype "passive"))
      (node (ref "R52") (pin "P$1") (pinfunction "1_P$1") (pintype "passive"))
    )
    (net (code "88") (name "Net-(LED8-C)") (class "Default")
      (node (ref "LED8") (pin "2") (pinfunction "C_2") (pintype "passive"))
      (node (ref "U$7") (pin "P$1") (pinfunction "VC-_P$1") (pintype "bidirectional"))
      (node (ref "U16") (pin "3") (pinfunction "C(3)_3") (pintype "input"))
    )
    (net (code "89") (name "Net-(LED9-A)") (class "Default")
      (node (ref "LED9") (pin "1") (pinfunction "A_1") (pintype "passive"))
      (node (ref "R51") (pin "P$1") (pinfunction "1_P$1") (pintype "passive"))
    )
    (net (code "90") (name "Net-(LED9-C)") (class "Default")
      (node (ref "LED9") (pin "2") (pinfunction "C_2") (pintype "passive"))
      (node (ref "U$8") (pin "P$1") (pinfunction "VC-_P$1") (pintype "bidirectional"))
      (node (ref "U17") (pin "3") (pinfunction "C(3)_3") (pintype "input"))
    )
    (net (code "91") (name "Net-(LED10-A)") (class "Default")
      (node (ref "LED10") (pin "1") (pinfunction "A_1") (pintype "passive"))
      (node (ref "R58") (pin "P$1") (pinfunction "1_P$1") (pintype "passive"))
    )
    (net (code "92") (name "Net-(LED11-A)") (class "Default")
      (node (ref "LED11") (pin "1") (pinfunction "A_1") (pintype "passive"))
      (node (ref "R73") (pin "P$1") (pinfunction "1_P$1") (pintype "passive"))
    )
    (net (code "93") (name "Net-(LED12-A)") (class "Default")
      (node (ref "LED12") (pin "1") (pinfunction "A_1") (pintype "passive"))
      (node (ref "R76") (pin "P$1") (pinfunction "1_P$1") (pintype "passive"))
    )
    (net (code "94") (name "Net-(LED13-A)") (class "Default")
      (node (ref "LED13") (pin "1") (pinfunction "A_1") (pintype "passive"))
      (node (ref "R79") (pin "P$1") (pinfunction "1_P$1") (pintype "passive"))
    )
    (net (code "95") (name "Net-(LED14-A)") (class "Default")
      (node (ref "LED14") (pin "1") (pinfunction "A_1") (pintype "passive"))
      (node (ref "R82") (pin "P$1") (pinfunction "1_P$1") (pintype "passive"))
    )
    (net (code "96") (name "Net-(LED15-A)") (class "Default")
      (node (ref "LED15") (pin "1") (pinfunction "A_1") (pintype "passive"))
      (node (ref "R97") (pin "P$1") (pinfunction "1_P$1") (pintype "passive"))
    )
    (net (code "97") (name "Net-(LED16-A)") (class "Default")
      (node (ref "LED16") (pin "1") (pinfunction "A_1") (pintype "passive"))
      (node (ref "R100") (pin "P$1") (pinfunction "1_P$1") (pintype "passive"))
    )
    (net (code "98") (name "Net-(R22-2)") (class "Default")
      (node (ref "R22") (pin "P$2") (pinfunction "2_P$2") (pintype "passive"))
      (node (ref "U3") (pin "27") (pinfunction "USBHS_RREF_27") (pintype "bidirectional"))
    )
    (net (code "99") (name "Net-(R23-2)") (class "Default")
      (node (ref "R23") (pin "P$2") (pinfunction "2_P$2") (pintype "passive"))
      (node (ref "U3") (pin "64") (pinfunction "VLO1(DCDC)_64") (pintype "bidirectional"))
    )
    (net (code "100") (name "Net-(R24-2)") (class "Default")
      (node (ref "R24") (pin "P$2") (pinfunction "2_P$2") (pintype "passive"))
      (node (ref "U3") (pin "65") (pinfunction "VLO2(DCDC)_65") (pintype "bidirectional"))
    )
    (net (code "101") (name "Net-(R28-2)") (class "Default")
      (node (ref "R28") (pin "P$2") (pinfunction "2_P$2") (pintype "passive"))
      (node (ref "U5") (pin "1") (pinfunction "B(2)_1") (pintype "input"))
    )
    (net (code "102") (name "Net-(R29-2)") (class "Default")
      (node (ref "R29") (pin "P$2") (pinfunction "2_P$2") (pintype "passive"))
      (node (ref "U6") (pin "1") (pinfunction "B(2)_1") (pintype "input"))
    )
    (net (code "103") (name "Net-(R30-2)") (class "Default")
      (node (ref "R30") (pin "P$2") (pinfunction "2_P$2") (pintype "passive"))
      (node (ref "U7") (pin "1") (pinfunction "B(2)_1") (pintype "input"))
    )
    (net (code "104") (name "Net-(R35-2)") (class "Default")
      (node (ref "R35") (pin "P$2") (pinfunction "2_P$2") (pintype "passive"))
      (node (ref "U8") (pin "1") (pinfunction "B(2)_1") (pintype "input"))
    )
    (net (code "105") (name "Net-(R38-2)") (class "Default")
      (node (ref "R38") (pin "P$2") (pinfunction "2_P$2") (pintype "passive"))
      (node (ref "U10") (pin "1") (pinfunction "B(2)_1") (pintype "input"))
    )
    (net (code "106") (name "Net-(R39-2)") (class "Default")
      (node (ref "R39") (pin "P$2") (pinfunction "2_P$2") (pintype "passive"))
      (node (ref "U11") (pin "1") (pinfunction "B(2)_1") (pintype "input"))
    )
    (net (code "107") (name "Net-(R40-2)") (class "Default")
      (node (ref "R40") (pin "P$2") (pinfunction "2_P$2") (pintype "passive"))
      (node (ref "U12") (pin "1") (pinfunction "B(2)_1") (pintype "input"))
    )
    (net (code "108") (name "Net-(R44-2)") (class "Default")
      (node (ref "R44") (pin "P$2") (pinfunction "2_P$2") (pintype "passive"))
      (node (ref "U13") (pin "1") (pinfunction "B(2)_1") (pintype "input"))
    )
    (net (code "109") (name "Net-(R45-2)") (class "Default")
      (node (ref "R45") (pin "P$2") (pinfunction "2_P$2") (pintype "passive"))
      (node (ref "U14") (pin "1") (pinfunction "B(2)_1") (pintype "input"))
    )
    (net (code "110") (name "Net-(R46-2)") (class "Default")
      (node (ref "R46") (pin "P$2") (pinfunction "2_P$2") (pintype "passive"))
      (node (ref "U15") (pin "1") (pinfunction "B(2)_1") (pintype "input"))
    )
    (net (code "111") (name "Net-(R49-2)") (class "Default")
      (node (ref "R49") (pin "P$2") (pinfunction "2_P$2") (pintype "passive"))
      (node (ref "U16") (pin "1") (pinfunction "B(2)_1") (pintype "input"))
    )
    (net (code "112") (name "Net-(R50-2)") (class "Default")
      (node (ref "R50") (pin "P$2") (pinfunction "2_P$2") (pintype "passive"))
      (node (ref "U17") (pin "1") (pinfunction "B(2)_1") (pintype "input"))
    )
    (net (code "113") (name "Net-(R54-2)") (class "Default")
      (node (ref "R54") (pin "P$2") (pinfunction "2_P$2") (pintype "passive"))
      (node (ref "U9") (pin "1") (pinfunction "B(2)_1") (pintype "input"))
    )
    (net (code "114") (name "Net-(R57-2)") (class "Default")
      (node (ref "R57") (pin "P$2") (pinfunction "2_P$2") (pintype "passive"))
      (node (ref "U18") (pin "1") (pinfunction "B(2)_1") (pintype "input"))
    )
    (net (code "115") (name "Net-(R60-2)") (class "Default")
      (node (ref "R60") (pin "P$2") (pinfunction "2_P$2") (pintype "passive"))
      (node (ref "U19") (pin "1") (pinfunction "B(2)_1") (pintype "input"))
    )
    (net (code "116") (name "Net-(R62-2)") (class "Default")
      (node (ref "R62") (pin "P$2") (pinfunction "2_P$2") (pintype "passive"))
      (node (ref "U22") (pin "1") (pinfunction "B(2)_1") (pintype "input"))
    )
    (net (code "117") (name "Net-(R63-2)") (class "Default")
      (node (ref "R63") (pin "P$2") (pinfunction "2_P$2") (pintype "passive"))
      (node (ref "U23") (pin "1") (pinfunction "B(2)_1") (pintype "input"))
    )
    (net (code "118") (name "Net-(R64-2)") (class "Default")
      (node (ref "R64") (pin "P$2") (pinfunction "2_P$2") (pintype "passive"))
      (node (ref "U24") (pin "1") (pinfunction "B(2)_1") (pintype "input"))
    )
    (net (code "119") (name "Net-(R68-2)") (class "Default")
      (node (ref "R68") (pin "P$2") (pinfunction "2_P$2") (pintype "passive"))
      (node (ref "U25") (pin "1") (pinfunction "B(2)_1") (pintype "input"))
    )
    (net (code "120") (name "Net-(R69-2)") (class "Default")
      (node (ref "R69") (pin "P$2") (pinfunction "2_P$2") (pintype "passive"))
      (node (ref "U26") (pin "1") (pinfunction "B(2)_1") (pintype "input"))
    )
    (net (code "121") (name "Net-(R70-2)") (class "Default")
      (node (ref "R70") (pin "P$2") (pinfunction "2_P$2") (pintype "passive"))
      (node (ref "U27") (pin "1") (pinfunction "B(2)_1") (pintype "input"))
    )
    (net (code "122") (name "Net-(R75-2)") (class "Default")
      (node (ref "R75") (pin "P$2") (pinfunction "2_P$2") (pintype "passive"))
      (node (ref "U20") (pin "1") (pinfunction "B(2)_1") (pintype "input"))
    )
    (net (code "123") (name "Net-(R78-2)") (class "Default")
      (node (ref "R78") (pin "P$2") (pinfunction "2_P$2") (pintype "passive"))
      (node (ref "U21") (pin "1") (pinfunction "B(2)_1") (pintype "input"))
    )
    (net (code "124") (name "Net-(R81-2)") (class "Default")
      (node (ref "R81") (pin "P$2") (pinfunction "2_P$2") (pintype "passive"))
      (node (ref "U28") (pin "1") (pinfunction "B(2)_1") (pintype "input"))
    )
    (net (code "125") (name "Net-(R84-2)") (class "Default")
      (node (ref "R84") (pin "P$2") (pinfunction "2_P$2") (pintype "passive"))
      (node (ref "U29") (pin "1") (pinfunction "B(2)_1") (pintype "input"))
    )
    (net (code "126") (name "Net-(R86-2)") (class "Default")
      (node (ref "R86") (pin "P$2") (pinfunction "2_P$2") (pintype "passive"))
      (node (ref "U34") (pin "1") (pinfunction "B(2)_1") (pintype "input"))
    )
    (net (code "127") (name "Net-(R87-2)") (class "Default")
      (node (ref "R87") (pin "P$2") (pinfunction "2_P$2") (pintype "passive"))
      (node (ref "U35") (pin "1") (pinfunction "B(2)_1") (pintype "input"))
    )
    (net (code "128") (name "Net-(R88-2)") (class "Default")
      (node (ref "R88") (pin "P$2") (pinfunction "2_P$2") (pintype "passive"))
      (node (ref "U36") (pin "1") (pinfunction "B(2)_1") (pintype "input"))
    )
    (net (code "129") (name "Net-(R92-2)") (class "Default")
      (node (ref "R92") (pin "P$2") (pinfunction "2_P$2") (pintype "passive"))
      (node (ref "U37") (pin "1") (pinfunction "B(2)_1") (pintype "input"))
    )
    (net (code "130") (name "Net-(R93-2)") (class "Default")
      (node (ref "R93") (pin "P$2") (pinfunction "2_P$2") (pintype "passive"))
      (node (ref "U38") (pin "1") (pinfunction "B(2)_1") (pintype "input"))
    )
    (net (code "131") (name "Net-(R94-2)") (class "Default")
      (node (ref "R94") (pin "P$2") (pinfunction "2_P$2") (pintype "passive"))
      (node (ref "U39") (pin "1") (pinfunction "B(2)_1") (pintype "input"))
    )
    (net (code "132") (name "Net-(R99-2)") (class "Default")
      (node (ref "R99") (pin "P$2") (pinfunction "2_P$2") (pintype "passive"))
      (node (ref "U30") (pin "1") (pinfunction "B(2)_1") (pintype "input"))
    )
    (net (code "133") (name "Net-(R110-2)") (class "Default")
      (node (ref "R110") (pin "P$2") (pinfunction "2_P$2") (pintype "passive"))
      (node (ref "U46") (pin "1") (pinfunction "B(2)_1") (pintype "input"))
    )
    (net (code "134") (name "Net-(R111-2)") (class "Default")
      (node (ref "R111") (pin "P$2") (pinfunction "2_P$2") (pintype "passive"))
      (node (ref "U47") (pin "1") (pinfunction "B(2)_1") (pintype "input"))
    )
    (net (code "135") (name "Net-(R112-2)") (class "Default")
      (node (ref "R112") (pin "P$2") (pinfunction "2_P$2") (pintype "passive"))
      (node (ref "U48") (pin "1") (pinfunction "B(2)_1") (pintype "input"))
    )
    (net (code "136") (name "Net-(R116-2)") (class "Default")
      (node (ref "R116") (pin "P$2") (pinfunction "2_P$2") (pintype "passive"))
      (node (ref "U49") (pin "1") (pinfunction "B(2)_1") (pintype "input"))
    )
    (net (code "137") (name "Net-(R117-2)") (class "Default")
      (node (ref "R117") (pin "P$2") (pinfunction "2_P$2") (pintype "passive"))
      (node (ref "U50") (pin "1") (pinfunction "B(2)_1") (pintype "input"))
    )
    (net (code "138") (name "Net-(R118-2)") (class "Default")
      (node (ref "R118") (pin "P$2") (pinfunction "2_P$2") (pintype "passive"))
      (node (ref "U51") (pin "1") (pinfunction "B(2)_1") (pintype "input"))
    )
    (net (code "139") (name "Net-(R134-2)") (class "Default")
      (node (ref "R134") (pin "P$2") (pinfunction "2_P$2") (pintype "passive"))
      (node (ref "U58") (pin "1") (pinfunction "B(2)_1") (pintype "input"))
    )
    (net (code "140") (name "Net-(R135-2)") (class "Default")
      (node (ref "R135") (pin "P$2") (pinfunction "2_P$2") (pintype "passive"))
      (node (ref "U59") (pin "1") (pinfunction "B(2)_1") (pintype "input"))
    )
    (net (code "141") (name "Net-(R136-2)") (class "Default")
      (node (ref "R136") (pin "P$2") (pinfunction "2_P$2") (pintype "passive"))
      (node (ref "U60") (pin "1") (pinfunction "B(2)_1") (pintype "input"))
    )
    (net (code "142") (name "Net-(R140-2)") (class "Default")
      (node (ref "R140") (pin "P$2") (pinfunction "2_P$2") (pintype "passive"))
      (node (ref "U61") (pin "1") (pinfunction "B(2)_1") (pintype "input"))
    )
    (net (code "143") (name "Net-(R141-2)") (class "Default")
      (node (ref "R141") (pin "P$2") (pinfunction "2_P$2") (pintype "passive"))
      (node (ref "U62") (pin "1") (pinfunction "B(2)_1") (pintype "input"))
    )
    (net (code "144") (name "Net-(R142-2)") (class "Default")
      (node (ref "R142") (pin "P$2") (pinfunction "2_P$2") (pintype "passive"))
      (node (ref "U63") (pin "1") (pinfunction "B(2)_1") (pintype "input"))
    )
    (net (code "145") (name "Net-(R158-2)") (class "Default")
      (node (ref "R158") (pin "P$2") (pinfunction "2_P$2") (pintype "passive"))
      (node (ref "U70") (pin "1") (pinfunction "B(2)_1") (pintype "input"))
    )
    (net (code "146") (name "Net-(R159-2)") (class "Default")
      (node (ref "R159") (pin "P$2") (pinfunction "2_P$2") (pintype "passive"))
      (node (ref "U71") (pin "1") (pinfunction "B(2)_1") (pintype "input"))
    )
    (net (code "147") (name "Net-(R160-2)") (class "Default")
      (node (ref "R160") (pin "P$2") (pinfunction "2_P$2") (pintype "passive"))
      (node (ref "U72") (pin "1") (pinfunction "B(2)_1") (pintype "input"))
    )
    (net (code "148") (name "Net-(R164-2)") (class "Default")
      (node (ref "R164") (pin "P$2") (pinfunction "2_P$2") (pintype "passive"))
      (node (ref "U73") (pin "1") (pinfunction "B(2)_1") (pintype "input"))
    )
    (net (code "149") (name "Net-(R165-2)") (class "Default")
      (node (ref "R165") (pin "P$2") (pinfunction "2_P$2") (pintype "passive"))
      (node (ref "U74") (pin "1") (pinfunction "B(2)_1") (pintype "input"))
    )
    (net (code "150") (name "Net-(R166-2)") (class "Default")
      (node (ref "R166") (pin "P$2") (pinfunction "2_P$2") (pintype "passive"))
      (node (ref "U75") (pin "1") (pinfunction "B(2)_1") (pintype "input"))
    )
    (net (code "151") (name "P0_00") (class "Default")
      (node (ref "J4") (pin "P$2") (pinfunction "P$2_P$2") (pintype "bidirectional"))
      (node (ref "U3") (pin "169") (pinfunction "P0_0/AN0\\00_169") (pintype "bidirectional"))
    )
    (net (code "152") (name "P0_01") (class "Default")
      (node (ref "J4") (pin "P$1") (pinfunction "P$1_P$1") (pintype "bidirectional"))
      (node (ref "U3") (pin "168") (pinfunction "P0_1/AN001_168") (pintype "bidirectional"))
    )
    (net (code "153") (name "P0_02_TH_01") (class "Default")
      (node (ref "R25") (pin "P$1") (pinfunction "1_P$1") (pintype "passive"))
      (node (ref "TH01") (pin "2") (pinfunction "2_2") (pintype "passive"))
      (node (ref "U3") (pin "167") (pinfunction "P0_2/AN002_167") (pintype "bidirectional"))
    )
    (net (code "154") (name "P0_03") (class "Default")
      (node (ref "J8") (pin "P$6") (pinfunction "P$6_P$6") (pintype "bidirectional"))
      (node (ref "U3") (pin "166") (pinfunction "P0_3/PGAVSS000_166") (pintype "bidirectional"))
    )
    (net (code "155") (name "P0_04_TH_02") (class "Default")
      (node (ref "R27") (pin "P$1") (pinfunction "1_P$1") (pintype "passive"))
      (node (ref "TH02") (pin "2") (pinfunction "2_2") (pintype "passive"))
      (node (ref "U3") (pin "165") (pinfunction "P0_4/AN100_165") (pintype "bidirectional"))
    )
    (net (code "156") (name "P0_05_TH_03") (class "Default")
      (node (ref "R102") (pin "P$1") (pinfunction "1_P$1") (pintype "passive"))
      (node (ref "TH03") (pin "2") (pinfunction "2_2") (pintype "passive"))
      (node (ref "U3") (pin "164") (pinfunction "P0_5/AN101_164") (pintype "bidirectional"))
    )
    (net (code "157") (name "P0_06_TH_04") (class "Default")
      (node (ref "R103") (pin "P$1") (pinfunction "1_P$1") (pintype "passive"))
      (node (ref "TH04") (pin "2") (pinfunction "2_2") (pintype "passive"))
      (node (ref "U3") (pin "163") (pinfunction "P0_6/AN102_163") (pintype "bidirectional"))
    )
    (net (code "158") (name "P0_07") (class "Default")
      (node (ref "J8") (pin "P$12") (pinfunction "P$12_P$12") (pintype "bidirectional"))
      (node (ref "U3") (pin "162") (pinfunction "P0_7/PGVSS100_162") (pintype "bidirectional"))
    )
    (net (code "159") (name "P0_08_TH_05") (class "Default")
      (node (ref "R105") (pin "P$1") (pinfunction "1_P$1") (pintype "passive"))
      (node (ref "TH05") (pin "2") (pinfunction "2_2") (pintype "passive"))
      (node (ref "U3") (pin "161") (pinfunction "P0_8/AN003_161") (pintype "bidirectional"))
    )
    (net (code "160") (name "P0_09_TH_06") (class "Default")
      (node (ref "R106") (pin "P$1") (pinfunction "1_P$1") (pintype "passive"))
      (node (ref "TH06") (pin "2") (pinfunction "2_2") (pintype "passive"))
      (node (ref "U3") (pin "160") (pinfunction "P0_9/AN004_160") (pintype "bidirectional"))
    )
    (net (code "161") (name "P0_14_TH_07") (class "Default")
      (node (ref "R107") (pin "P$1") (pinfunction "1_P$1") (pintype "passive"))
      (node (ref "TH07") (pin "2") (pinfunction "2_2") (pintype "passive"))
      (node (ref "U3") (pin "152") (pinfunction "P0_14/DA0/AN005/AN105_152") (pintype "bidirectional"))
    )
    (net (code "162") (name "P0_15_TH_08") (class "Default")
      (node (ref "R108") (pin "P$1") (pinfunction "1_P$1") (pintype "passive"))
      (node (ref "TH08") (pin "2") (pinfunction "2_2") (pintype "passive"))
      (node (ref "U3") (pin "151") (pinfunction "P0_15/DA1/AN006/AN106_151") (pintype "bidirectional"))
    )
    (net (code "163") (name "P1_02") (class "Default")
      (node (ref "J8") (pin "P$10") (pinfunction "P$10_P$10") (pintype "bidirectional"))
      (node (ref "U3") (pin "130") (pinfunction "P1_2_130") (pintype "bidirectional"))
    )
    (net (code "164") (name "P1_03") (class "Default")
      (node (ref "J8") (pin "P$9") (pinfunction "P$9_P$9") (pintype "bidirectional"))
      (node (ref "U3") (pin "129") (pinfunction "P1_3_129") (pintype "bidirectional"))
    )
    (net (code "165") (name "P1_04") (class "Default")
      (node (ref "J8") (pin "P$11") (pinfunction "P$11_P$11") (pintype "bidirectional"))
      (node (ref "U3") (pin "128") (pinfunction "P1_4_128") (pintype "bidirectional"))
    )
    (net (code "166") (name "P1_05") (class "Default")
      (node (ref "J8") (pin "P$13") (pinfunction "P$13_P$13") (pintype "bidirectional"))
      (node (ref "U3") (pin "127") (pinfunction "P1_5_127") (pintype "bidirectional"))
    )
    (net (code "167") (name "P1_06") (class "Default")
      (node (ref "J8") (pin "P$15") (pinfunction "P$15_P$15") (pintype "bidirectional"))
      (node (ref "U3") (pin "126") (pinfunction "P1_6_126") (pintype "bidirectional"))
    )
    (net (code "168") (name "P1_07") (class "Default")
      (node (ref "J8") (pin "P$17") (pinfunction "P$17_P$17") (pintype "bidirectional"))
      (node (ref "U3") (pin "125") (pinfunction "P1_7_125") (pintype "bidirectional"))
    )
    (net (code "169") (name "P4_00") (class "Default")
      (node (ref "J4") (pin "P$7") (pinfunction "P$7_P$7") (pintype "bidirectional"))
      (node (ref "U3") (pin "1") (pinfunction "P4_0_1") (pintype "bidirectional"))
    )
    (net (code "170") (name "P4_01") (class "Default")
      (node (ref "J4") (pin "P$8") (pinfunction "P$8_P$8") (pintype "bidirectional"))
      (node (ref "U3") (pin "2") (pinfunction "P4_1_2") (pintype "bidirectional"))
    )
    (net (code "171") (name "P4_02") (class "Default")
      (node (ref "J4") (pin "P$9") (pinfunction "P$9_P$9") (pintype "bidirectional"))
      (node (ref "U3") (pin "3") (pinfunction "P4_2_3") (pintype "bidirectional"))
    )
    (net (code "172") (name "P4_08") (class "Default")
      (node (ref "J4") (pin "P$20") (pinfunction "P$20_P$20") (pintype "bidirectional"))
      (node (ref "U3") (pin "43") (pinfunction "P4_8_43") (pintype "bidirectional"))
    )
    (net (code "173") (name "P4_09") (class "Default")
      (node (ref "J4") (pin "P$19") (pinfunction "P$19_P$19") (pintype "bidirectional"))
      (node (ref "U3") (pin "42") (pinfunction "P4_9_42") (pintype "bidirectional"))
    )
    (net (code "174") (name "P4_10") (class "Default")
      (node (ref "J4") (pin "P$18") (pinfunction "P$18_P$18") (pintype "bidirectional"))
      (node (ref "U3") (pin "41") (pinfunction "P4_10_41") (pintype "bidirectional"))
    )
    (net (code "175") (name "P4_11") (class "Default")
      (node (ref "J4") (pin "P$17") (pinfunction "P$17_P$17") (pintype "bidirectional"))
      (node (ref "U3") (pin "40") (pinfunction "P4_11_40") (pintype "bidirectional"))
    )
    (net (code "176") (name "P4_12") (class "Default")
      (node (ref "J4") (pin "P$16") (pinfunction "P$16_P$16") (pintype "bidirectional"))
      (node (ref "U3") (pin "39") (pinfunction "P4_12_39") (pintype "bidirectional"))
    )
    (net (code "177") (name "P4_13") (class "Default")
      (node (ref "J4") (pin "P$15") (pinfunction "P$15_P$15") (pintype "bidirectional"))
      (node (ref "U3") (pin "38") (pinfunction "P4_13_38") (pintype "bidirectional"))
    )
    (net (code "178") (name "P4_14") (class "Default")
      (node (ref "J4") (pin "P$14") (pinfunction "P$14_P$14") (pintype "bidirectional"))
      (node (ref "U3") (pin "37") (pinfunction "P4_14_37") (pintype "bidirectional"))
    )
    (net (code "179") (name "P4_15") (class "Default")
      (node (ref "J4") (pin "P$13") (pinfunction "P$13_P$13") (pintype "bidirectional"))
      (node (ref "U3") (pin "36") (pinfunction "P4_15_36") (pintype "bidirectional"))
    )
    (net (code "180") (name "P5_11") (class "Default")
      (node (ref "J4") (pin "P$6") (pinfunction "P$6_P$6") (pintype "bidirectional"))
      (node (ref "U3") (pin "176") (pinfunction "P5_11_176") (pintype "bidirectional"))
    )
    (net (code "181") (name "P5_12") (class "Default")
      (node (ref "J4") (pin "P$5") (pinfunction "P$5_P$5") (pintype "bidirectional"))
      (node (ref "U3") (pin "175") (pinfunction "P5_12_175") (pintype "bidirectional"))
    )
    (net (code "182") (name "P5_13") (class "Default")
      (node (ref "J4") (pin "P$4") (pinfunction "P$4_P$4") (pintype "bidirectional"))
      (node (ref "U3") (pin "174") (pinfunction "P5_13_174") (pintype "bidirectional"))
    )
    (net (code "183") (name "P6_00") (class "Default")
      (node (ref "J8") (pin "P$19") (pinfunction "P$19_P$19") (pintype "bidirectional"))
      (node (ref "U3") (pin "122") (pinfunction "P6_0_122") (pintype "bidirectional"))
    )
    (net (code "184") (name "P7_06") (class "Default")
      (node (ref "J4") (pin "P$10") (pinfunction "P$10_P$10") (pintype "bidirectional"))
      (node (ref "U3") (pin "14") (pinfunction "P7_6_14") (pintype "bidirectional"))
    )
    (net (code "185") (name "P7_07") (class "Default")
      (node (ref "J4") (pin "P$11") (pinfunction "P$11_P$11") (pintype "bidirectional"))
      (node (ref "U3") (pin "15") (pinfunction "P7_7_15") (pintype "bidirectional"))
    )
    (net (code "186") (name "P8_00") (class "Default")
      (node (ref "J8") (pin "P$5") (pinfunction "P$5_P$5") (pintype "bidirectional"))
      (node (ref "U3") (pin "133") (pinfunction "P8_0_133") (pintype "bidirectional"))
    )
    (net (code "187") (name "P8_01") (class "Default")
      (node (ref "J8") (pin "P$3") (pinfunction "P$3_P$3") (pintype "bidirectional"))
      (node (ref "U3") (pin "134") (pinfunction "P8_1_134") (pintype "bidirectional"))
    )
    (net (code "188") (name "P8_02") (class "Default")
      (node (ref "J8") (pin "P$4") (pinfunction "P$4_P$4") (pintype "bidirectional"))
      (node (ref "U3") (pin "135") (pinfunction "P8_2_135") (pintype "bidirectional"))
    )
    (net (code "189") (name "P8_03") (class "Default")
      (node (ref "J8") (pin "P$1") (pinfunction "P$1_P$1") (pintype "bidirectional"))
      (node (ref "U3") (pin "136") (pinfunction "P8_3_136") (pintype "bidirectional"))
    )
    (net (code "190") (name "P8_04") (class "Default")
      (node (ref "J8") (pin "P$2") (pinfunction "P$2_P$2") (pintype "bidirectional"))
      (node (ref "U3") (pin "137") (pinfunction "P8_4_137") (pintype "bidirectional"))
    )
    (net (code "191") (name "P8_05") (class "Default")
      (node (ref "J4") (pin "P$3") (pinfunction "P$3_P$3") (pintype "bidirectional"))
      (node (ref "U3") (pin "173") (pinfunction "P8_5_173") (pintype "bidirectional"))
    )
    (net (code "192") (name "PB_00") (class "Default")
      (node (ref "J4") (pin "P$12") (pinfunction "P$12_P$12") (pintype "bidirectional"))
      (node (ref "U3") (pin "16") (pinfunction "PB_0_16") (pintype "bidirectional"))
    )
    (net (code "193") (name "R51") (class "Default")
      (node (ref "R7") (pin "P$1") (pinfunction "1_P$1") (pintype "passive"))
      (node (ref "RJ1") (pin "12") (pinfunction "YHI_12") (pintype "bidirectional"))
    )
    (net (code "194") (name "R52") (class "Default")
      (node (ref "R8") (pin "P$1") (pinfunction "1_P$1") (pintype "passive"))
      (node (ref "RJ1") (pin "9") (pinfunction "GHI_9") (pintype "bidirectional"))
    )
    (net (code "195") (name "RELAY_1") (class "Default")
      (node (ref "R29") (pin "P$1") (pinfunction "1_P$1") (pintype "passive"))
      (node (ref "U3") (pin "56") (pinfunction "P3_14_56") (pintype "bidirectional"))
    )
    (net (code "196") (name "RELAY_2") (class "Default")
      (node (ref "R30") (pin "P$1") (pinfunction "1_P$1") (pintype "passive"))
      (node (ref "U3") (pin "55") (pinfunction "P3_13_55") (pintype "bidirectional"))
    )
    (net (code "197") (name "RELAY_3") (class "Default")
      (node (ref "R49") (pin "P$1") (pinfunction "1_P$1") (pintype "passive"))
      (node (ref "U3") (pin "52") (pinfunction "P2_4_52") (pintype "bidirectional"))
    )
    (net (code "198") (name "RELAY_4") (class "Default")
      (node (ref "R50") (pin "P$1") (pinfunction "1_P$1") (pintype "passive"))
      (node (ref "U3") (pin "49") (pinfunction "P2_7_49") (pintype "bidirectional"))
    )
    (net (code "199") (name "RESET") (class "Default")
      (node (ref "C16") (pin "P$1") (pinfunction "1_P$1") (pintype "passive"))
      (node (ref "J3") (pin "9") (pinfunction "9_9") (pintype "passive"))
      (node (ref "R13") (pin "P$1") (pinfunction "1_P$1") (pintype "passive"))
      (node (ref "U3") (pin "67") (pinfunction "RES#_67") (pintype "bidirectional"))
    )
    (net (code "200") (name "REXT") (class "Default")
      (node (ref "C3") (pin "P$1") (pinfunction "1_P$1") (pintype "passive"))
      (node (ref "R1") (pin "P$2") (pinfunction "2_P$2") (pintype "passive"))
      (node (ref "U1") (pin "9") (pinfunction "REXT_9") (pintype "input"))
    )
    (net (code "201") (name "RO_NEG_1") (class "Default")
      (node (ref "J15") (pin "P$2") (pinfunction "P$2_P$2") (pintype "bidirectional"))
      (node (ref "U$1") (pin "P$3") (pinfunction "VO-_P$3") (pintype "bidirectional"))
    )
    (net (code "202") (name "RO_NEG_2") (class "Default")
      (node (ref "J16") (pin "P$2") (pinfunction "P$2_P$2") (pintype "bidirectional"))
      (node (ref "U$2") (pin "P$3") (pinfunction "VO-_P$3") (pintype "bidirectional"))
    )
    (net (code "203") (name "RO_NEG_3") (class "Default")
      (node (ref "J23") (pin "P$2") (pinfunction "P$2_P$2") (pintype "bidirectional"))
      (node (ref "U$7") (pin "P$3") (pinfunction "VO-_P$3") (pintype "bidirectional"))
    )
    (net (code "204") (name "RO_NEG_4") (class "Default")
      (node (ref "J24") (pin "P$2") (pinfunction "P$2_P$2") (pintype "bidirectional"))
      (node (ref "U$8") (pin "P$3") (pinfunction "VO-_P$3") (pintype "bidirectional"))
    )
    (net (code "205") (name "RO_POS_1") (class "Default")
      (node (ref "J15") (pin "P$1") (pinfunction "P$1_P$1") (pintype "bidirectional"))
      (node (ref "U$1") (pin "P$4") (pinfunction "VO+_P$4") (pintype "bidirectional"))
    )
    (net (code "206") (name "RO_POS_2") (class "Default")
      (node (ref "J16") (pin "P$1") (pinfunction "P$1_P$1") (pintype "bidirectional"))
      (node (ref "U$2") (pin "P$4") (pinfunction "VO+_P$4") (pintype "bidirectional"))
    )
    (net (code "207") (name "RO_POS_3") (class "Default")
      (node (ref "J23") (pin "P$1") (pinfunction "P$1_P$1") (pintype "bidirectional"))
      (node (ref "U$7") (pin "P$4") (pinfunction "VO+_P$4") (pintype "bidirectional"))
    )
    (net (code "208") (name "RO_POS_4") (class "Default")
      (node (ref "J24") (pin "P$1") (pinfunction "P$1_P$1") (pintype "bidirectional"))
      (node (ref "U$8") (pin "P$4") (pinfunction "VO+_P$4") (pintype "bidirectional"))
    )
    (net (code "209") (name "RXD0") (class "Default")
      (node (ref "R10") (pin "P$2") (pinfunction "2_P$2") (pintype "passive"))
      (node (ref "U1") (pin "13") (pinfunction "RXD0_13") (pintype "bidirectional"))
    )
    (net (code "210") (name "RXD1") (class "Default")
      (node (ref "R9") (pin "P$2") (pinfunction "2_P$2") (pintype "passive"))
      (node (ref "U1") (pin "12") (pinfunction "RXD1_12") (pintype "bidirectional"))
    )
    (net (code "211") (name "RXER") (class "Default")
      (node (ref "R11") (pin "P$2") (pinfunction "2_P$2") (pintype "passive"))
      (node (ref "U1") (pin "17") (pinfunction "RXER_17") (pintype "bidirectional"))
    )
    (net (code "212") (name "RXM") (class "Default")
      (node (ref "RJ1") (pin "6") (pinfunction "RD-_6") (pintype "bidirectional"))
      (node (ref "U1") (pin "3") (pinfunction "RXM_3") (pintype "bidirectional"))
    )
    (net (code "213") (name "RXP") (class "Default")
      (node (ref "RJ1") (pin "3") (pinfunction "RD+_3") (pintype "bidirectional"))
      (node (ref "U1") (pin "4") (pinfunction "RXP_4") (pintype "bidirectional"))
    )
    (net (code "214") (name "SD1_CD") (class "Default")
      (node (ref "J1") (pin "10") (pinfunction "CD_SWITCH2_10") (pintype "bidirectional"))
      (node (ref "U3") (pin "146") (pinfunction "P5_6/AN019_146") (pintype "bidirectional"))
    )
    (net (code "215") (name "SD1_CLK") (class "Default")
      (node (ref "J1") (pin "5") (pinfunction "CLOCK_5") (pintype "bidirectional"))
      (node (ref "U3") (pin "140") (pinfunction "P5_0/AN016_140") (pintype "bidirectional"))
    )
    (net (code "216") (name "SD1_CMD") (class "Default")
      (node (ref "J1") (pin "3") (pinfunction "COMMAND/RESPONSE_3") (pintype "bidirectional"))
      (node (ref "U3") (pin "141") (pinfunction "P5_1/AN116_141") (pintype "bidirectional"))
    )
    (net (code "217") (name "SD1_DAT0") (class "Default")
      (node (ref "J1") (pin "7") (pinfunction "DATA_LINE[BIT_0]_7") (pintype "bidirectional"))
      (node (ref "U3") (pin "142") (pinfunction "P5_2/AN017_142") (pintype "bidirectional"))
    )
    (net (code "218") (name "SD1_DAT1") (class "Default")
      (node (ref "J1") (pin "8") (pinfunction "DATA_LINE[BIT_1]_8") (pintype "bidirectional"))
      (node (ref "U3") (pin "143") (pinfunction "P5_3/AN117_143") (pintype "bidirectional"))
    )
    (net (code "219") (name "SD1_DAT2") (class "Default")
      (node (ref "J1") (pin "1") (pinfunction "DATA_LINE[BIT_2]_1") (pintype "bidirectional"))
      (node (ref "U3") (pin "144") (pinfunction "P5_4/AN018_144") (pintype "bidirectional"))
    )
    (net (code "220") (name "SD1_DAT3") (class "Default")
      (node (ref "J1") (pin "2") (pinfunction "CARD_DETECT/DATA_LINE[BIT_3]_2") (pintype "bidirectional"))
      (node (ref "U3") (pin "145") (pinfunction "P5_5/AN118_145") (pintype "bidirectional"))
    )
    (net (code "221") (name "SD1_WP") (class "Default")
      (node (ref "J1") (pin "9") (pinfunction "CD_SWITCH1_9") (pintype "bidirectional"))
      (node (ref "U3") (pin "147") (pinfunction "P5_7/AN119_147") (pintype "bidirectional"))
    )
    (net (code "222") (name "TCK") (class "Default")
      (node (ref "J3") (pin "7") (pinfunction "7_7") (pintype "passive"))
      (node (ref "U3") (pin "88") (pinfunction "P3_0_88") (pintype "bidirectional"))
    )
    (net (code "223") (name "TDI") (class "Default")
      (node (ref "J3") (pin "1") (pinfunction "1_1") (pintype "passive"))
      (node (ref "U3") (pin "91") (pinfunction "P1_10_91") (pintype "bidirectional"))
    )
    (net (code "224") (name "TDO") (class "Default")
      (node (ref "J3") (pin "3") (pinfunction "3_3") (pintype "passive"))
      (node (ref "U3") (pin "90") (pinfunction "P1_9_90") (pintype "bidirectional"))
    )
    (net (code "225") (name "TMS") (class "Default")
      (node (ref "J3") (pin "5") (pinfunction "5_5") (pintype "passive"))
      (node (ref "U3") (pin "89") (pinfunction "P1_8_89") (pintype "bidirectional"))
    )
    (net (code "226") (name "TXM") (class "Default")
      (node (ref "RJ1") (pin "2") (pinfunction "TD-_2") (pintype "bidirectional"))
      (node (ref "U1") (pin "5") (pinfunction "TXM_5") (pintype "bidirectional"))
    )
    (net (code "227") (name "TXP") (class "Default")
      (node (ref "RJ1") (pin "1") (pinfunction "TD+_1") (pintype "bidirectional"))
      (node (ref "U1") (pin "6") (pinfunction "TXP_6") (pintype "bidirectional"))
    )
    (net (code "228") (name "USBHS_FAULT") (class "Default")
      (node (ref "R19") (pin "P$1") (pinfunction "1_P$1") (pintype "passive"))
      (node (ref "U2") (pin "3") (pinfunction "FLG_3") (pintype "input"))
      (node (ref "U3") (pin "78") (pinfunction "P3_8_78") (pintype "bidirectional"))
    )
    (net (code "229") (name "USBHS_N") (class "Default")
      (node (ref "J6") (pin "D-") (pinfunction "D-_D-") (pintype "bidirectional"))
      (node (ref "U3") (pin "31") (pinfunction "USBHS_DM_31") (pintype "bidirectional"))
    )
    (net (code "230") (name "USBHS_P") (class "Default")
      (node (ref "J6") (pin "D+") (pinfunction "D+_D+") (pintype "bidirectional"))
      (node (ref "U3") (pin "32") (pinfunction "USBHS_DP_32") (pintype "bidirectional"))
    )
    (net (code "231") (name "USBHS_VBUS") (class "Default")
      (node (ref "C29") (pin "P$1") (pinfunction "1_P$1") (pintype "passive"))
      (node (ref "C31") (pin "1") (pinfunction "1_1") (pintype "passive"))
      (node (ref "J6") (pin "VBUS") (pinfunction "VBUS_VBUS") (pintype "power_in"))
      (node (ref "U2") (pin "5") (pinfunction "OUT_5") (pintype "input"))
      (node (ref "U3") (pin "17") (pinfunction "PB_1_17") (pintype "bidirectional"))
    )
    (net (code "232") (name "USBHS_VBUSEN") (class "Default")
      (node (ref "R20") (pin "P$1") (pinfunction "1_P$1") (pintype "passive"))
      (node (ref "U2") (pin "1") (pinfunction "EN_1") (pintype "input"))
    )
    (net (code "233") (name "USB_N") (class "Default")
      (node (ref "R17") (pin "P$1") (pinfunction "1_P$1") (pintype "passive"))
      (node (ref "U3") (pin "46") (pinfunction "USB_DM_46") (pintype "bidirectional"))
    )
    (net (code "234") (name "USB_P") (class "Default")
      (node (ref "R18") (pin "P$1") (pinfunction "1_P$1") (pintype "passive"))
      (node (ref "U3") (pin "47") (pinfunction "USB_DP_47") (pintype "bidirectional"))
    )
    (net (code "235") (name "USB_VBUS_B") (class "Default")
      (node (ref "R16") (pin "P$1") (pinfunction "1_P$1") (pintype "passive"))
      (node (ref "U3") (pin "44") (pinfunction "P4_7_44") (pintype "bidirectional"))
    )
    (net (code "236") (name "VCL_F(FLASH)") (class "Default")
      (node (ref "C34") (pin "P$2") (pinfunction "2_P$2") (pintype "passive"))
      (node (ref "U3") (pin "112") (pinfunction "VCL_F(FLASH)_112") (pintype "bidirectional"))
    )
    (net (code "237") (name "VDD") (class "Default")
      (node (ref "C14") (pin "P$1") (pinfunction "1_P$1") (pintype "passive"))
      (node (ref "C15") (pin "P$1") (pinfunction "1_P$1") (pintype "passive"))
      (node (ref "C19") (pin "P$2") (pinfunction "2_P$2") (pintype "passive"))
      (node (ref "C20") (pin "P$2") (pinfunction "2_P$2") (pintype "passive"))
      (node (ref "C21") (pin "P$2") (pinfunction "2_P$2") (pintype "passive"))
      (node (ref "C22") (pin "P$2") (pinfunction "2_P$2") (pintype "passive"))
      (node (ref "C25") (pin "P$2") (pinfunction "2_P$2") (pintype "passive"))
      (node (ref "C27") (pin "P$2") (pinfunction "2_P$2") (pintype "passive"))
      (node (ref "C30") (pin "P$2") (pinfunction "2_P$2") (pintype "passive"))
      (node (ref "C35") (pin "P$2") (pinfunction "2_P$2") (pintype "passive"))
      (node (ref "C36") (pin "P$1") (pinfunction "1_P$1") (pintype "passive"))
      (node (ref "C38") (pin "P$2") (pinfunction "2_P$2") (pintype "passive"))
      (node (ref "C39") (pin "P$1") (pinfunction "1_P$1") (pintype "passive"))
      (node (ref "C4") (pin "P$1") (pinfunction "1_P$1") (pintype "passive"))
      (node (ref "C40") (pin "P$1") (pinfunction "1_P$1") (pintype "passive"))
      (node (ref "C41") (pin "P$1") (pinfunction "1_P$1") (pintype "passive"))
      (node (ref "C43") (pin "P$2") (pinfunction "2_P$2") (pintype "passive"))
      (node (ref "C5") (pin "P$1") (pinfunction "1_P$1") (pintype "passive"))
      (node (ref "C7") (pin "P$1") (pinfunction "1_P$1") (pintype "passive"))
      (node (ref "FB1") (pin "1") (pinfunction "P$1_1") (pintype "bidirectional"))
      (node (ref "J1") (pin "4") (pinfunction "SUPPLY_VOLTAGE_4") (pintype "power_in"))
      (node (ref "J3") (pin "2") (pinfunction "2_2") (pintype "passive"))
      (node (ref "J3") (pin "4") (pinfunction "4_4") (pintype "passive"))
      (node (ref "L1") (pin "2") (pinfunction "P$2_2") (pintype "bidirectional"))
      (node (ref "R102") (pin "P$2") (pinfunction "2_P$2") (pintype "passive"))
      (node (ref "R103") (pin "P$2") (pinfunction "2_P$2") (pintype "passive"))
      (node (ref "R105") (pin "P$2") (pinfunction "2_P$2") (pintype "passive"))
      (node (ref "R106") (pin "P$2") (pinfunction "2_P$2") (pintype "passive"))
      (node (ref "R107") (pin "P$2") (pinfunction "2_P$2") (pintype "passive"))
      (node (ref "R108") (pin "P$2") (pinfunction "2_P$2") (pintype "passive"))
      (node (ref "R13") (pin "P$2") (pinfunction "2_P$2") (pintype "passive"))
      (node (ref "R14") (pin "P$1") (pinfunction "1_P$1") (pintype "passive"))
      (node (ref "R15") (pin "P$1") (pinfunction "1_P$1") (pintype "passive"))
      (node (ref "R2") (pin "P$2") (pinfunction "2_P$2") (pintype "passive"))
      (node (ref "R25") (pin "P$2") (pinfunction "2_P$2") (pintype "passive"))
      (node (ref "R27") (pin "P$2") (pinfunction "2_P$2") (pintype "passive"))
      (node (ref "R3") (pin "P$2") (pinfunction "2_P$2") (pintype "passive"))
      (node (ref "R4") (pin "P$2") (pinfunction "2_P$2") (pintype "passive"))
      (node (ref "R5") (pin "P$2") (pinfunction "2_P$2") (pintype "passive"))
      (node (ref "R6") (pin "P$2") (pinfunction "2_P$2") (pintype "passive"))
      (node (ref "R7") (pin "P$2") (pinfunction "2_P$2") (pintype "passive"))
      (node (ref "R8") (pin "P$2") (pinfunction "2_P$2") (pintype "passive"))
      (node (ref "U1") (pin "14") (pinfunction "VDDIO_14") (pintype "power_in"))
      (node (ref "U18") (pin "3") (pinfunction "C(3)_3") (pintype "input"))
      (node (ref "U19") (pin "3") (pinfunction "C(3)_3") (pintype "input"))
      (node (ref "U20") (pin "3") (pinfunction "C(3)_3") (pintype "input"))
      (node (ref "U21") (pin "3") (pinfunction "C(3)_3") (pintype "input"))
      (node (ref "U28") (pin "3") (pinfunction "C(3)_3") (pintype "input"))
      (node (ref "U29") (pin "3") (pinfunction "C(3)_3") (pintype "input"))
      (node (ref "U3") (pin "110") (pinfunction "VCC(IO)5_110") (pintype "bidirectional"))
      (node (ref "U3") (pin "123") (pinfunction "VCC(IO)6_123") (pintype "bidirectional"))
      (node (ref "U3") (pin "138") (pinfunction "VCC(IO)7_138") (pintype "bidirectional"))
      (node (ref "U3") (pin "149") (pinfunction "VCC(IO)8_149") (pintype "bidirectional"))
      (node (ref "U3") (pin "154") (pinfunction "VREFH_154") (pintype "bidirectional"))
      (node (ref "U3") (pin "155") (pinfunction "AVCC0_155") (pintype "bidirectional"))
      (node (ref "U3") (pin "158") (pinfunction "VREFH0_158") (pintype "bidirectional"))
      (node (ref "U3") (pin "171") (pinfunction "VCC(IO)9_171") (pintype "bidirectional"))
      (node (ref "U3") (pin "25") (pinfunction "VCC1_25") (pintype "bidirectional"))
      (node (ref "U3") (pin "26") (pinfunction "AVCC_SUBHS_26") (pintype "bidirectional"))
      (node (ref "U3") (pin "34") (pinfunction "VCC_USBHS_34") (pintype "bidirectional"))
      (node (ref "U3") (pin "48") (pinfunction "VCC_USB_48") (pintype "bidirectional"))
      (node (ref "U3") (pin "61") (pinfunction "VCC(IO)2_61") (pintype "bidirectional"))
      (node (ref "U3") (pin "84") (pinfunction "VCC(IO)3_84") (pintype "bidirectional"))
      (node (ref "U3") (pin "97") (pinfunction "VCC(IO)4_97") (pintype "bidirectional"))
      (node (ref "U30") (pin "3") (pinfunction "C(3)_3") (pintype "input"))
      (node (ref "U5") (pin "3") (pinfunction "C(3)_3") (pintype "input"))
      (node (ref "U8") (pin "3") (pinfunction "C(3)_3") (pintype "input"))
      (node (ref "U9") (pin "3") (pinfunction "C(3)_3") (pintype "input"))
    )
    (net (code "238") (name "VDD5") (class "Default")
      (node (ref "C23") (pin "P$1") (pinfunction "1_P$1") (pintype "passive"))
      (node (ref "C26") (pin "P$1") (pinfunction "1_P$1") (pintype "passive"))
      (node (ref "J2") (pin "P$3") (pinfunction "P$3_P$3") (pintype "bidirectional"))
      (node (ref "R19") (pin "P$2") (pinfunction "2_P$2") (pintype "passive"))
      (node (ref "R20") (pin "P$2") (pinfunction "2_P$2") (pintype "passive"))
      (node (ref "R31") (pin "P$2") (pinfunction "2_P$2") (pintype "passive"))
      (node (ref "R32") (pin "P$2") (pinfunction "2_P$2") (pintype "passive"))
      (node (ref "R51") (pin "P$2") (pinfunction "2_P$2") (pintype "passive"))
      (node (ref "R52") (pin "P$2") (pinfunction "2_P$2") (pintype "passive"))
      (node (ref "U$1") (pin "P$2") (pinfunction "VC+_P$2") (pintype "bidirectional"))
      (node (ref "U$2") (pin "P$2") (pinfunction "VC+_P$2") (pintype "bidirectional"))
      (node (ref "U$7") (pin "P$2") (pinfunction "VC+_P$2") (pintype "bidirectional"))
      (node (ref "U$8") (pin "P$2") (pinfunction "VC+_P$2") (pintype "bidirectional"))
      (node (ref "U2") (pin "4") (pinfunction "VIN_4") (pintype "input"))
    )
    (net (code "239") (name "VDDIN") (class "Default")
      (node (ref "J2") (pin "P$2") (pinfunction "P$2_P$2") (pintype "bidirectional"))
      (node (ref "L1") (pin "1") (pinfunction "P$1_1") (pintype "bidirectional"))
    )
    (net (code "240") (name "VDDLS") (class "Default")
      (node (ref "J10") (pin "3") (pinfunction "3_3") (pintype "passive"))
      (node (ref "J11") (pin "3") (pinfunction "3_3") (pintype "passive"))
      (node (ref "J12") (pin "3") (pinfunction "3_3") (pintype "passive"))
      (node (ref "J19") (pin "3") (pinfunction "3_3") (pintype "passive"))
      (node (ref "J20") (pin "3") (pinfunction "3_3") (pintype "passive"))
      (node (ref "J27") (pin "3") (pinfunction "3_3") (pintype "passive"))
      (node (ref "J28") (pin "3") (pinfunction "3_3") (pintype "passive"))
      (node (ref "J31") (pin "3") (pinfunction "3_3") (pintype "passive"))
      (node (ref "J32") (pin "3") (pinfunction "3_3") (pintype "passive"))
      (node (ref "J35") (pin "P$1") (pinfunction "P$1_P$1") (pintype "bidirectional"))
      (node (ref "J35") (pin "P$2") (pinfunction "P$2_P$2") (pintype "bidirectional"))
      (node (ref "J5") (pin "3") (pinfunction "3_3") (pintype "passive"))
    )
    (net (code "241") (name "VDDMTR") (class "Default")
      (node (ref "J13") (pin "1") (pinfunction "1-HLFB+_1") (pintype "passive"))
      (node (ref "J13") (pin "2") (pinfunction "2-INPUT_B+_2") (pintype "passive"))
      (node (ref "J13") (pin "3") (pinfunction "3-INPUT_A+_3") (pintype "passive"))
      (node (ref "J13") (pin "4") (pinfunction "4-ENABLE+_4") (pintype "passive"))
      (node (ref "J14") (pin "1") (pinfunction "1-HLFB+_1") (pintype "passive"))
      (node (ref "J14") (pin "2") (pinfunction "2-INPUT_B+_2") (pintype "passive"))
      (node (ref "J14") (pin "3") (pinfunction "3-INPUT_A+_3") (pintype "passive"))
      (node (ref "J14") (pin "4") (pinfunction "4-ENABLE+_4") (pintype "passive"))
      (node (ref "J17") (pin "1") (pinfunction "1-HLFB+_1") (pintype "passive"))
      (node (ref "J17") (pin "2") (pinfunction "2-INPUT_B+_2") (pintype "passive"))
      (node (ref "J17") (pin "3") (pinfunction "3-INPUT_A+_3") (pintype "passive"))
      (node (ref "J17") (pin "4") (pinfunction "4-ENABLE+_4") (pintype "passive"))
      (node (ref "J18") (pin "1") (pinfunction "1-HLFB+_1") (pintype "passive"))
      (node (ref "J18") (pin "2") (pinfunction "2-INPUT_B+_2") (pintype "passive"))
      (node (ref "J18") (pin "3") (pinfunction "3-INPUT_A+_3") (pintype "passive"))
      (node (ref "J18") (pin "4") (pinfunction "4-ENABLE+_4") (pintype "passive"))
      (node (ref "J21") (pin "1") (pinfunction "1-HLFB+_1") (pintype "passive"))
      (node (ref "J21") (pin "2") (pinfunction "2-INPUT_B+_2") (pintype "passive"))
      (node (ref "J21") (pin "3") (pinfunction "3-INPUT_A+_3") (pintype "passive"))
      (node (ref "J21") (pin "4") (pinfunction "4-ENABLE+_4") (pintype "passive"))
      (node (ref "J22") (pin "1") (pinfunction "1-HLFB+_1") (pintype "passive"))
      (node (ref "J22") (pin "2") (pinfunction "2-INPUT_B+_2") (pintype "passive"))
      (node (ref "J22") (pin "3") (pinfunction "3-INPUT_A+_3") (pintype "passive"))
      (node (ref "J22") (pin "4") (pinfunction "4-ENABLE+_4") (pintype "passive"))
      (node (ref "J25") (pin "1") (pinfunction "1-HLFB+_1") (pintype "passive"))
      (node (ref "J25") (pin "2") (pinfunction "2-INPUT_B+_2") (pintype "passive"))
      (node (ref "J25") (pin "3") (pinfunction "3-INPUT_A+_3") (pintype "passive"))
      (node (ref "J25") (pin "4") (pinfunction "4-ENABLE+_4") (pintype "passive"))
      (node (ref "J26") (pin "1") (pinfunction "1-HLFB+_1") (pintype "passive"))
      (node (ref "J26") (pin "2") (pinfunction "2-INPUT_B+_2") (pintype "passive"))
      (node (ref "J26") (pin "3") (pinfunction "3-INPUT_A+_3") (pintype "passive"))
      (node (ref "J26") (pin "4") (pinfunction "4-ENABLE+_4") (pintype "passive"))
      (node (ref "J29") (pin "1") (pinfunction "1-HLFB+_1") (pintype "passive"))
      (node (ref "J29") (pin "2") (pinfunction "2-INPUT_B+_2") (pintype "passive"))
      (node (ref "J29") (pin "3") (pinfunction "3-INPUT_A+_3") (pintype "passive"))
      (node (ref "J29") (pin "4") (pinfunction "4-ENABLE+_4") (pintype "passive"))
      (node (ref "J30") (pin "1") (pinfunction "1-HLFB+_1") (pintype "passive"))
      (node (ref "J30") (pin "2") (pinfunction "2-INPUT_B+_2") (pintype "passive"))
      (node (ref "J30") (pin "3") (pinfunction "3-INPUT_A+_3") (pintype "passive"))
      (node (ref "J30") (pin "4") (pinfunction "4-ENABLE+_4") (pintype "passive"))
      (node (ref "J33") (pin "1") (pinfunction "1-HLFB+_1") (pintype "passive"))
      (node (ref "J33") (pin "2") (pinfunction "2-INPUT_B+_2") (pintype "passive"))
      (node (ref "J33") (pin "3") (pinfunction "3-INPUT_A+_3") (pintype "passive"))
      (node (ref "J33") (pin "4") (pinfunction "4-ENABLE+_4") (pintype "passive"))
      (node (ref "J34") (pin "1") (pinfunction "1-HLFB+_1") (pintype "passive"))
      (node (ref "J34") (pin "2") (pinfunction "2-INPUT_B+_2") (pintype "passive"))
      (node (ref "J34") (pin "3") (pinfunction "3-INPUT_A+_3") (pintype "passive"))
      (node (ref "J34") (pin "4") (pinfunction "4-ENABLE+_4") (pintype "passive"))
      (node (ref "J9") (pin "P$1") (pinfunction "P$1_P$1") (pintype "bidirectional"))
      (node (ref "J9") (pin "P$2") (pinfunction "P$2_P$2") (pintype "bidirectional"))
      (node (ref "R109") (pin "2") (pinfunction "2_2") (pintype "passive"))
      (node (ref "R113") (pin "2") (pinfunction "2_2") (pintype "passive"))
      (node (ref "R114") (pin "2") (pinfunction "2_2") (pintype "passive"))
      (node (ref "R115") (pin "2") (pinfunction "2_2") (pintype "passive"))
      (node (ref "R119") (pin "2") (pinfunction "2_2") (pintype "passive"))
      (node (ref "R120") (pin "2") (pinfunction "2_2") (pintype "passive"))
      (node (ref "R133") (pin "2") (pinfunction "2_2") (pintype "passive"))
      (node (ref "R137") (pin "2") (pinfunction "2_2") (pintype "passive"))
      (node (ref "R138") (pin "2") (pinfunction "2_2") (pintype "passive"))
      (node (ref "R139") (pin "2") (pinfunction "2_2") (pintype "passive"))
      (node (ref "R143") (pin "2") (pinfunction "2_2") (pintype "passive"))
      (node (ref "R144") (pin "2") (pinfunction "2_2") (pintype "passive"))
      (node (ref "R157") (pin "2") (pinfunction "2_2") (pintype "passive"))
      (node (ref "R161") (pin "2") (pinfunction "2_2") (pintype "passive"))
      (node (ref "R162") (pin "2") (pinfunction "2_2") (pintype "passive"))
      (node (ref "R163") (pin "2") (pinfunction "2_2") (pintype "passive"))
      (node (ref "R167") (pin "2") (pinfunction "2_2") (pintype "passive"))
      (node (ref "R168") (pin "2") (pinfunction "2_2") (pintype "passive"))
      (node (ref "R37") (pin "2") (pinfunction "2_2") (pintype "passive"))
      (node (ref "R41") (pin "2") (pinfunction "2_2") (pintype "passive"))
      (node (ref "R42") (pin "2") (pinfunction "2_2") (pintype "passive"))
      (node (ref "R43") (pin "2") (pinfunction "2_2") (pintype "passive"))
      (node (ref "R47") (pin "2") (pinfunction "2_2") (pintype "passive"))
      (node (ref "R48") (pin "2") (pinfunction "2_2") (pintype "passive"))
      (node (ref "R61") (pin "2") (pinfunction "2_2") (pintype "passive"))
      (node (ref "R65") (pin "2") (pinfunction "2_2") (pintype "passive"))
      (node (ref "R66") (pin "2") (pinfunction "2_2") (pintype "passive"))
      (node (ref "R67") (pin "2") (pinfunction "2_2") (pintype "passive"))
      (node (ref "R71") (pin "2") (pinfunction "2_2") (pintype "passive"))
      (node (ref "R72") (pin "2") (pinfunction "2_2") (pintype "passive"))
      (node (ref "R85") (pin "2") (pinfunction "2_2") (pintype "passive"))
      (node (ref "R89") (pin "2") (pinfunction "2_2") (pintype "passive"))
      (node (ref "R90") (pin "2") (pinfunction "2_2") (pintype "passive"))
      (node (ref "R91") (pin "2") (pinfunction "2_2") (pintype "passive"))
      (node (ref "R95") (pin "2") (pinfunction "2_2") (pintype "passive"))
      (node (ref "R96") (pin "2") (pinfunction "2_2") (pintype "passive"))
    )
    (net (code "242") (name "VDD_1.2") (class "Default")
      (node (ref "C10") (pin "P$1") (pinfunction "1_P$1") (pintype "passive"))
      (node (ref "C11") (pin "P$1") (pinfunction "1_P$1") (pintype "passive"))
      (node (ref "U1") (pin "1") (pinfunction "VDD_1.2_1") (pintype "power_in"))
    )
    (net (code "243") (name "WF_A_DIR") (class "Default")
      (node (ref "R159") (pin "P$1") (pinfunction "1_P$1") (pintype "passive"))
      (node (ref "U3") (pin "99") (pinfunction "P6_8_99") (pintype "bidirectional"))
    )
    (net (code "244") (name "WF_A_ENABLE") (class "Default")
      (node (ref "R160") (pin "P$1") (pinfunction "1_P$1") (pintype "passive"))
      (node (ref "U3") (pin "96") (pinfunction "P1_15_96") (pintype "bidirectional"))
    )
    (net (code "245") (name "WF_A_HLFB_OUT") (class "Default")
      (node (ref "J33") (pin "5") (pinfunction "5-HLFB-_5") (pintype "passive"))
    )
    (net (code "246") (name "WF_A_MI_DIR") (class "Default")
      (node (ref "J33") (pin "7") (pinfunction "7-INPUT_A-_7") (pintype "passive"))
      (node (ref "R161") (pin "1") (pinfunction "1_1") (pintype "passive"))
      (node (ref "U71") (pin "3") (pinfunction "C(3)_3") (pintype "input"))
    )
    (net (code "247") (name "WF_A_MI_ENABLE") (class "Default")
      (node (ref "J33") (pin "8") (pinfunction "8-ENABLE-_8") (pintype "passive"))
      (node (ref "R162") (pin "1") (pinfunction "1_1") (pintype "passive"))
      (node (ref "U72") (pin "3") (pinfunction "C(3)_3") (pintype "input"))
    )
    (net (code "248") (name "WF_A_MI_STEP") (class "Default")
      (node (ref "J33") (pin "6") (pinfunction "6-INPUT_B-_6") (pintype "passive"))
      (node (ref "R157") (pin "1") (pinfunction "1_1") (pintype "passive"))
      (node (ref "U70") (pin "3") (pinfunction "C(3)_3") (pintype "input"))
    )
    (net (code "249") (name "WF_A_STEP") (class "Default")
      (node (ref "R158") (pin "P$1") (pinfunction "1_P$1") (pintype "passive"))
      (node (ref "U3") (pin "100") (pinfunction "P6_9_100") (pintype "bidirectional"))
    )
    (net (code "250") (name "WF_B_DIR") (class "Default")
      (node (ref "R165") (pin "P$1") (pinfunction "1_P$1") (pintype "passive"))
      (node (ref "U3") (pin "94") (pinfunction "P1_13_94") (pintype "bidirectional"))
    )
    (net (code "251") (name "WF_B_ENABLE") (class "Default")
      (node (ref "R166") (pin "P$1") (pinfunction "1_P$1") (pintype "passive"))
      (node (ref "U3") (pin "93") (pinfunction "P1_12_93") (pintype "bidirectional"))
    )
    (net (code "252") (name "WF_B_HLFB_OUT") (class "Default")
      (node (ref "J34") (pin "5") (pinfunction "5-HLFB-_5") (pintype "passive"))
    )
    (net (code "253") (name "WF_B_MI_ENABLE") (class "Default")
      (node (ref "J34") (pin "8") (pinfunction "8-ENABLE-_8") (pintype "passive"))
      (node (ref "R168") (pin "1") (pinfunction "1_1") (pintype "passive"))
      (node (ref "U75") (pin "3") (pinfunction "C(3)_3") (pintype "input"))
    )
    (net (code "254") (name "WF_B_MI_STEP") (class "Default")
      (node (ref "J34") (pin "6") (pinfunction "6-INPUT_B-_6") (pintype "passive"))
      (node (ref "R163") (pin "1") (pinfunction "1_1") (pintype "passive"))
      (node (ref "U73") (pin "3") (pinfunction "C(3)_3") (pintype "input"))
    )
    (net (code "255") (name "WF_B_STEP") (class "Default")
      (node (ref "R164") (pin "P$1") (pinfunction "1_P$1") (pintype "passive"))
      (node (ref "U3") (pin "95") (pinfunction "P1_14_95") (pintype "bidirectional"))
    )
    (net (code "256") (name "XCIN") (class "Default")
      (node (ref "C32") (pin "P$1") (pinfunction "1_P$1") (pintype "passive"))
      (node (ref "U3") (pin "20") (pinfunction "XCIN_20") (pintype "bidirectional"))
      (node (ref "X3") (pin "P$1") (pinfunction "P$1_P$1") (pintype "bidirectional"))
    )
    (net (code "257") (name "XCOUT") (class "Default")
      (node (ref "C37") (pin "P$1") (pinfunction "1_P$1") (pintype "passive"))
      (node (ref "U3") (pin "21") (pinfunction "XCOUT_21") (pintype "bidirectional"))
      (node (ref "X3") (pin "P$2") (pinfunction "P$2_P$2") (pintype "bidirectional"))
    )
    (net (code "258") (name "XII") (class "Default")
      (node (ref "C1") (pin "P$1") (pinfunction "1_P$1") (pintype "passive"))
      (node (ref "U1") (pin "8") (pinfunction "XI_8") (pintype "input"))
      (node (ref "X1") (pin "1") (pinfunction "1_1") (pintype "bidirectional"))
    )
    (net (code "259") (name "XOO") (class "Default")
      (node (ref "C2") (pin "P$1") (pinfunction "1_P$1") (pintype "passive"))
      (node (ref "U1") (pin "7") (pinfunction "XO_7") (pintype "output"))
      (node (ref "X1") (pin "3") (pinfunction "3_3") (pintype "bidirectional"))
    )
    (net (code "260") (name "XTAL1") (class "Default")
      (node (ref "C17") (pin "P$1") (pinfunction "1_P$1") (pintype "passive"))
      (node (ref "U3") (pin "23") (pinfunction "P2_13/XTAL_23") (pintype "bidirectional"))
      (node (ref "X2") (pin "1") (pinfunction "1_1") (pintype "bidirectional"))
    )
    (net (code "261") (name "XTAL2") (class "Default")
      (node (ref "C18") (pin "P$1") (pinfunction "1_P$1") (pintype "passive"))
      (node (ref "U3") (pin "24") (pinfunction "P2_12/EXTAL_24") (pintype "bidirectional"))
      (node (ref "X2") (pin "3") (pinfunction "3_3") (pintype "bidirectional"))
    )
    (net (code "262") (name "X_A_DIR") (class "Default")
      (node (ref "R39") (pin "P$1") (pinfunction "1_P$1") (pintype "passive"))
      (node (ref "U3") (pin "117") (pinfunction "P6_5_117") (pintype "bidirectional"))
    )
    (net (code "263") (name "X_A_ENABLE") (class "Default")
      (node (ref "R40") (pin "P$1") (pinfunction "1_P$1") (pintype "passive"))
      (node (ref "U3") (pin "116") (pinfunction "P6_6_116") (pintype "bidirectional"))
    )
    (net (code "264") (name "X_A_HLFB_OUT") (class "Default")
      (node (ref "J13") (pin "5") (pinfunction "5-HLFB-_5") (pintype "passive"))
    )
    (net (code "265") (name "X_A_MI_DIR") (class "Default")
      (node (ref "J13") (pin "7") (pinfunction "7-INPUT_A-_7") (pintype "passive"))
      (node (ref "R41") (pin "1") (pinfunction "1_1") (pintype "passive"))
      (node (ref "U11") (pin "3") (pinfunction "C(3)_3") (pintype "input"))
    )
    (net (code "266") (name "X_A_MI_ENABLE") (class "Default")
      (node (ref "J13") (pin "8") (pinfunction "8-ENABLE-_8") (pintype "passive"))
      (node (ref "R42") (pin "1") (pinfunction "1_1") (pintype "passive"))
      (node (ref "U12") (pin "3") (pinfunction "C(3)_3") (pintype "input"))
    )
    (net (code "267") (name "X_A_MI_STEP") (class "Default")
      (node (ref "J13") (pin "6") (pinfunction "6-INPUT_B-_6") (pintype "passive"))
      (node (ref "R37") (pin "1") (pinfunction "1_1") (pintype "passive"))
      (node (ref "U10") (pin "3") (pinfunction "C(3)_3") (pintype "input"))
    )
    (net (code "268") (name "X_A_STEP") (class "Default")
      (node (ref "R38") (pin "P$1") (pinfunction "1_P$1") (pintype "passive"))
      (node (ref "U3") (pin "118") (pinfunction "P6_4_118") (pintype "bidirectional"))
    )
    (net (code "269") (name "X_B_DIR") (class "Default")
      (node (ref "R45") (pin "P$1") (pinfunction "1_P$1") (pintype "passive"))
      (node (ref "U3") (pin "120") (pinfunction "P6_2_120") (pintype "bidirectional"))
    )
    (net (code "270") (name "X_B_ENABLE") (class "Default")
      (node (ref "R46") (pin "P$1") (pinfunction "1_P$1") (pintype "passive"))
      (node (ref "U3") (pin "119") (pinfunction "P6_3_119") (pintype "bidirectional"))
    )
    (net (code "271") (name "X_B_HLFB_OUT") (class "Default")
      (node (ref "J14") (pin "5") (pinfunction "5-HLFB-_5") (pintype "passive"))
    )
    (net (code "272") (name "X_B_MI_DIR") (class "Default")
      (node (ref "J14") (pin "7") (pinfunction "7-INPUT_A-_7") (pintype "passive"))
      (node (ref "R47") (pin "1") (pinfunction "1_1") (pintype "passive"))
      (node (ref "U14") (pin "3") (pinfunction "C(3)_3") (pintype "input"))
    )
    (net (code "273") (name "X_B_MI_ENABLE") (class "Default")
      (node (ref "J14") (pin "8") (pinfunction "8-ENABLE-_8") (pintype "passive"))
      (node (ref "R48") (pin "1") (pinfunction "1_1") (pintype "passive"))
      (node (ref "U15") (pin "3") (pinfunction "C(3)_3") (pintype "input"))
    )
    (net (code "274") (name "X_B_MI_STEP") (class "Default")
      (node (ref "J14") (pin "6") (pinfunction "6-INPUT_B-_6") (pintype "passive"))
      (node (ref "R43") (pin "1") (pinfunction "1_1") (pintype "passive"))
      (node (ref "U13") (pin "3") (pinfunction "C(3)_3") (pintype "input"))
    )
    (net (code "275") (name "X_B_STEP") (class "Default")
      (node (ref "R44") (pin "P$1") (pinfunction "1_P$1") (pintype "passive"))
      (node (ref "U3") (pin "121") (pinfunction "P6_1_121") (pintype "bidirectional"))
    )
    (net (code "276") (name "Y_A_DIR") (class "Default")
      (node (ref "R63") (pin "P$1") (pinfunction "1_P$1") (pintype "passive"))
      (node (ref "U3") (pin "114") (pinfunction "PA_0_114") (pintype "bidirectional"))
    )
    (net (code "277") (name "Y_A_ENABLE") (class "Default")
      (node (ref "R64") (pin "P$1") (pinfunction "1_P$1") (pintype "passive"))
      (node (ref "U3") (pin "113") (pinfunction "PA_1_113") (pintype "bidirectional"))
    )
    (net (code "278") (name "Y_A_HLFB_OUT") (class "Default")
      (node (ref "J17") (pin "5") (pinfunction "5-HLFB-_5") (pintype "passive"))
    )
    (net (code "279") (name "Y_A_MI_DIR") (class "Default")
      (node (ref "J17") (pin "7") (pinfunction "7-INPUT_A-_7") (pintype "passive"))
      (node (ref "R65") (pin "1") (pinfunction "1_1") (pintype "passive"))
      (node (ref "U23") (pin "3") (pinfunction "C(3)_3") (pintype "input"))
    )
    (net (code "280") (name "Y_A_MI_ENABLE") (class "Default")
      (node (ref "J17") (pin "8") (pinfunction "8-ENABLE-_8") (pintype "passive"))
      (node (ref "R66") (pin "1") (pinfunction "1_1") (pintype "passive"))
      (node (ref "U24") (pin "3") (pinfunction "C(3)_3") (pintype "input"))
    )
    (net (code "281") (name "Y_A_MI_STEP") (class "Default")
      (node (ref "J17") (pin "6") (pinfunction "6-INPUT_B-_6") (pintype "passive"))
      (node (ref "R61") (pin "1") (pinfunction "1_1") (pintype "passive"))
      (node (ref "U22") (pin "3") (pinfunction "C(3)_3") (pintype "input"))
    )
    (net (code "282") (name "Y_A_STEP") (class "Default")
      (node (ref "R62") (pin "P$1") (pinfunction "1_P$1") (pintype "passive"))
      (node (ref "U3") (pin "115") (pinfunction "P6_7_115") (pintype "bidirectional"))
    )
    (net (code "283") (name "Y_B_DIR") (class "Default")
      (node (ref "R69") (pin "P$1") (pinfunction "1_P$1") (pintype "passive"))
      (node (ref "U3") (pin "108") (pinfunction "PA_9_108") (pintype "bidirectional"))
    )
    (net (code "284") (name "Y_B_ENABLE") (class "Default")
      (node (ref "R70") (pin "P$1") (pinfunction "1_P$1") (pintype "passive"))
      (node (ref "U3") (pin "107") (pinfunction "PA_8_107") (pintype "bidirectional"))
    )
    (net (code "285") (name "Y_B_HLFB_OUT") (class "Default")
      (node (ref "J18") (pin "5") (pinfunction "5-HLFB-_5") (pintype "passive"))
    )
    (net (code "286") (name "Y_B_MI_DIR") (class "Default")
      (node (ref "J18") (pin "7") (pinfunction "7-INPUT_A-_7") (pintype "passive"))
      (node (ref "R71") (pin "1") (pinfunction "1_1") (pintype "passive"))
      (node (ref "U26") (pin "3") (pinfunction "C(3)_3") (pintype "input"))
    )
    (net (code "287") (name "Y_B_MI_ENABLE") (class "Default")
      (node (ref "J18") (pin "8") (pinfunction "8-ENABLE-_8") (pintype "passive"))
      (node (ref "R72") (pin "1") (pinfunction "1_1") (pintype "passive"))
      (node (ref "U27") (pin "3") (pinfunction "C(3)_3") (pintype "input"))
    )
    (net (code "288") (name "Y_B_MI_STEP") (class "Default")
      (node (ref "J18") (pin "6") (pinfunction "6-INPUT_B-_6") (pintype "passive"))
      (node (ref "R67") (pin "1") (pinfunction "1_1") (pintype "passive"))
      (node (ref "U25") (pin "3") (pinfunction "C(3)_3") (pintype "input"))
    )
    (net (code "289") (name "Y_B_STEP") (class "Default")
      (node (ref "R68") (pin "P$1") (pinfunction "1_P$1") (pintype "passive"))
      (node (ref "U3") (pin "109") (pinfunction "PA_10_109") (pintype "bidirectional"))
    )
    (net (code "290") (name "Z_A_DIR") (class "Default")
      (node (ref "R87") (pin "P$1") (pinfunction "1_P$1") (pintype "passive"))
      (node (ref "U3") (pin "105") (pinfunction "P6_14_105") (pintype "bidirectional"))
    )
    (net (code "291") (name "Z_A_ENABLE") (class "Default")
      (node (ref "R88") (pin "P$1") (pinfunction "1_P$1") (pintype "passive"))
      (node (ref "U3") (pin "104") (pinfunction "P6_13_104") (pintype "bidirectional"))
    )
    (net (code "292") (name "Z_A_HLFB_OUT") (class "Default")
      (node (ref "J21") (pin "5") (pinfunction "5-HLFB-_5") (pintype "passive"))
    )
    (net (code "293") (name "Z_A_MI_DIR") (class "Default")
      (node (ref "J21") (pin "7") (pinfunction "7-INPUT_A-_7") (pintype "passive"))
      (node (ref "R89") (pin "1") (pinfunction "1_1") (pintype "passive"))
      (node (ref "U35") (pin "3") (pinfunction "C(3)_3") (pintype "input"))
    )
    (net (code "294") (name "Z_A_MI_ENABLE") (class "Default")
      (node (ref "J21") (pin "8") (pinfunction "8-ENABLE-_8") (pintype "passive"))
      (node (ref "R90") (pin "1") (pinfunction "1_1") (pintype "passive"))
      (node (ref "U36") (pin "3") (pinfunction "C(3)_3") (pintype "input"))
    )
    (net (code "295") (name "Z_A_MI_STEP") (class "Default")
      (node (ref "J21") (pin "6") (pinfunction "6-INPUT_B-_6") (pintype "passive"))
      (node (ref "R85") (pin "1") (pinfunction "1_1") (pintype "passive"))
      (node (ref "U34") (pin "3") (pinfunction "C(3)_3") (pintype "input"))
    )
    (net (code "296") (name "Z_A_STEP") (class "Default")
      (node (ref "R86") (pin "P$1") (pinfunction "1_P$1") (pintype "passive"))
      (node (ref "U3") (pin "106") (pinfunction "P6_15_106") (pintype "bidirectional"))
    )
    (net (code "297") (name "Z_B_DIR") (class "Default")
      (node (ref "R93") (pin "P$1") (pinfunction "1_P$1") (pintype "passive"))
      (node (ref "U3") (pin "102") (pinfunction "P6_11_102") (pintype "bidirectional"))
    )
    (net (code "298") (name "Z_B_ENABLE") (class "Default")
      (node (ref "R94") (pin "P$1") (pinfunction "1_P$1") (pintype "passive"))
      (node (ref "U3") (pin "101") (pinfunction "P6_10_101") (pintype "bidirectional"))
    )
    (net (code "299") (name "Z_B_HLFB_OUT") (class "Default")
      (node (ref "J22") (pin "5") (pinfunction "5-HLFB-_5") (pintype "passive"))
    )
    (net (code "300") (name "Z_B_MI_DIR") (class "Default")
      (node (ref "J22") (pin "7") (pinfunction "7-INPUT_A-_7") (pintype "passive"))
      (node (ref "R95") (pin "1") (pinfunction "1_1") (pintype "passive"))
      (node (ref "U38") (pin "3") (pinfunction "C(3)_3") (pintype "input"))
    )
    (net (code "301") (name "Z_B_MI_ENABLE") (class "Default")
      (node (ref "J22") (pin "8") (pinfunction "8-ENABLE-_8") (pintype "passive"))
      (node (ref "R96") (pin "1") (pinfunction "1_1") (pintype "passive"))
      (node (ref "U39") (pin "3") (pinfunction "C(3)_3") (pintype "input"))
    )
    (net (code "302") (name "Z_B_MI_STEP") (class "Default")
      (node (ref "J22") (pin "6") (pinfunction "6-INPUT_B-_6") (pintype "passive"))
      (node (ref "R91") (pin "1") (pinfunction "1_1") (pintype "passive"))
      (node (ref "U37") (pin "3") (pinfunction "C(3)_3") (pintype "input"))
    )
    (net (code "303") (name "Z_B_STEP") (class "Default")
      (node (ref "R92") (pin "P$1") (pinfunction "1_P$1") (pintype "passive"))
      (node (ref "U3") (pin "103") (pinfunction "P6_12_103") (pintype "bidirectional"))
    )
    (net (code "304") (name "unconnected-(U3-VBAT-Pad18)") (class "Default")
      (node (ref "U3") (pin "18") (pinfunction "VBAT_18") (pintype "bidirectional"))
    )
  )
)
